# demo_dermis_main_testboard_scratch.net
KiCad netlist of a schematic drawn in Altium Designer
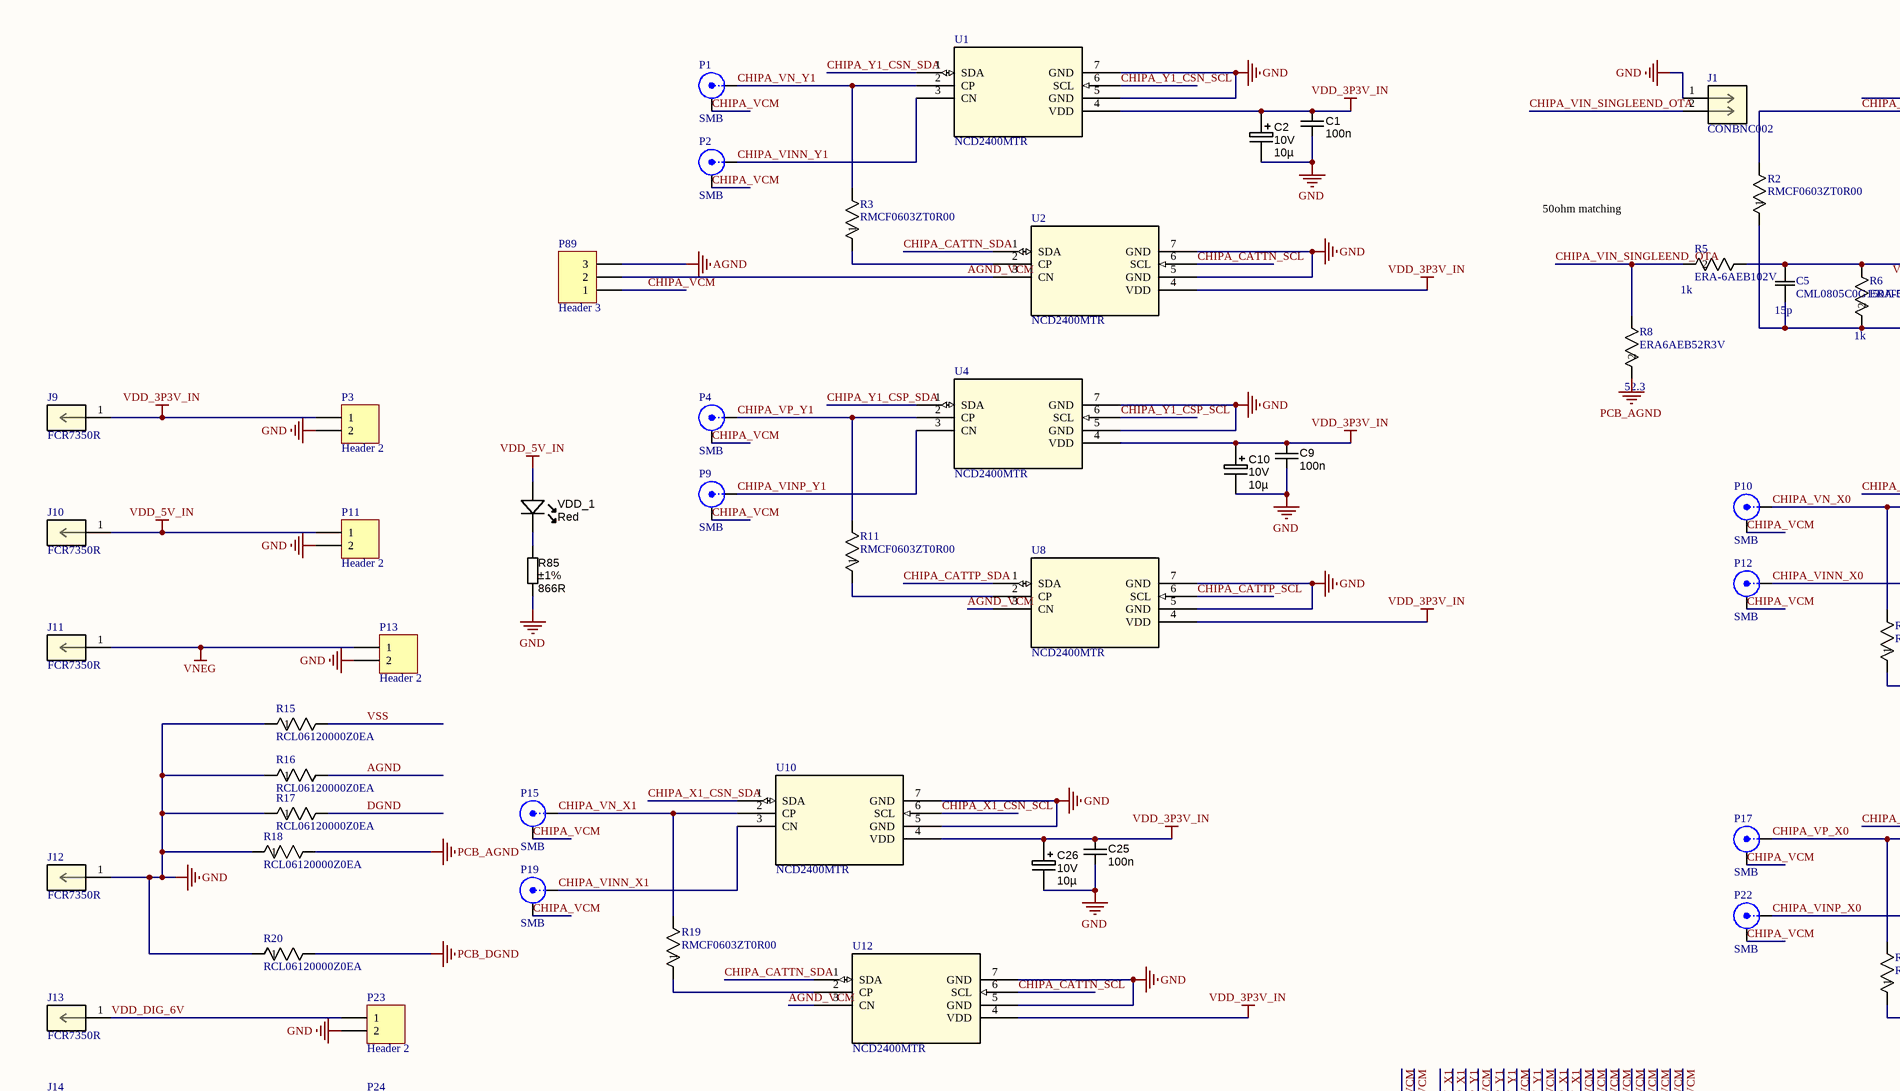
[diagram p0: demo_dermis_main_testboard_scratch.SchDoc, top left]
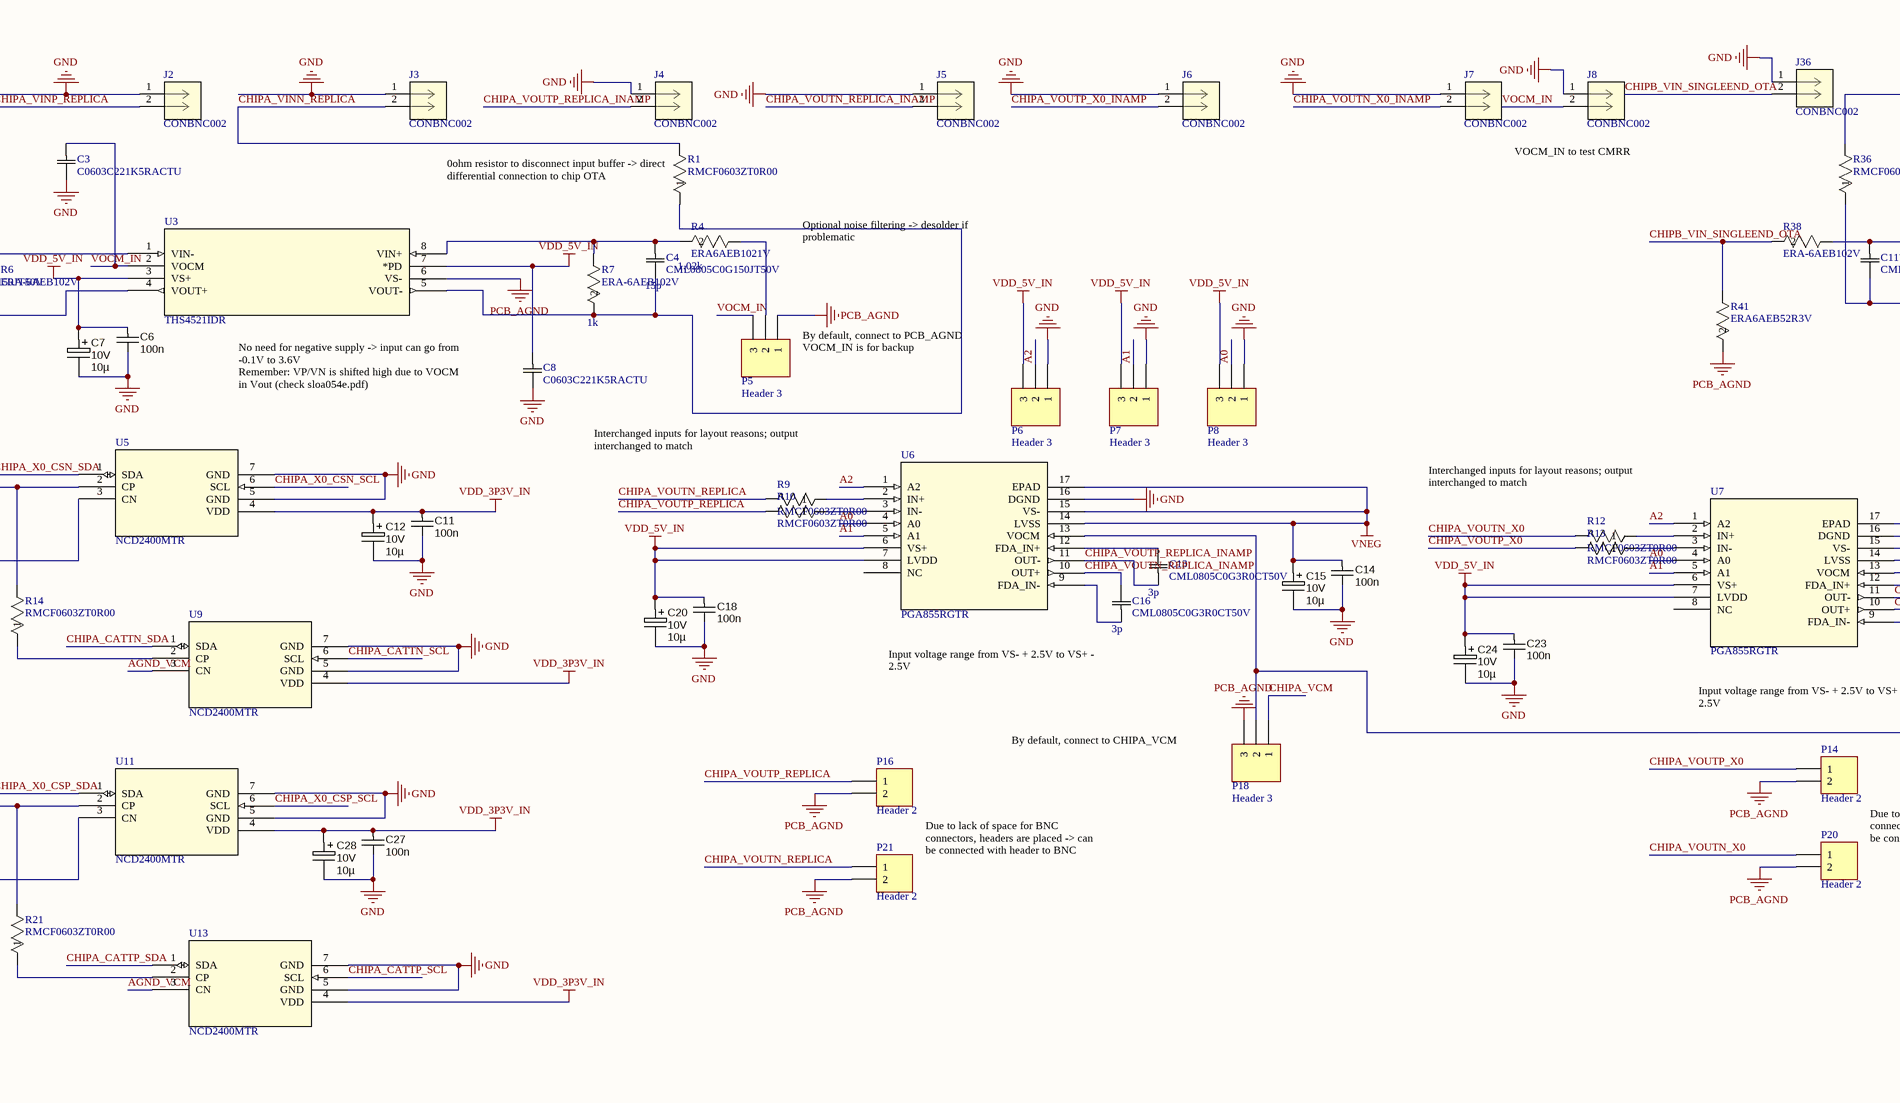
[diagram p1: demo_dermis_main_testboard_scratch.SchDoc, top middle]
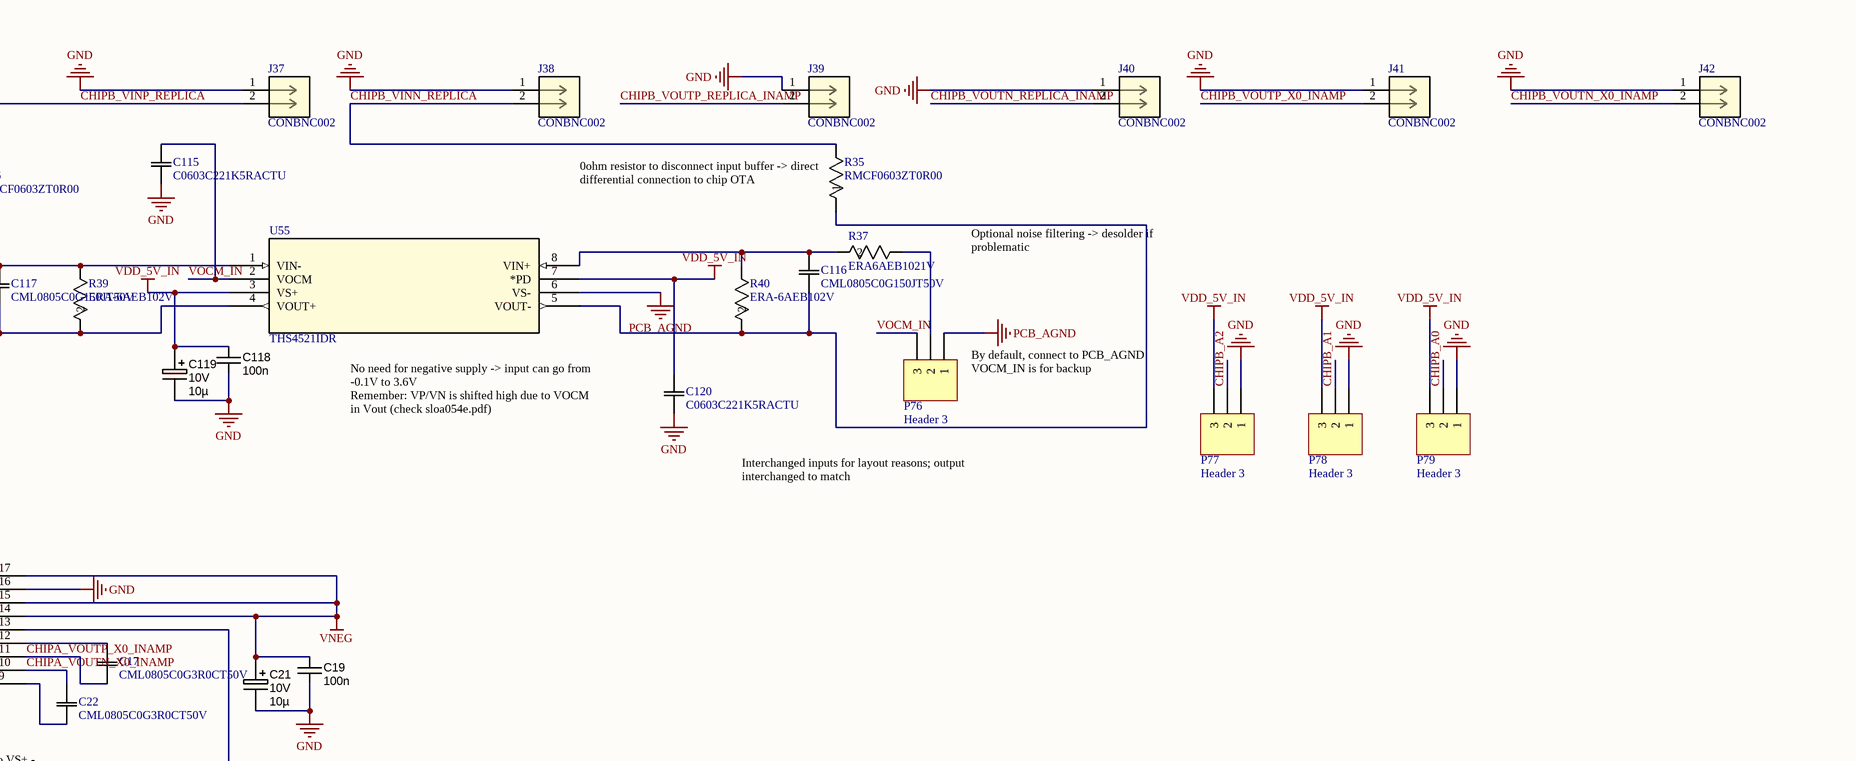
[diagram p2: demo_dermis_main_testboard_scratch.SchDoc, top right]
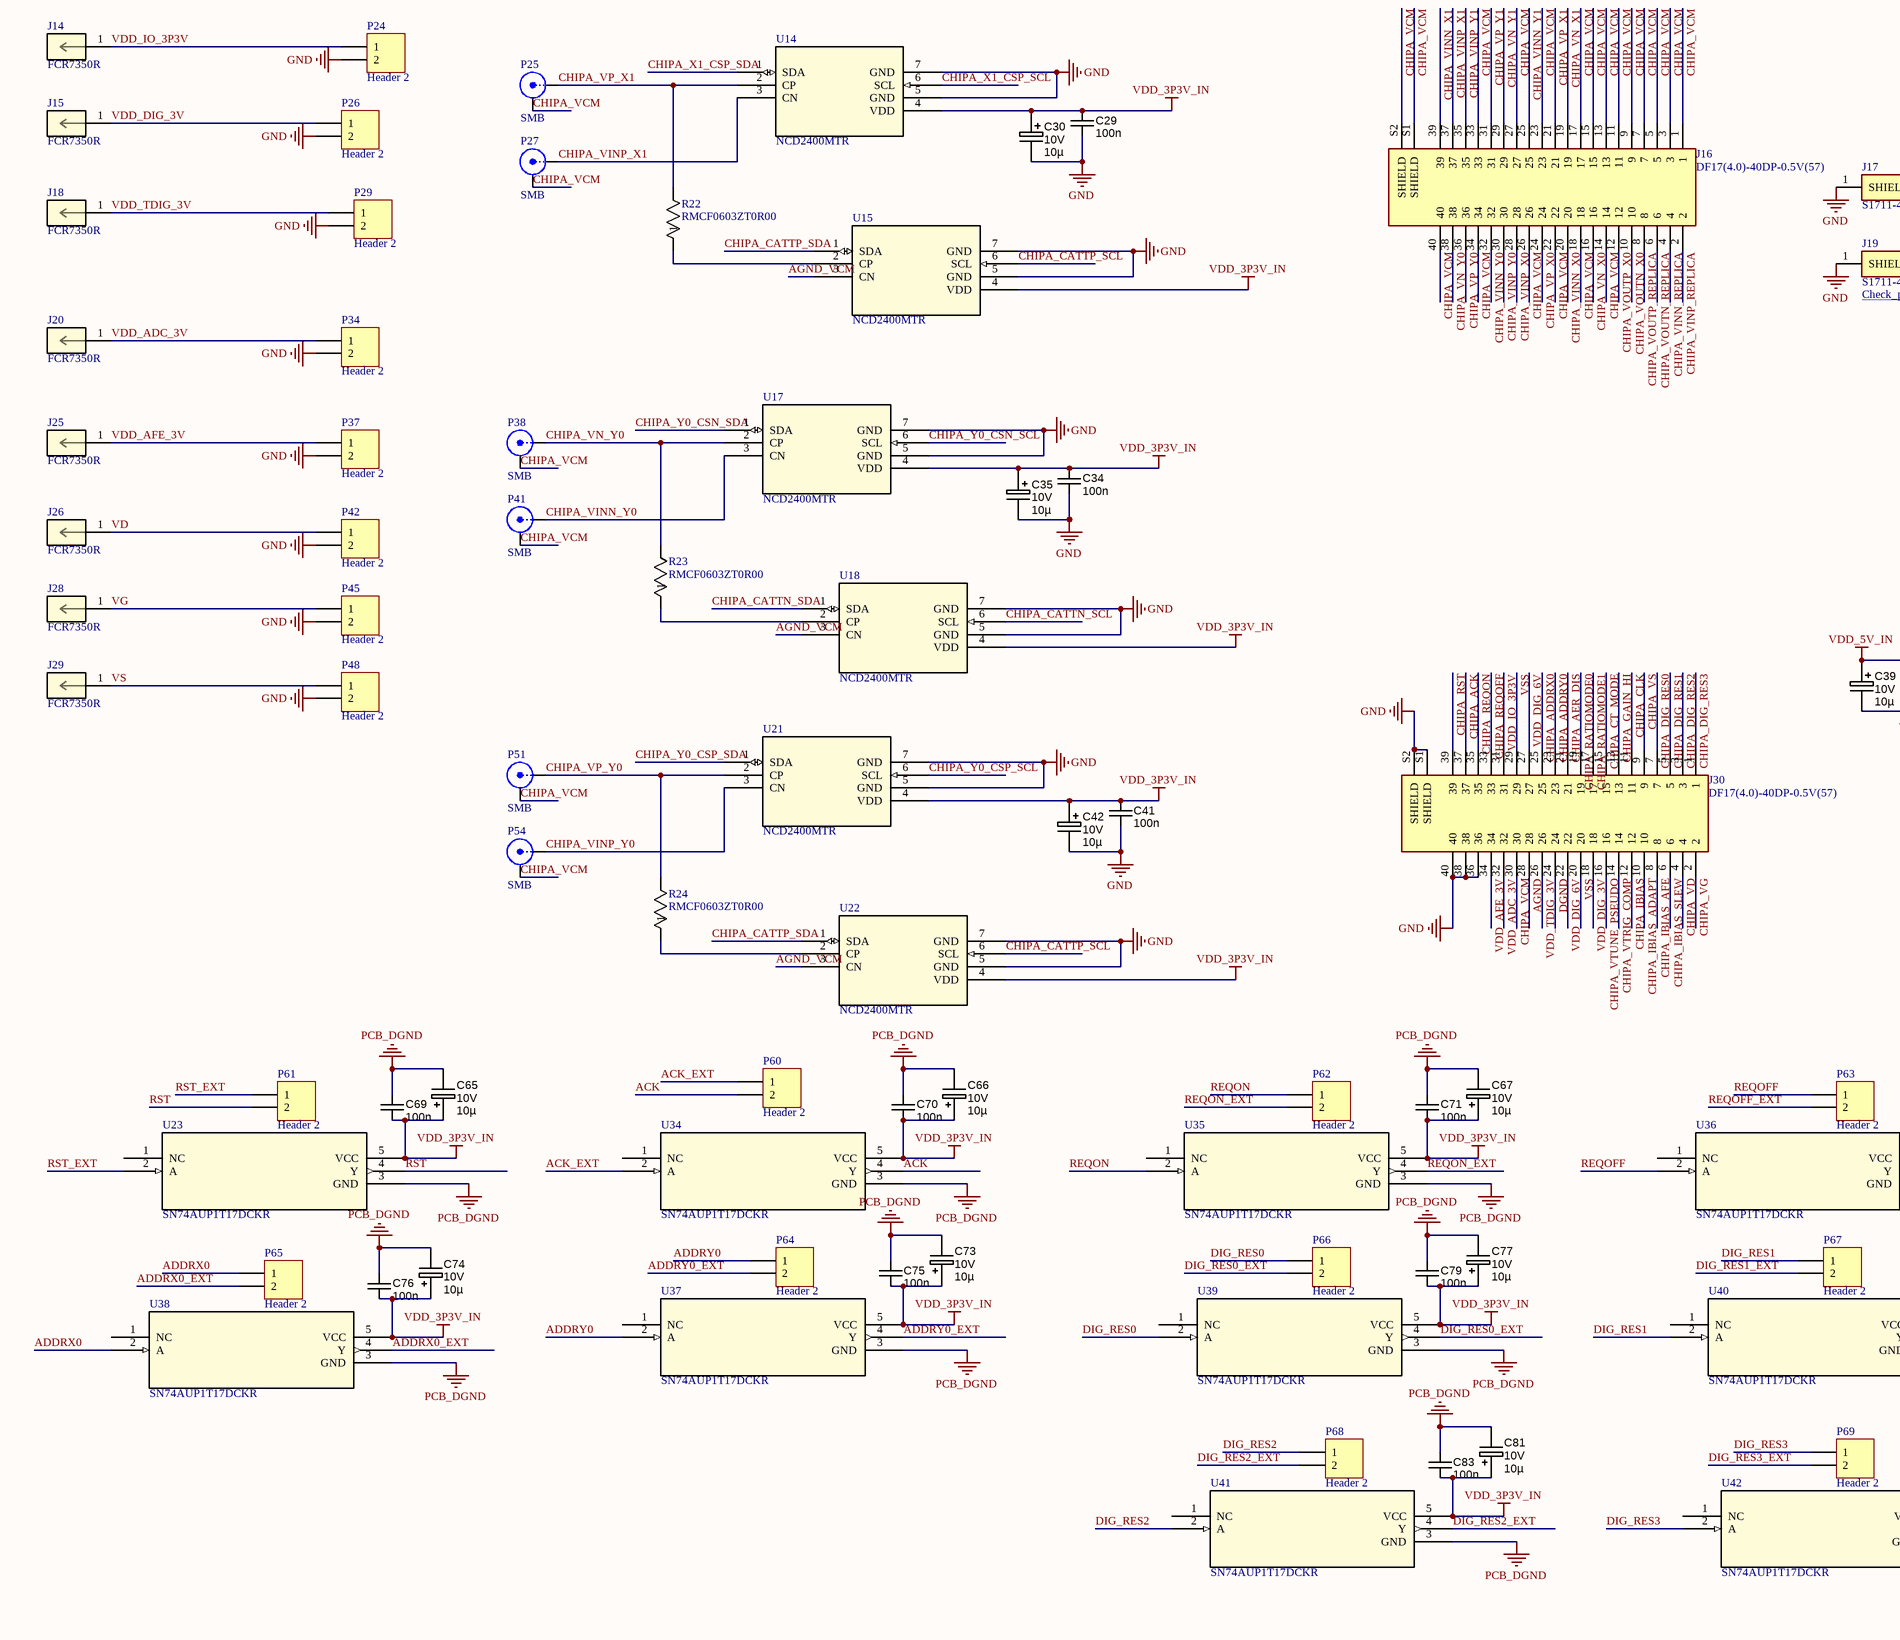
[diagram p3: demo_dermis_main_testboard_scratch.SchDoc, centre left]
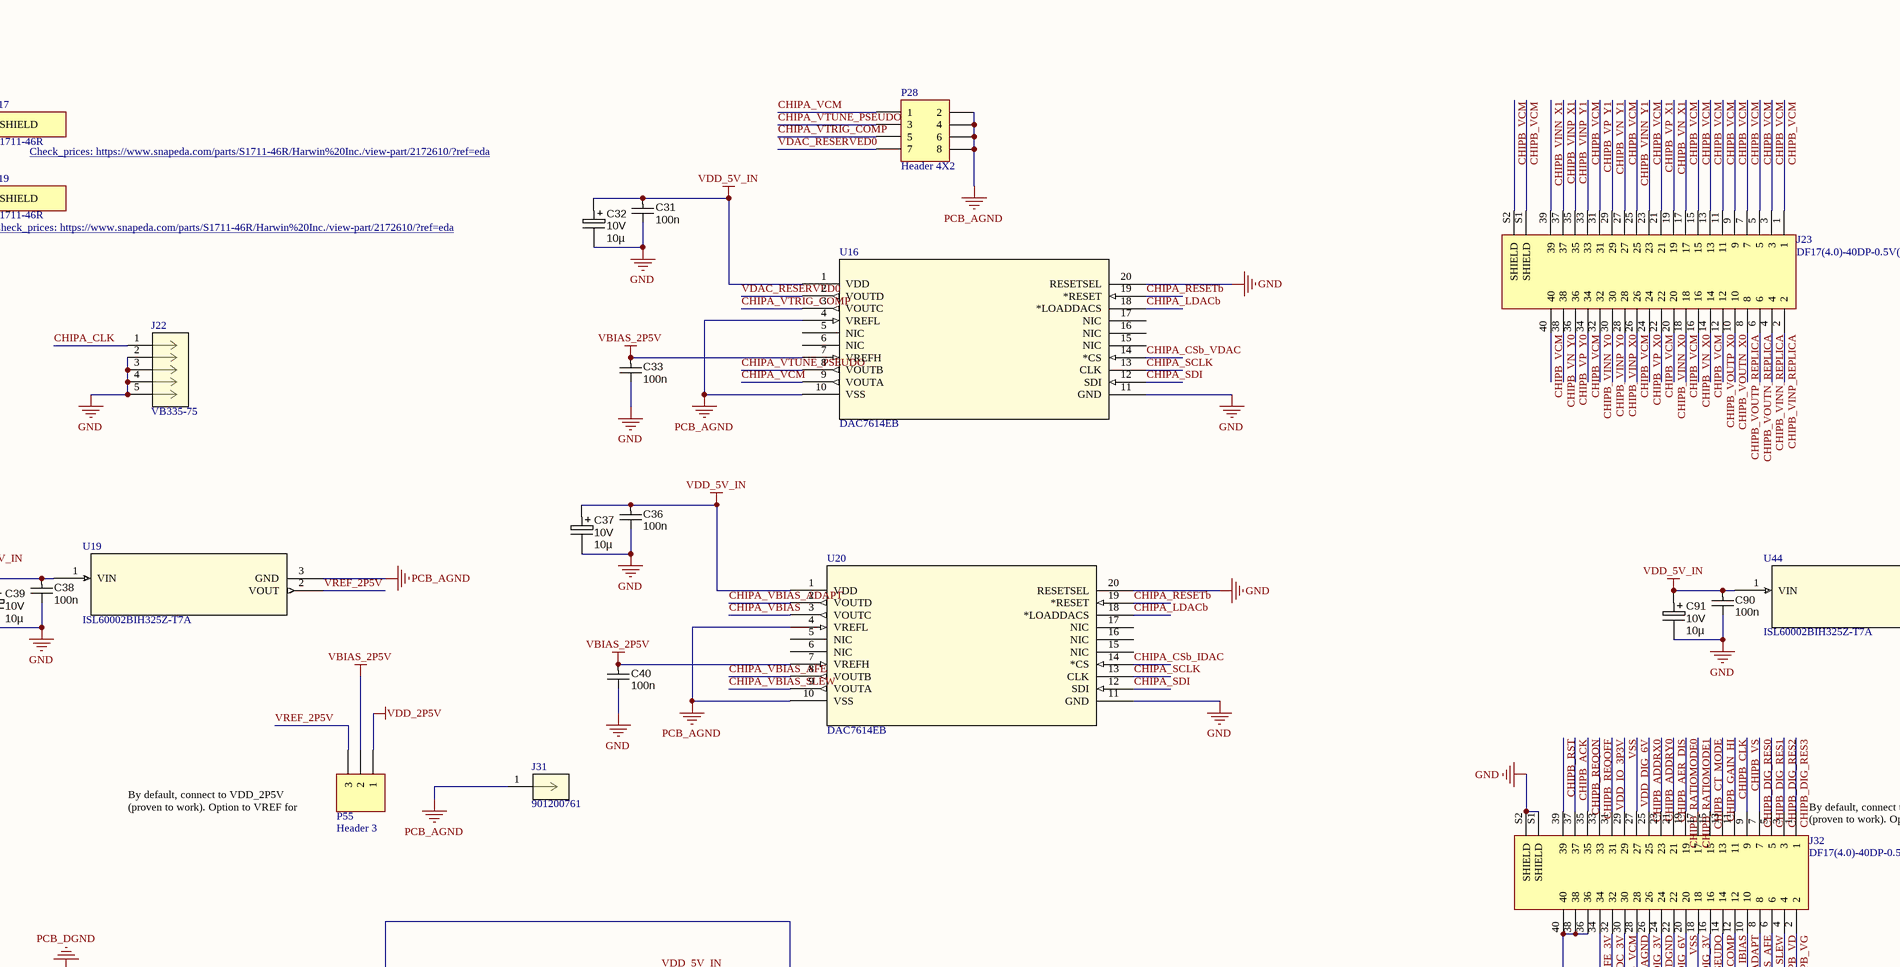
[diagram p4: demo_dermis_main_testboard_scratch.SchDoc, centre middle]
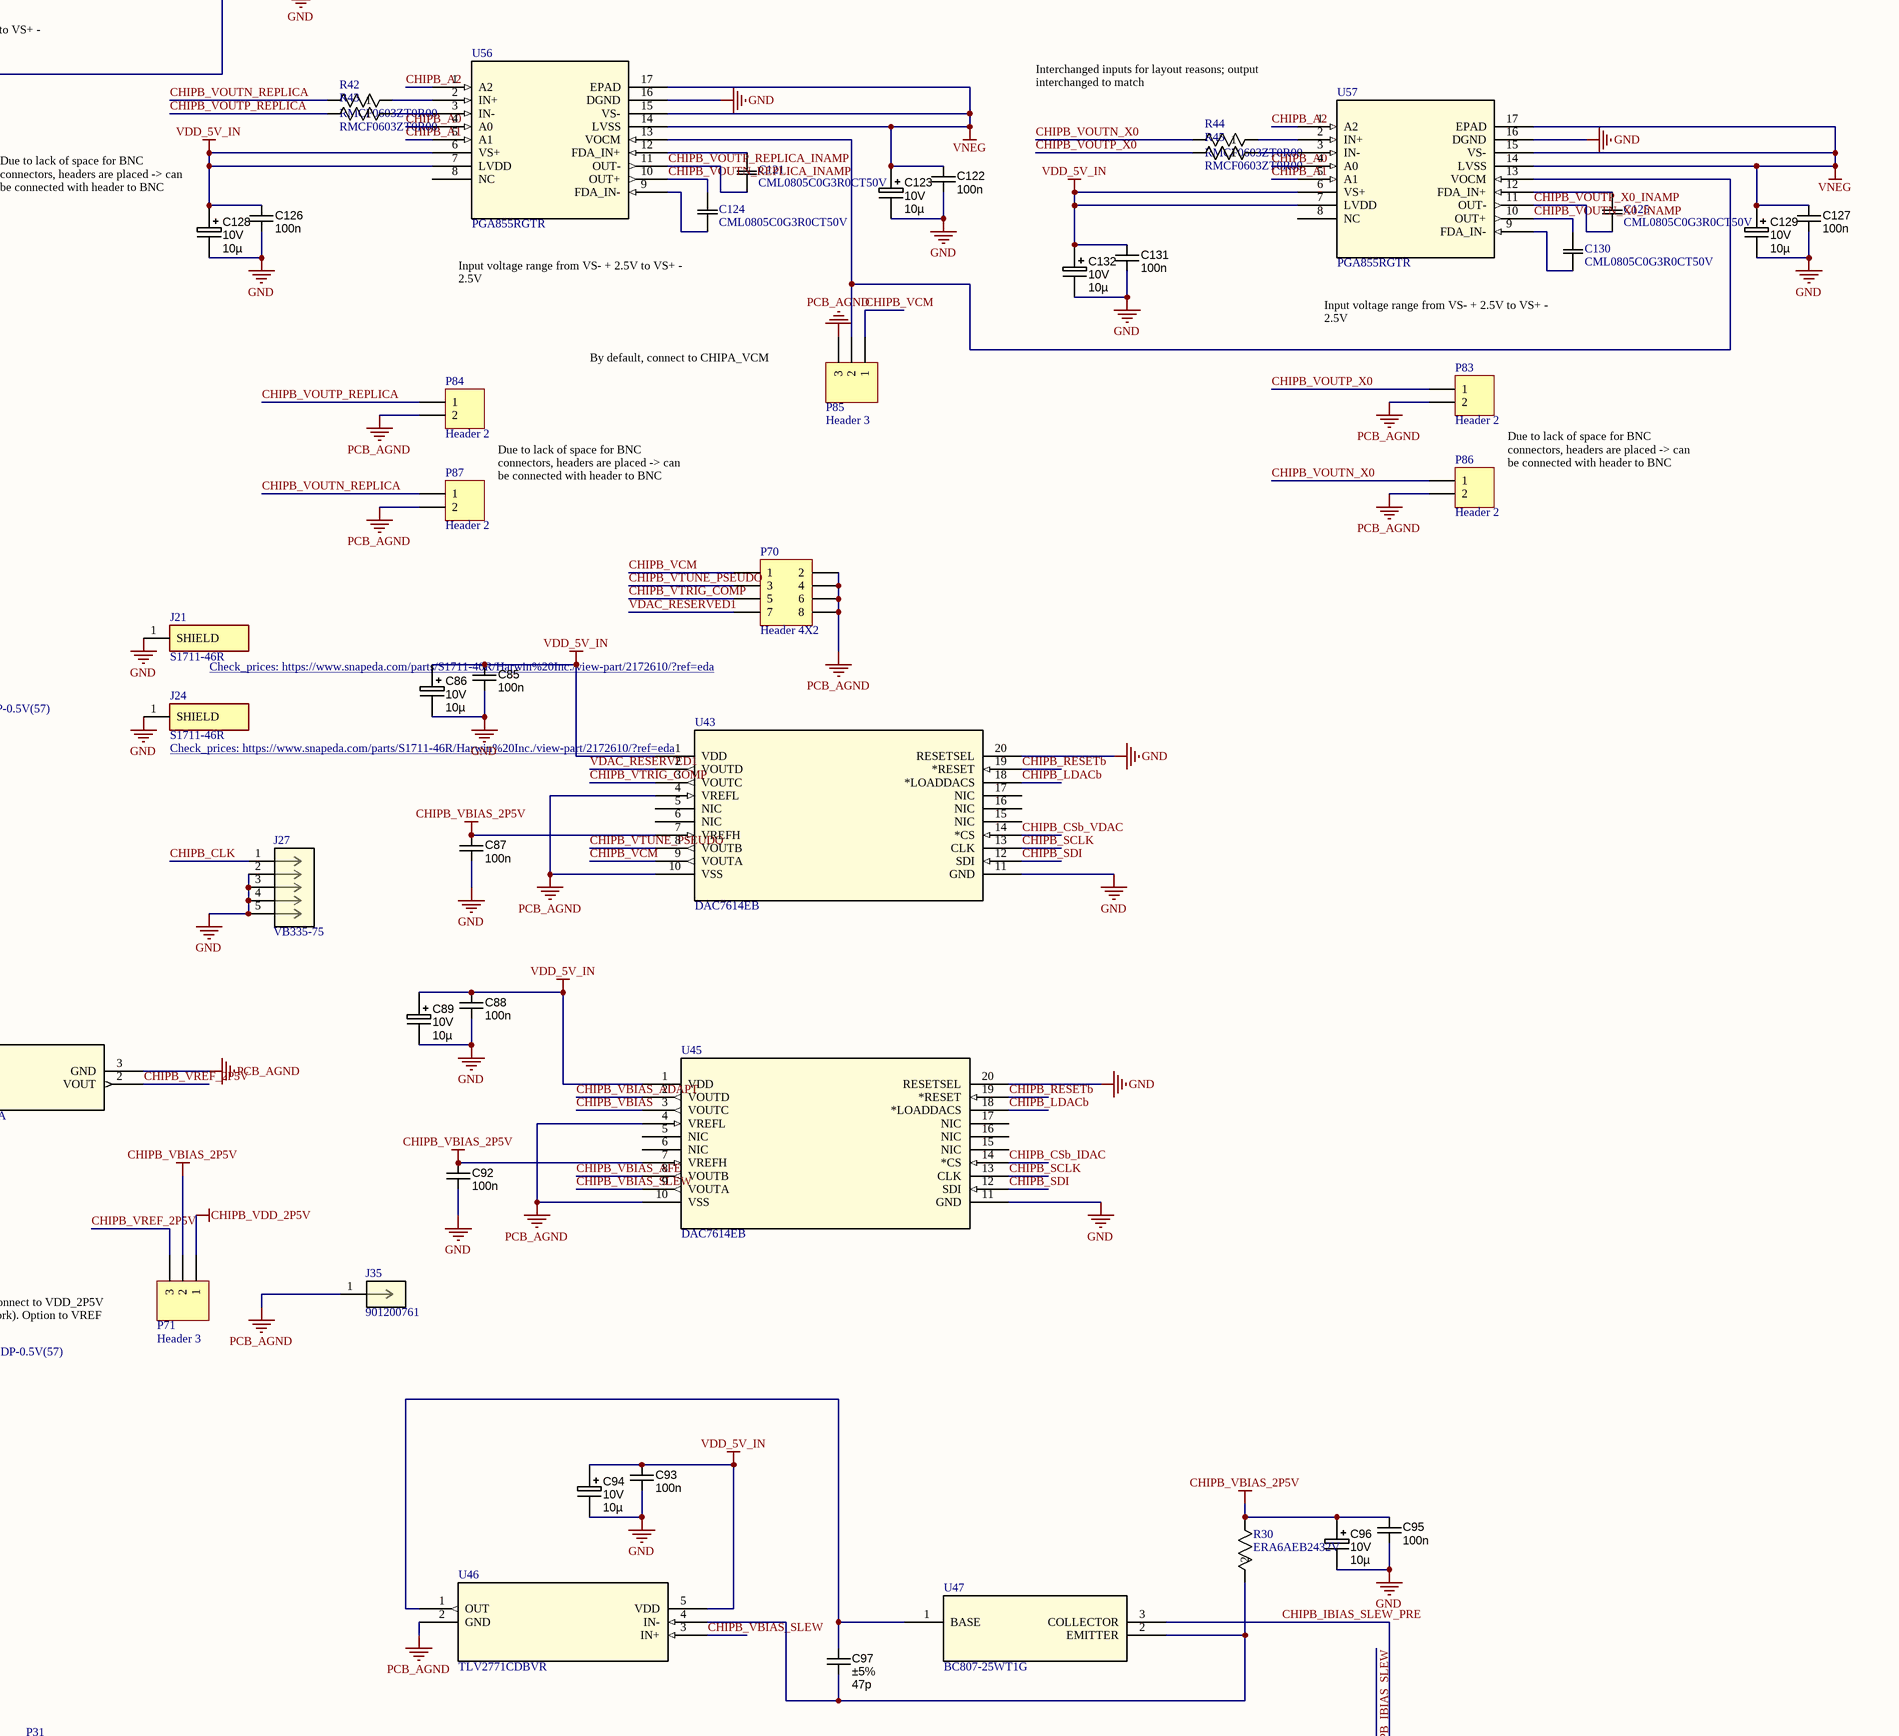
[diagram p5: demo_dermis_main_testboard_scratch.SchDoc, centre right]
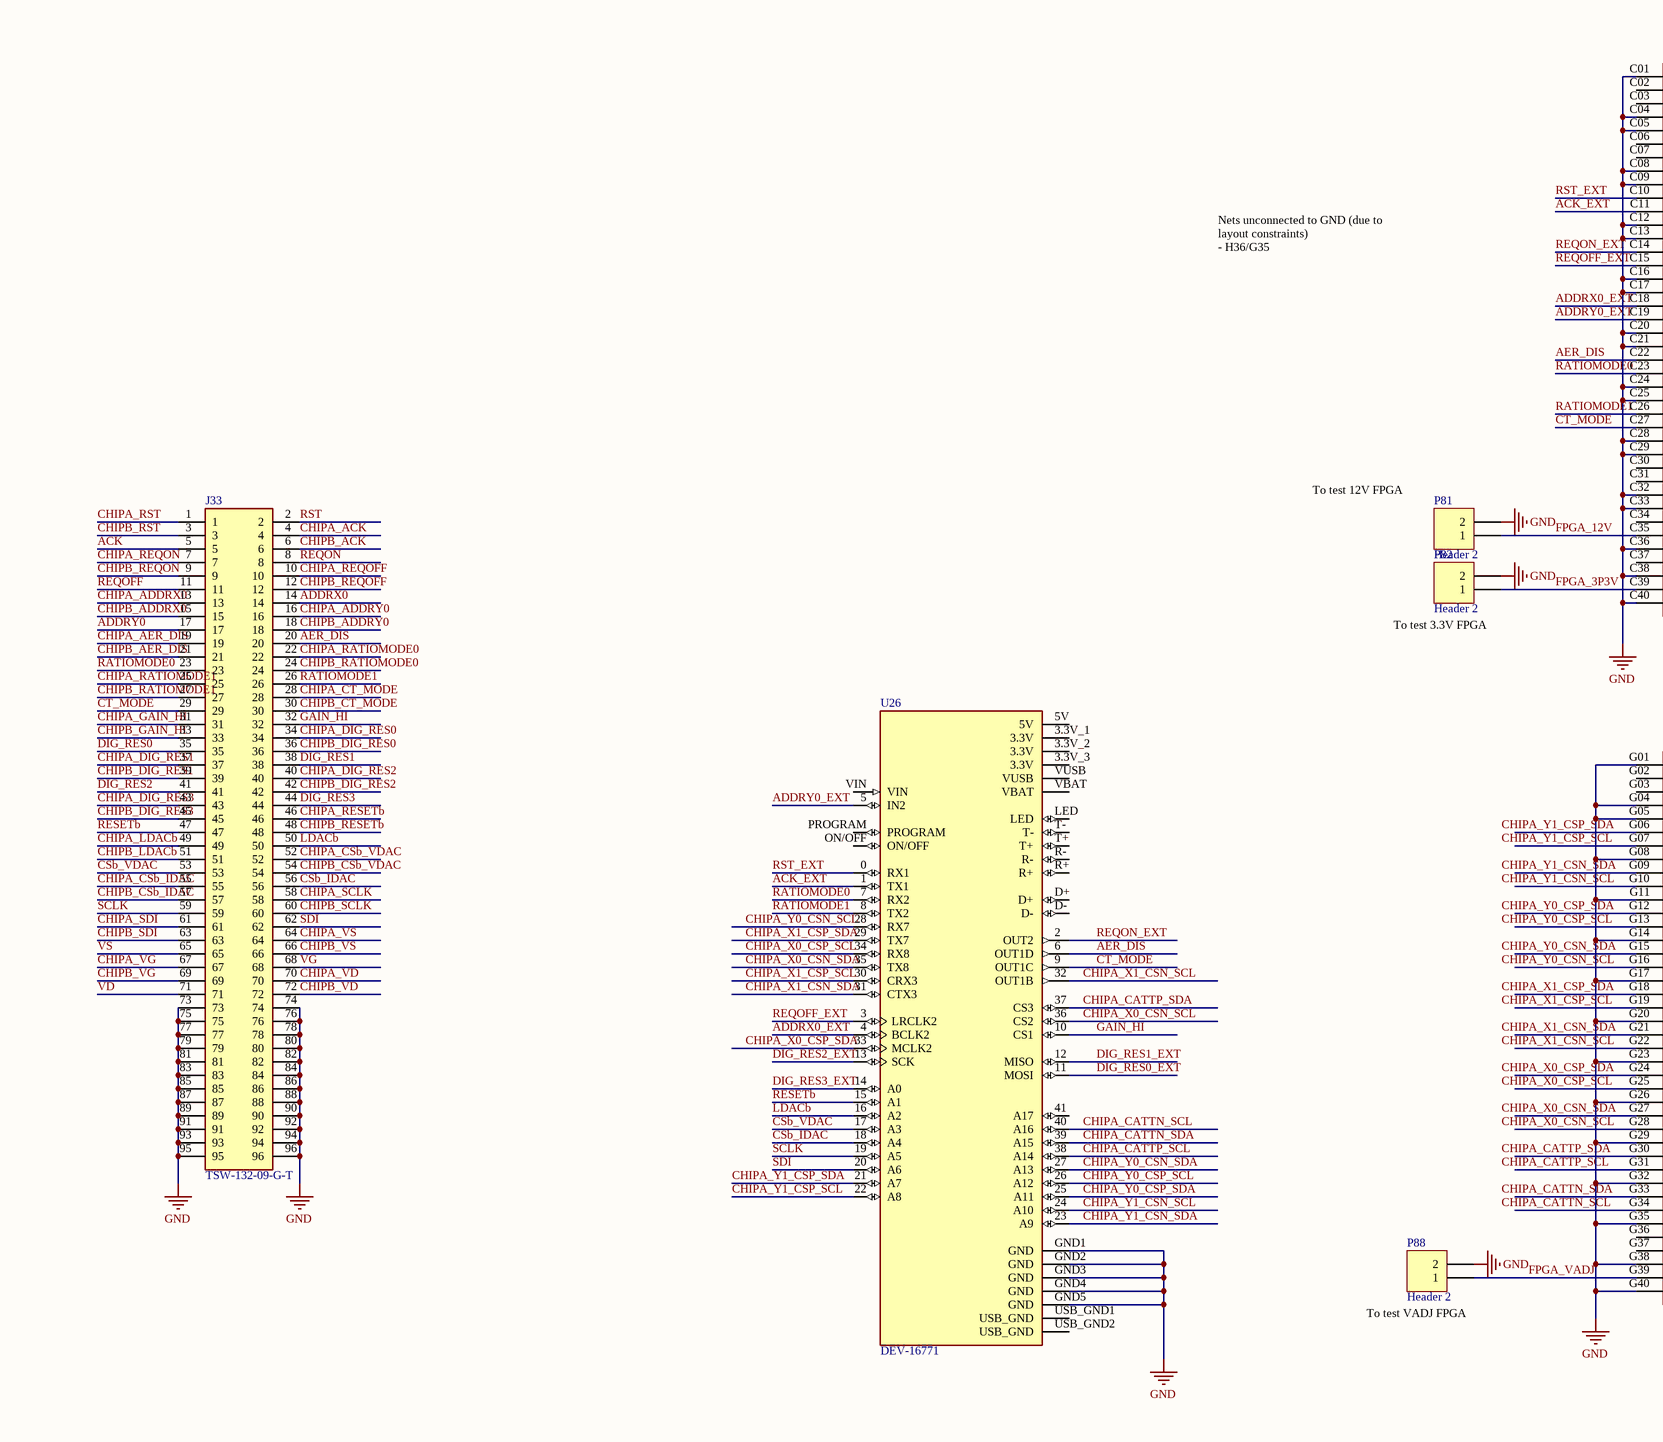
[diagram p6: demo_dermis_main_testboard_scratch.SchDoc, bottom left]
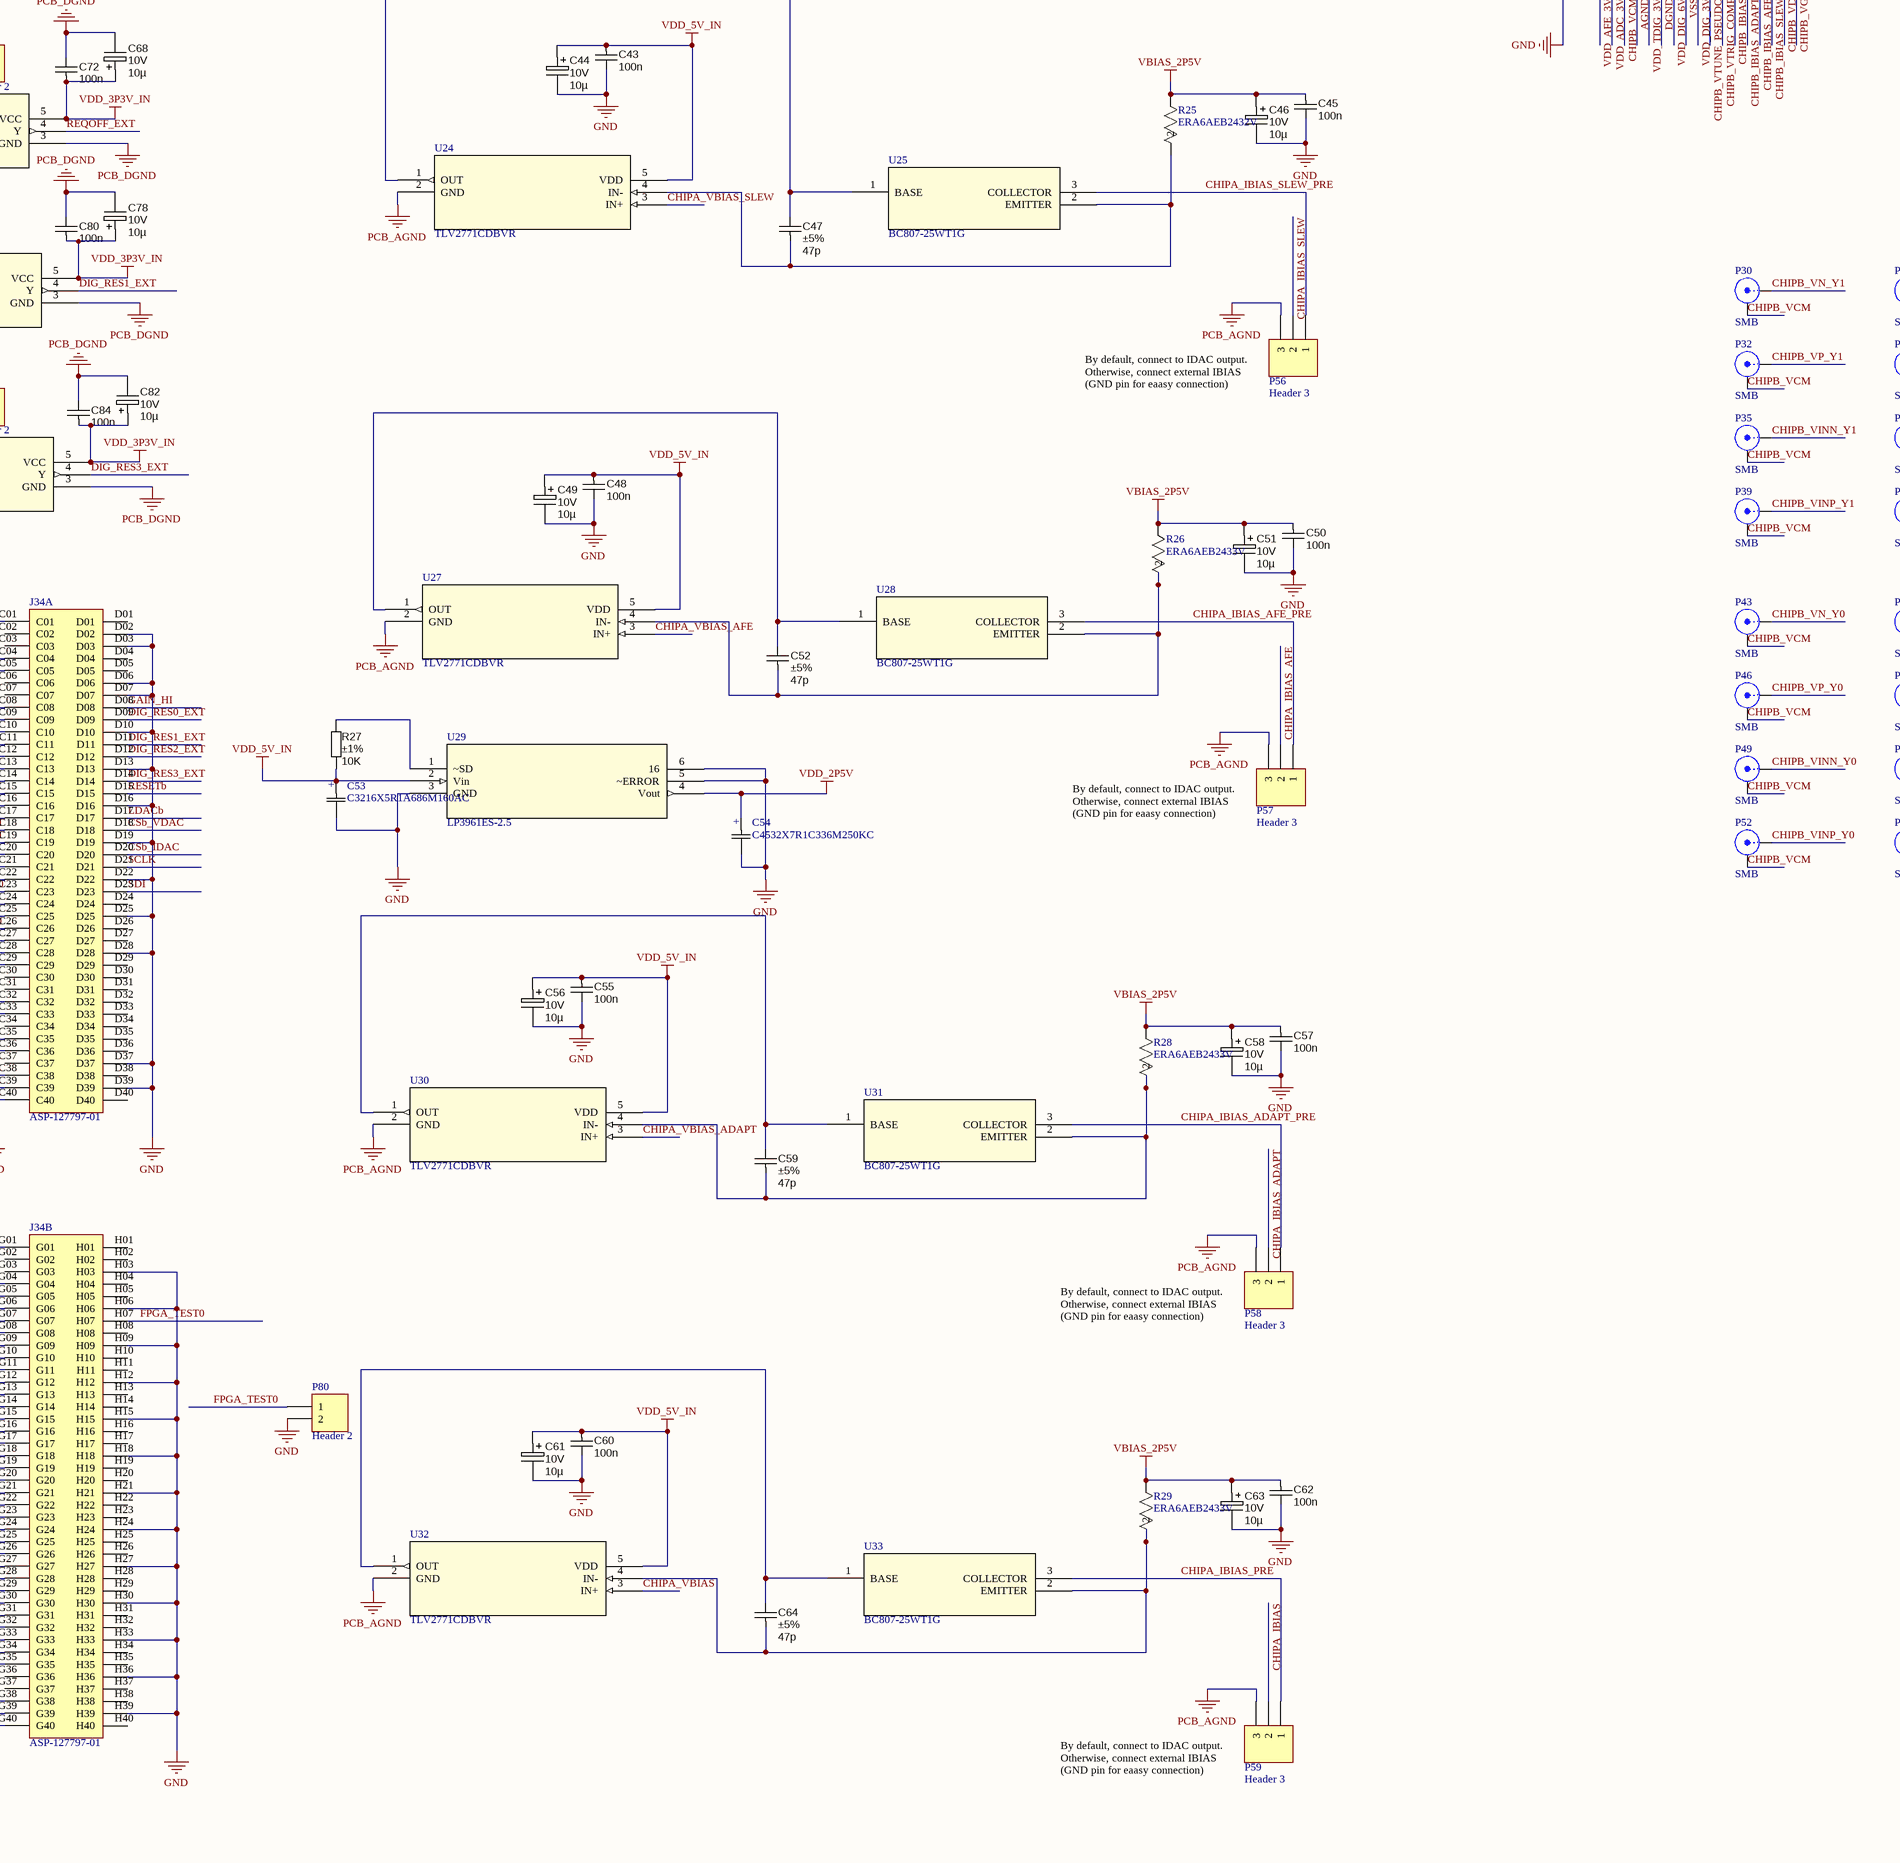
[diagram p7: demo_dermis_main_testboard_scratch.SchDoc, bottom middle]
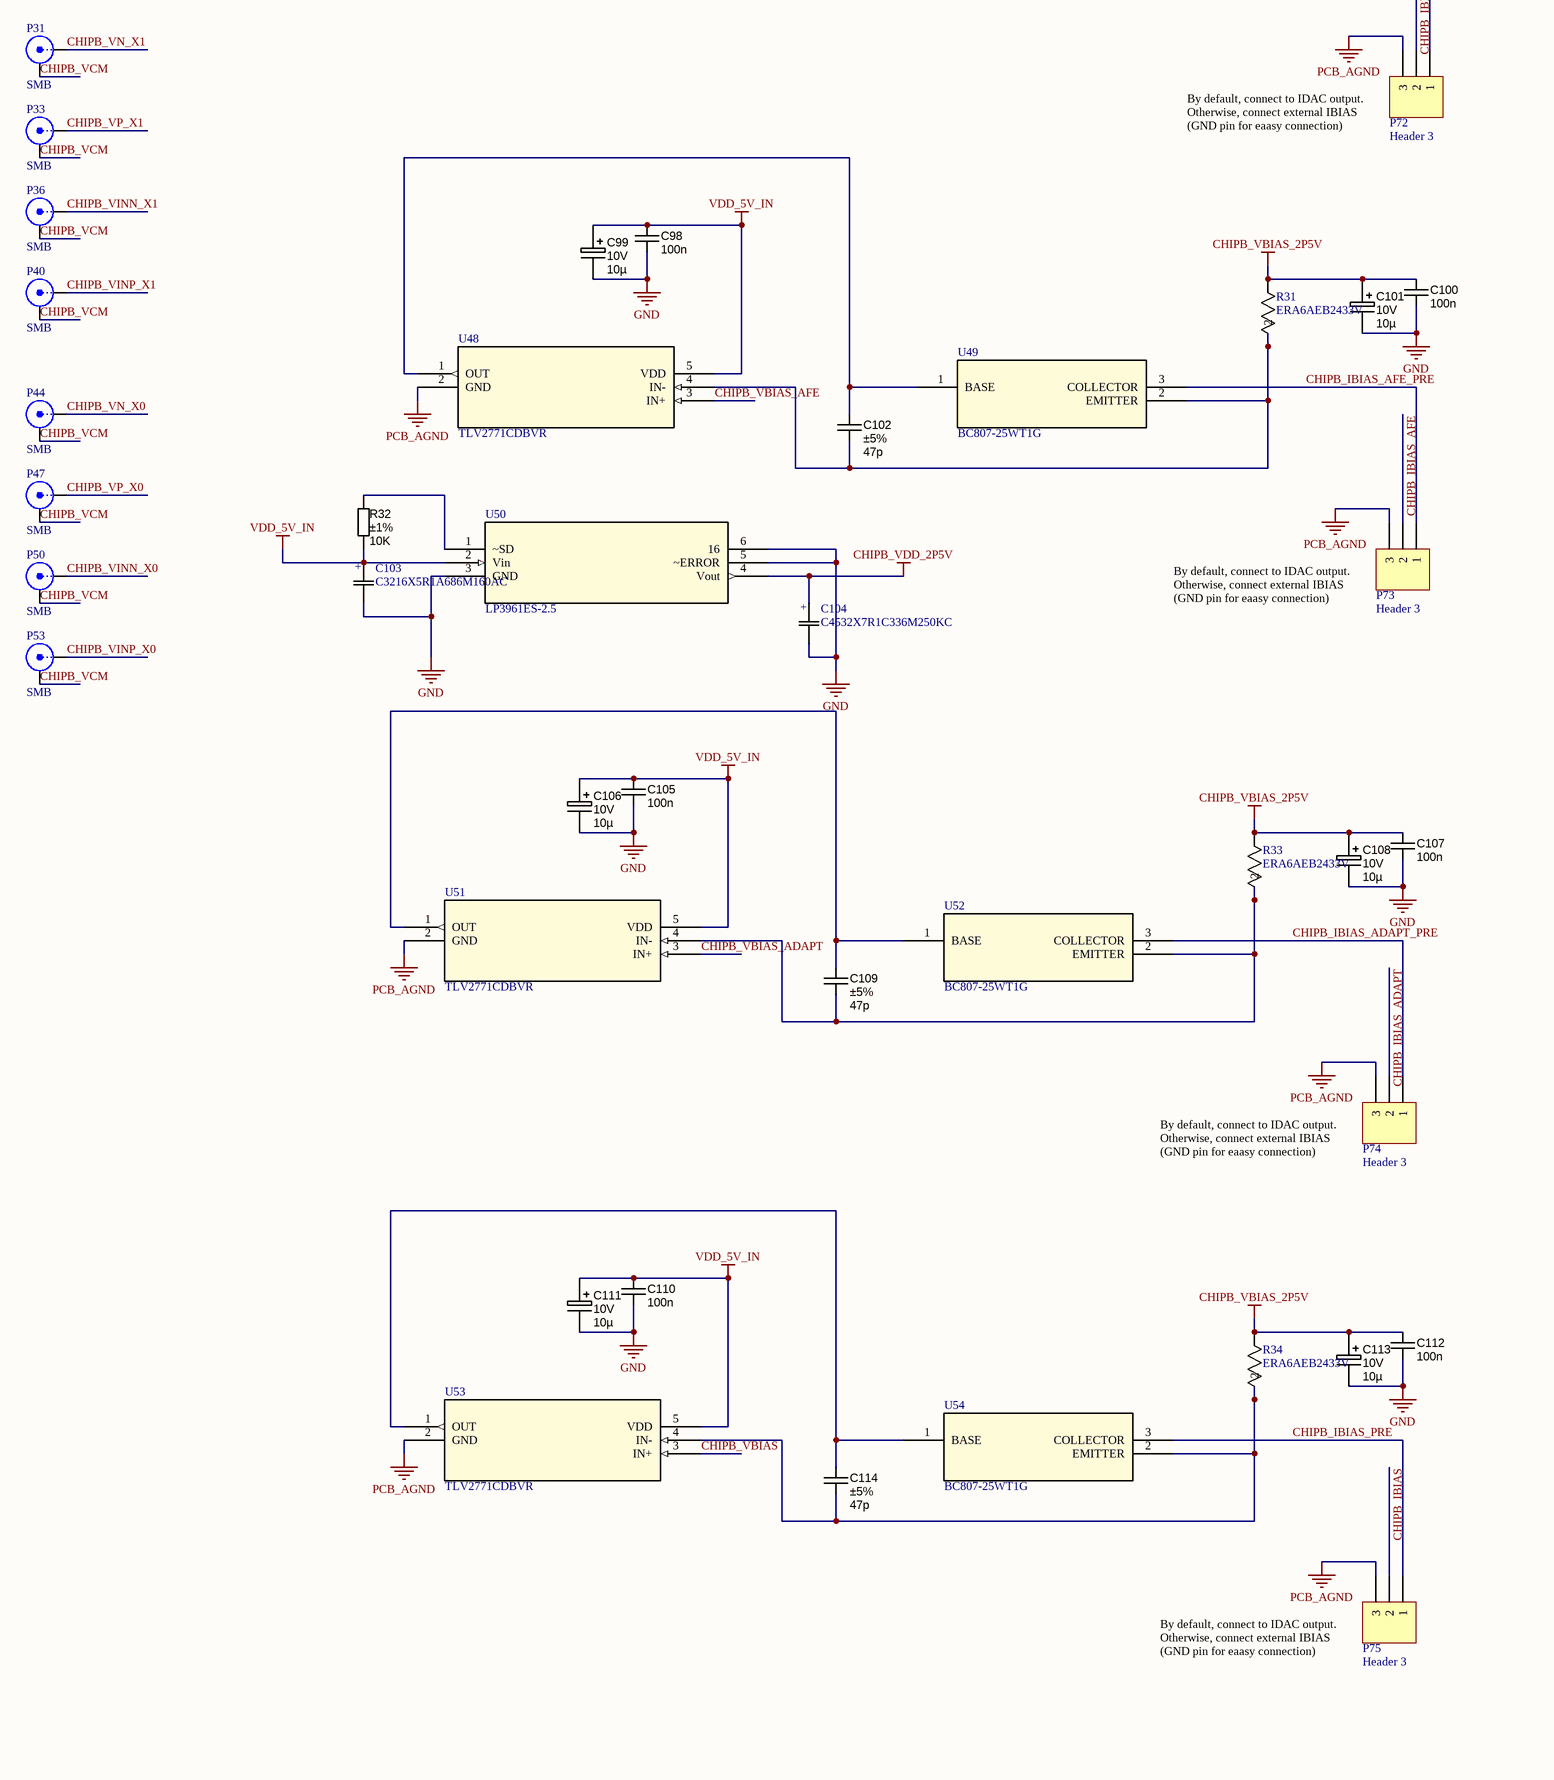
[diagram p8: demo_dermis_main_testboard_scratch.SchDoc, bottom right]

(export (version "E")
  (design (tool "Eeschema 10.0.6"))
  (components
    (comp (ref "C1")
      (value "100n")
      (footprint "CAPC1608N")
      (description "Capacitor SMD Cer 100nF 10% 50V X7R 0603")
      (fields (field (name "TOLERANCE") "±10%") (field (name "Comment") "approved sub OK"))
      (libsource (lib "PBL - Capacitors") (part "CAPC_100n_0603"))
    )
    (comp (ref "C2")
      (value "10µ")
      (footprint "CAPMP2012X150USR")
      (description "Capacitor SMD Tantalum 10uF 20% 10V 0805")
      (fields (field (name "TOLERANCE") "±20%") (field (name "RATINGS") "10V"))
      (libsource (lib "PBL - Capacitors") (part "CAPT_10u_0805_10V"))
    )
    (comp (ref "C3")
      (value "C0603C221K5RACTU")
      (footprint "CAPC17595_87N_KEM")
      (description "No Description Available")
      (libsource (lib "C0603C221K5RACTU") (part "C0603C221K5RACTU"))
    )
    (comp (ref "C4")
      (value "CML0805C0G150JT50V")
      (footprint "CAP_CML_0805_.3pF-1500pF,4700pF_STP")
      (description "No Description Available")
      (fields (field (name "ALTIUM_VALUE") "15p"))
      (libsource (lib "CML0805C0G150JT50V") (part "CML0805C0G150JT50V"))
    )
    (comp (ref "C5")
      (value "CML0805C0G150JT50V")
      (footprint "CAP_CML_0805_.3pF-1500pF,4700pF_STP")
      (description "No Description Available")
      (fields (field (name "ALTIUM_VALUE") "15p"))
      (libsource (lib "CML0805C0G150JT50V") (part "CML0805C0G150JT50V"))
    )
    (comp (ref "C6")
      (value "100n")
      (footprint "CAPC1608N")
      (description "Capacitor SMD Cer 100nF 10% 50V X7R 0603")
      (fields (field (name "TOLERANCE") "±10%") (field (name "Comment") "approved sub OK"))
      (libsource (lib "PBL - Capacitors") (part "CAPC_100n_0603"))
    )
    (comp (ref "C7")
      (value "10µ")
      (footprint "CAPMP2012X150USR")
      (description "Capacitor SMD Tantalum 10uF 20% 10V 0805")
      (fields (field (name "TOLERANCE") "±20%") (field (name "RATINGS") "10V"))
      (libsource (lib "PBL - Capacitors") (part "CAPT_10u_0805_10V"))
    )
    (comp (ref "C8")
      (value "C0603C221K5RACTU")
      (footprint "CAPC17595_87N_KEM")
      (description "No Description Available")
      (libsource (lib "C0603C221K5RACTU") (part "C0603C221K5RACTU"))
    )
    (comp (ref "C9")
      (value "100n")
      (footprint "CAPC1608N")
      (description "Capacitor SMD Cer 100nF 10% 50V X7R 0603")
      (fields (field (name "TOLERANCE") "±10%") (field (name "Comment") "approved sub OK"))
      (libsource (lib "PBL - Capacitors") (part "CAPC_100n_0603"))
    )
    (comp (ref "C10")
      (value "10µ")
      (footprint "CAPMP2012X150USR")
      (description "Capacitor SMD Tantalum 10uF 20% 10V 0805")
      (fields (field (name "TOLERANCE") "±20%") (field (name "RATINGS") "10V"))
      (libsource (lib "PBL - Capacitors") (part "CAPT_10u_0805_10V"))
    )
    (comp (ref "C11")
      (value "100n")
      (footprint "CAPC1608N")
      (description "Capacitor SMD Cer 100nF 10% 50V X7R 0603")
      (fields (field (name "TOLERANCE") "±10%") (field (name "Comment") "approved sub OK"))
      (libsource (lib "PBL - Capacitors") (part "CAPC_100n_0603"))
    )
    (comp (ref "C12")
      (value "10µ")
      (footprint "CAPMP2012X150USR")
      (description "Capacitor SMD Tantalum 10uF 20% 10V 0805")
      (fields (field (name "TOLERANCE") "±20%") (field (name "RATINGS") "10V"))
      (libsource (lib "PBL - Capacitors") (part "CAPT_10u_0805_10V"))
    )
    (comp (ref "C13")
      (value "CML0805C0G3R0CT50V")
      (footprint "CAP_CML_0805_.3pF-1500pF,4700pF_STP")
      (description "No Description Available")
      (fields (field (name "ALTIUM_VALUE") "3p"))
      (libsource (lib "CML0805C0G3R0CT50V") (part "CML0805C0G3R0CT50V"))
    )
    (comp (ref "C14")
      (value "100n")
      (footprint "CAPC1608N")
      (description "Capacitor SMD Cer 100nF 10% 50V X7R 0603")
      (fields (field (name "TOLERANCE") "±10%") (field (name "Comment") "approved sub OK"))
      (libsource (lib "PBL - Capacitors") (part "CAPC_100n_0603"))
    )
    (comp (ref "C15")
      (value "10µ")
      (footprint "CAPMP2012X150USR")
      (description "Capacitor SMD Tantalum 10uF 20% 10V 0805")
      (fields (field (name "TOLERANCE") "±20%") (field (name "RATINGS") "10V"))
      (libsource (lib "PBL - Capacitors") (part "CAPT_10u_0805_10V"))
    )
    (comp (ref "C16")
      (value "CML0805C0G3R0CT50V")
      (footprint "CAP_CML_0805_.3pF-1500pF,4700pF_STP")
      (description "No Description Available")
      (fields (field (name "ALTIUM_VALUE") "3p"))
      (libsource (lib "CML0805C0G3R0CT50V") (part "CML0805C0G3R0CT50V"))
    )
    (comp (ref "C17")
      (value "CML0805C0G3R0CT50V")
      (footprint "CAP_CML_0805_.3pF-1500pF,4700pF_STP")
      (description "No Description Available")
      (libsource (lib "CML0805C0G3R0CT50V") (part "CML0805C0G3R0CT50V"))
    )
    (comp (ref "C18")
      (value "100n")
      (footprint "CAPC1608N")
      (description "Capacitor SMD Cer 100nF 10% 50V X7R 0603")
      (fields (field (name "TOLERANCE") "±10%") (field (name "Comment") "approved sub OK"))
      (libsource (lib "PBL - Capacitors") (part "CAPC_100n_0603"))
    )
    (comp (ref "C19")
      (value "100n")
      (footprint "CAPC1608N")
      (description "Capacitor SMD Cer 100nF 10% 50V X7R 0603")
      (fields (field (name "TOLERANCE") "±10%") (field (name "Comment") "approved sub OK"))
      (libsource (lib "PBL - Capacitors") (part "CAPC_100n_0603"))
    )
    (comp (ref "C20")
      (value "10µ")
      (footprint "CAPMP2012X150USR")
      (description "Capacitor SMD Tantalum 10uF 20% 10V 0805")
      (fields (field (name "TOLERANCE") "±20%") (field (name "RATINGS") "10V"))
      (libsource (lib "PBL - Capacitors") (part "CAPT_10u_0805_10V"))
    )
    (comp (ref "C21")
      (value "10µ")
      (footprint "CAPMP2012X150USR")
      (description "Capacitor SMD Tantalum 10uF 20% 10V 0805")
      (fields (field (name "TOLERANCE") "±20%") (field (name "RATINGS") "10V"))
      (libsource (lib "PBL - Capacitors") (part "CAPT_10u_0805_10V"))
    )
    (comp (ref "C22")
      (value "CML0805C0G3R0CT50V")
      (footprint "CAP_CML_0805_.3pF-1500pF,4700pF_STP")
      (description "No Description Available")
      (libsource (lib "CML0805C0G3R0CT50V") (part "CML0805C0G3R0CT50V"))
    )
    (comp (ref "C23")
      (value "100n")
      (footprint "CAPC1608N")
      (description "Capacitor SMD Cer 100nF 10% 50V X7R 0603")
      (fields (field (name "TOLERANCE") "±10%") (field (name "Comment") "approved sub OK"))
      (libsource (lib "PBL - Capacitors") (part "CAPC_100n_0603"))
    )
    (comp (ref "C24")
      (value "10µ")
      (footprint "CAPMP2012X150USR")
      (description "Capacitor SMD Tantalum 10uF 20% 10V 0805")
      (fields (field (name "TOLERANCE") "±20%") (field (name "RATINGS") "10V"))
      (libsource (lib "PBL - Capacitors") (part "CAPT_10u_0805_10V"))
    )
    (comp (ref "C25")
      (value "100n")
      (footprint "CAPC1608N")
      (description "Capacitor SMD Cer 100nF 10% 50V X7R 0603")
      (fields (field (name "TOLERANCE") "±10%") (field (name "Comment") "approved sub OK"))
      (libsource (lib "PBL - Capacitors") (part "CAPC_100n_0603"))
    )
    (comp (ref "C26")
      (value "10µ")
      (footprint "CAPMP2012X150USR")
      (description "Capacitor SMD Tantalum 10uF 20% 10V 0805")
      (fields (field (name "TOLERANCE") "±20%") (field (name "RATINGS") "10V"))
      (libsource (lib "PBL - Capacitors") (part "CAPT_10u_0805_10V"))
    )
    (comp (ref "C27")
      (value "100n")
      (footprint "CAPC1608N")
      (description "Capacitor SMD Cer 100nF 10% 50V X7R 0603")
      (fields (field (name "TOLERANCE") "±10%") (field (name "Comment") "approved sub OK"))
      (libsource (lib "PBL - Capacitors") (part "CAPC_100n_0603"))
    )
    (comp (ref "C28")
      (value "10µ")
      (footprint "CAPMP2012X150USR")
      (description "Capacitor SMD Tantalum 10uF 20% 10V 0805")
      (fields (field (name "TOLERANCE") "±20%") (field (name "RATINGS") "10V"))
      (libsource (lib "PBL - Capacitors") (part "CAPT_10u_0805_10V"))
    )
    (comp (ref "C29")
      (value "100n")
      (footprint "CAPC1608N")
      (description "Capacitor SMD Cer 100nF 10% 50V X7R 0603")
      (fields (field (name "TOLERANCE") "±10%") (field (name "Comment") "approved sub OK"))
      (libsource (lib "PBL - Capacitors") (part "CAPC_100n_0603"))
    )
    (comp (ref "C30")
      (value "10µ")
      (footprint "CAPMP2012X150USR")
      (description "Capacitor SMD Tantalum 10uF 20% 10V 0805")
      (fields (field (name "TOLERANCE") "±20%") (field (name "RATINGS") "10V"))
      (libsource (lib "PBL - Capacitors") (part "CAPT_10u_0805_10V"))
    )
    (comp (ref "C31")
      (value "100n")
      (footprint "CAPC1608N")
      (description "Capacitor SMD Cer 100nF 10% 50V X7R 0603")
      (fields (field (name "TOLERANCE") "±10%") (field (name "Comment") "approved sub OK"))
      (libsource (lib "PBL - Capacitors") (part "CAPC_100n_0603"))
    )
    (comp (ref "C32")
      (value "10µ")
      (footprint "CAPMP2012X150USR")
      (description "Capacitor SMD Tantalum 10uF 20% 10V 0805")
      (fields (field (name "TOLERANCE") "±20%") (field (name "RATINGS") "10V"))
      (libsource (lib "PBL - Capacitors") (part "CAPT_10u_0805_10V"))
    )
    (comp (ref "C33")
      (value "100n")
      (footprint "CAPC1608N")
      (description "Capacitor SMD Cer 100nF 10% 50V X7R 0603")
      (fields (field (name "TOLERANCE") "±10%") (field (name "Comment") "approved sub OK"))
      (libsource (lib "PBL - Capacitors") (part "CAPC_100n_0603"))
    )
    (comp (ref "C34")
      (value "100n")
      (footprint "CAPC1608N")
      (description "Capacitor SMD Cer 100nF 10% 50V X7R 0603")
      (fields (field (name "TOLERANCE") "±10%") (field (name "Comment") "approved sub OK"))
      (libsource (lib "PBL - Capacitors") (part "CAPC_100n_0603"))
    )
    (comp (ref "C35")
      (value "10µ")
      (footprint "CAPMP2012X150USR")
      (description "Capacitor SMD Tantalum 10uF 20% 10V 0805")
      (fields (field (name "TOLERANCE") "±20%") (field (name "RATINGS") "10V"))
      (libsource (lib "PBL - Capacitors") (part "CAPT_10u_0805_10V"))
    )
    (comp (ref "C36")
      (value "100n")
      (footprint "CAPC1608N")
      (description "Capacitor SMD Cer 100nF 10% 50V X7R 0603")
      (fields (field (name "TOLERANCE") "±10%") (field (name "Comment") "approved sub OK"))
      (libsource (lib "PBL - Capacitors") (part "CAPC_100n_0603"))
    )
    (comp (ref "C37")
      (value "10µ")
      (footprint "CAPMP2012X150USR")
      (description "Capacitor SMD Tantalum 10uF 20% 10V 0805")
      (fields (field (name "TOLERANCE") "±20%") (field (name "RATINGS") "10V"))
      (libsource (lib "PBL - Capacitors") (part "CAPT_10u_0805_10V"))
    )
    (comp (ref "C38")
      (value "100n")
      (footprint "CAPC1608N")
      (description "Capacitor SMD Cer 100nF 10% 50V X7R 0603")
      (fields (field (name "TOLERANCE") "±10%") (field (name "Comment") "approved sub OK"))
      (libsource (lib "PBL - Capacitors") (part "CAPC_100n_0603"))
    )
    (comp (ref "C39")
      (value "10µ")
      (footprint "CAPMP2012X150USR")
      (description "Capacitor SMD Tantalum 10uF 20% 10V 0805")
      (fields (field (name "TOLERANCE") "±20%") (field (name "RATINGS") "10V"))
      (libsource (lib "PBL - Capacitors") (part "CAPT_10u_0805_10V"))
    )
    (comp (ref "C40")
      (value "100n")
      (footprint "CAPC1608N")
      (description "Capacitor SMD Cer 100nF 10% 50V X7R 0603")
      (fields (field (name "TOLERANCE") "±10%") (field (name "Comment") "approved sub OK"))
      (libsource (lib "PBL - Capacitors") (part "CAPC_100n_0603"))
    )
    (comp (ref "C41")
      (value "100n")
      (footprint "CAPC1608N")
      (description "Capacitor SMD Cer 100nF 10% 50V X7R 0603")
      (fields (field (name "TOLERANCE") "±10%") (field (name "Comment") "approved sub OK"))
      (libsource (lib "PBL - Capacitors") (part "CAPC_100n_0603"))
    )
    (comp (ref "C42")
      (value "10µ")
      (footprint "CAPMP2012X150USR")
      (description "Capacitor SMD Tantalum 10uF 20% 10V 0805")
      (fields (field (name "TOLERANCE") "±20%") (field (name "RATINGS") "10V"))
      (libsource (lib "PBL - Capacitors") (part "CAPT_10u_0805_10V"))
    )
    (comp (ref "C43")
      (value "100n")
      (footprint "CAPC1608N")
      (description "Capacitor SMD Cer 100nF 10% 50V X7R 0603")
      (fields (field (name "TOLERANCE") "±10%") (field (name "Comment") "approved sub OK"))
      (libsource (lib "PBL - Capacitors") (part "CAPC_100n_0603"))
    )
    (comp (ref "C44")
      (value "10µ")
      (footprint "CAPMP2012X150USR")
      (description "Capacitor SMD Tantalum 10uF 20% 10V 0805")
      (fields (field (name "TOLERANCE") "±20%") (field (name "RATINGS") "10V"))
      (libsource (lib "PBL - Capacitors") (part "CAPT_10u_0805_10V"))
    )
    (comp (ref "C45")
      (value "100n")
      (footprint "CAPC1608N")
      (description "Capacitor SMD Cer 100nF 10% 50V X7R 0603")
      (fields (field (name "TOLERANCE") "±10%") (field (name "Comment") "approved sub OK"))
      (libsource (lib "PBL - Capacitors") (part "CAPC_100n_0603"))
    )
    (comp (ref "C46")
      (value "10µ")
      (footprint "CAPMP2012X150USR")
      (description "Capacitor SMD Tantalum 10uF 20% 10V 0805")
      (fields (field (name "TOLERANCE") "±20%") (field (name "RATINGS") "10V"))
      (libsource (lib "PBL - Capacitors") (part "CAPT_10u_0805_10V"))
    )
    (comp (ref "C47")
      (value "47p")
      (footprint "CAPC1608N")
      (description "Capacitor SMD Cer 47pF 0603")
      (fields (field (name "TOLERANCE") "±5%"))
      (libsource (lib "MB - Misc") (part "CAPC_47p_0603"))
    )
    (comp (ref "C48")
      (value "100n")
      (footprint "CAPC1608N")
      (description "Capacitor SMD Cer 100nF 10% 50V X7R 0603")
      (fields (field (name "TOLERANCE") "±10%") (field (name "Comment") "approved sub OK"))
      (libsource (lib "PBL - Capacitors") (part "CAPC_100n_0603"))
    )
    (comp (ref "C49")
      (value "10µ")
      (footprint "CAPMP2012X150USR")
      (description "Capacitor SMD Tantalum 10uF 20% 10V 0805")
      (fields (field (name "TOLERANCE") "±20%") (field (name "RATINGS") "10V"))
      (libsource (lib "PBL - Capacitors") (part "CAPT_10u_0805_10V"))
    )
    (comp (ref "C50")
      (value "100n")
      (footprint "CAPC1608N")
      (description "Capacitor SMD Cer 100nF 10% 50V X7R 0603")
      (fields (field (name "TOLERANCE") "±10%") (field (name "Comment") "approved sub OK"))
      (libsource (lib "PBL - Capacitors") (part "CAPC_100n_0603"))
    )
    (comp (ref "C51")
      (value "10µ")
      (footprint "CAPMP2012X150USR")
      (description "Capacitor SMD Tantalum 10uF 20% 10V 0805")
      (fields (field (name "TOLERANCE") "±20%") (field (name "RATINGS") "10V"))
      (libsource (lib "PBL - Capacitors") (part "CAPT_10u_0805_10V"))
    )
    (comp (ref "C52")
      (value "47p")
      (footprint "CAPC1608N")
      (description "Capacitor SMD Cer 47pF 0603")
      (fields (field (name "TOLERANCE") "±5%"))
      (libsource (lib "MB - Misc") (part "CAPC_47p_0603"))
    )
    (comp (ref "C53")
      (value "C3216X5R1A686M160AC")
      (footprint "CAP_3216_TDK")
      (description "No Description Available")
      (fields (field (name "COPYRIGHT") "Copyright (C) 2022 Ultra Librarian. All rights reserved."))
      (libsource (lib "C3216X5R1A686M160AC") (part "C3216X5R1A686M160AC"))
    )
    (comp (ref "C54")
      (value "C4532X7R1C336M250KC")
      (footprint "CAP_4532_TDK")
      (description "No Description Available")
      (fields (field (name "COPYRIGHT") "Copyright (C) 2022 Ultra Librarian. All rights reserved."))
      (libsource (lib "C4532X7R1C336M250KC") (part "C4532X7R1C336M250KC"))
    )
    (comp (ref "C55")
      (value "100n")
      (footprint "CAPC1608N")
      (description "Capacitor SMD Cer 100nF 10% 50V X7R 0603")
      (fields (field (name "TOLERANCE") "±10%") (field (name "Comment") "approved sub OK"))
      (libsource (lib "PBL - Capacitors") (part "CAPC_100n_0603"))
    )
    (comp (ref "C56")
      (value "10µ")
      (footprint "CAPMP2012X150USR")
      (description "Capacitor SMD Tantalum 10uF 20% 10V 0805")
      (fields (field (name "TOLERANCE") "±20%") (field (name "RATINGS") "10V"))
      (libsource (lib "PBL - Capacitors") (part "CAPT_10u_0805_10V"))
    )
    (comp (ref "C57")
      (value "100n")
      (footprint "CAPC1608N")
      (description "Capacitor SMD Cer 100nF 10% 50V X7R 0603")
      (fields (field (name "TOLERANCE") "±10%") (field (name "Comment") "approved sub OK"))
      (libsource (lib "PBL - Capacitors") (part "CAPC_100n_0603"))
    )
    (comp (ref "C58")
      (value "10µ")
      (footprint "CAPMP2012X150USR")
      (description "Capacitor SMD Tantalum 10uF 20% 10V 0805")
      (fields (field (name "TOLERANCE") "±20%") (field (name "RATINGS") "10V"))
      (libsource (lib "PBL - Capacitors") (part "CAPT_10u_0805_10V"))
    )
    (comp (ref "C59")
      (value "47p")
      (footprint "CAPC1608N")
      (description "Capacitor SMD Cer 47pF 0603")
      (fields (field (name "TOLERANCE") "±5%"))
      (libsource (lib "MB - Misc") (part "CAPC_47p_0603"))
    )
    (comp (ref "C60")
      (value "100n")
      (footprint "CAPC1608N")
      (description "Capacitor SMD Cer 100nF 10% 50V X7R 0603")
      (fields (field (name "TOLERANCE") "±10%") (field (name "Comment") "approved sub OK"))
      (libsource (lib "PBL - Capacitors") (part "CAPC_100n_0603"))
    )
    (comp (ref "C61")
      (value "10µ")
      (footprint "CAPMP2012X150USR")
      (description "Capacitor SMD Tantalum 10uF 20% 10V 0805")
      (fields (field (name "TOLERANCE") "±20%") (field (name "RATINGS") "10V"))
      (libsource (lib "PBL - Capacitors") (part "CAPT_10u_0805_10V"))
    )
    (comp (ref "C62")
      (value "100n")
      (footprint "CAPC1608N")
      (description "Capacitor SMD Cer 100nF 10% 50V X7R 0603")
      (fields (field (name "TOLERANCE") "±10%") (field (name "Comment") "approved sub OK"))
      (libsource (lib "PBL - Capacitors") (part "CAPC_100n_0603"))
    )
    (comp (ref "C63")
      (value "10µ")
      (footprint "CAPMP2012X150USR")
      (description "Capacitor SMD Tantalum 10uF 20% 10V 0805")
      (fields (field (name "TOLERANCE") "±20%") (field (name "RATINGS") "10V"))
      (libsource (lib "PBL - Capacitors") (part "CAPT_10u_0805_10V"))
    )
    (comp (ref "C64")
      (value "47p")
      (footprint "CAPC1608N")
      (description "Capacitor SMD Cer 47pF 0603")
      (fields (field (name "TOLERANCE") "±5%"))
      (libsource (lib "MB - Misc") (part "CAPC_47p_0603"))
    )
    (comp (ref "C65")
      (value "10µ")
      (footprint "CAPMP2012X150USR")
      (description "Capacitor SMD Tantalum 10uF 20% 10V 0805")
      (fields (field (name "TOLERANCE") "±20%") (field (name "RATINGS") "10V"))
      (libsource (lib "PBL - Capacitors") (part "CAPT_10u_0805_10V"))
    )
    (comp (ref "C66")
      (value "10µ")
      (footprint "CAPMP2012X150USR")
      (description "Capacitor SMD Tantalum 10uF 20% 10V 0805")
      (fields (field (name "TOLERANCE") "±20%") (field (name "RATINGS") "10V"))
      (libsource (lib "PBL - Capacitors") (part "CAPT_10u_0805_10V"))
    )
    (comp (ref "C67")
      (value "10µ")
      (footprint "CAPMP2012X150USR")
      (description "Capacitor SMD Tantalum 10uF 20% 10V 0805")
      (fields (field (name "TOLERANCE") "±20%") (field (name "RATINGS") "10V"))
      (libsource (lib "PBL - Capacitors") (part "CAPT_10u_0805_10V"))
    )
    (comp (ref "C68")
      (value "10µ")
      (footprint "CAPMP2012X150USR")
      (description "Capacitor SMD Tantalum 10uF 20% 10V 0805")
      (fields (field (name "TOLERANCE") "±20%") (field (name "RATINGS") "10V"))
      (libsource (lib "PBL - Capacitors") (part "CAPT_10u_0805_10V"))
    )
    (comp (ref "C69")
      (value "100n")
      (footprint "CAPC1608N")
      (description "Capacitor SMD Cer 100nF 10% 50V X7R 0603")
      (fields (field (name "TOLERANCE") "±10%") (field (name "Comment") "approved sub OK"))
      (libsource (lib "PBL - Capacitors") (part "CAPC_100n_0603"))
    )
    (comp (ref "C70")
      (value "100n")
      (footprint "CAPC1608N")
      (description "Capacitor SMD Cer 100nF 10% 50V X7R 0603")
      (fields (field (name "TOLERANCE") "±10%") (field (name "Comment") "approved sub OK"))
      (libsource (lib "PBL - Capacitors") (part "CAPC_100n_0603"))
    )
    (comp (ref "C71")
      (value "100n")
      (footprint "CAPC1608N")
      (description "Capacitor SMD Cer 100nF 10% 50V X7R 0603")
      (fields (field (name "TOLERANCE") "±10%") (field (name "Comment") "approved sub OK"))
      (libsource (lib "PBL - Capacitors") (part "CAPC_100n_0603"))
    )
    (comp (ref "C72")
      (value "100n")
      (footprint "CAPC1608N")
      (description "Capacitor SMD Cer 100nF 10% 50V X7R 0603")
      (fields (field (name "TOLERANCE") "±10%") (field (name "Comment") "approved sub OK"))
      (libsource (lib "PBL - Capacitors") (part "CAPC_100n_0603"))
    )
    (comp (ref "C73")
      (value "10µ")
      (footprint "CAPMP2012X150USR")
      (description "Capacitor SMD Tantalum 10uF 20% 10V 0805")
      (fields (field (name "TOLERANCE") "±20%") (field (name "RATINGS") "10V"))
      (libsource (lib "PBL - Capacitors") (part "CAPT_10u_0805_10V"))
    )
    (comp (ref "C74")
      (value "10µ")
      (footprint "CAPMP2012X150USR")
      (description "Capacitor SMD Tantalum 10uF 20% 10V 0805")
      (fields (field (name "TOLERANCE") "±20%") (field (name "RATINGS") "10V"))
      (libsource (lib "PBL - Capacitors") (part "CAPT_10u_0805_10V"))
    )
    (comp (ref "C75")
      (value "100n")
      (footprint "CAPC1608N")
      (description "Capacitor SMD Cer 100nF 10% 50V X7R 0603")
      (fields (field (name "TOLERANCE") "±10%") (field (name "Comment") "approved sub OK"))
      (libsource (lib "PBL - Capacitors") (part "CAPC_100n_0603"))
    )
    (comp (ref "C76")
      (value "100n")
      (footprint "CAPC1608N")
      (description "Capacitor SMD Cer 100nF 10% 50V X7R 0603")
      (fields (field (name "TOLERANCE") "±10%") (field (name "Comment") "approved sub OK"))
      (libsource (lib "PBL - Capacitors") (part "CAPC_100n_0603"))
    )
    (comp (ref "C77")
      (value "10µ")
      (footprint "CAPMP2012X150USR")
      (description "Capacitor SMD Tantalum 10uF 20% 10V 0805")
      (fields (field (name "TOLERANCE") "±20%") (field (name "RATINGS") "10V"))
      (libsource (lib "PBL - Capacitors") (part "CAPT_10u_0805_10V"))
    )
    (comp (ref "C78")
      (value "10µ")
      (footprint "CAPMP2012X150USR")
      (description "Capacitor SMD Tantalum 10uF 20% 10V 0805")
      (fields (field (name "TOLERANCE") "±20%") (field (name "RATINGS") "10V"))
      (libsource (lib "PBL - Capacitors") (part "CAPT_10u_0805_10V"))
    )
    (comp (ref "C79")
      (value "100n")
      (footprint "CAPC1608N")
      (description "Capacitor SMD Cer 100nF 10% 50V X7R 0603")
      (fields (field (name "TOLERANCE") "±10%") (field (name "Comment") "approved sub OK"))
      (libsource (lib "PBL - Capacitors") (part "CAPC_100n_0603"))
    )
    (comp (ref "C80")
      (value "100n")
      (footprint "CAPC1608N")
      (description "Capacitor SMD Cer 100nF 10% 50V X7R 0603")
      (fields (field (name "TOLERANCE") "±10%") (field (name "Comment") "approved sub OK"))
      (libsource (lib "PBL - Capacitors") (part "CAPC_100n_0603"))
    )
    (comp (ref "C81")
      (value "10µ")
      (footprint "CAPMP2012X150USR")
      (description "Capacitor SMD Tantalum 10uF 20% 10V 0805")
      (fields (field (name "TOLERANCE") "±20%") (field (name "RATINGS") "10V"))
      (libsource (lib "PBL - Capacitors") (part "CAPT_10u_0805_10V"))
    )
    (comp (ref "C82")
      (value "10µ")
      (footprint "CAPMP2012X150USR")
      (description "Capacitor SMD Tantalum 10uF 20% 10V 0805")
      (fields (field (name "TOLERANCE") "±20%") (field (name "RATINGS") "10V"))
      (libsource (lib "PBL - Capacitors") (part "CAPT_10u_0805_10V"))
    )
    (comp (ref "C83")
      (value "100n")
      (footprint "CAPC1608N")
      (description "Capacitor SMD Cer 100nF 10% 50V X7R 0603")
      (fields (field (name "TOLERANCE") "±10%") (field (name "Comment") "approved sub OK"))
      (libsource (lib "PBL - Capacitors") (part "CAPC_100n_0603"))
    )
    (comp (ref "C84")
      (value "100n")
      (footprint "CAPC1608N")
      (description "Capacitor SMD Cer 100nF 10% 50V X7R 0603")
      (fields (field (name "TOLERANCE") "±10%") (field (name "Comment") "approved sub OK"))
      (libsource (lib "PBL - Capacitors") (part "CAPC_100n_0603"))
    )
    (comp (ref "C85")
      (value "100n")
      (footprint "CAPC1608N")
      (description "Capacitor SMD Cer 100nF 10% 50V X7R 0603")
      (fields (field (name "TOLERANCE") "±10%") (field (name "Comment") "approved sub OK"))
      (libsource (lib "PBL - Capacitors") (part "CAPC_100n_0603"))
    )
    (comp (ref "C86")
      (value "10µ")
      (footprint "CAPMP2012X150USR")
      (description "Capacitor SMD Tantalum 10uF 20% 10V 0805")
      (fields (field (name "TOLERANCE") "±20%") (field (name "RATINGS") "10V"))
      (libsource (lib "PBL - Capacitors") (part "CAPT_10u_0805_10V"))
    )
    (comp (ref "C87")
      (value "100n")
      (footprint "CAPC1608N")
      (description "Capacitor SMD Cer 100nF 10% 50V X7R 0603")
      (fields (field (name "TOLERANCE") "±10%") (field (name "Comment") "approved sub OK"))
      (libsource (lib "PBL - Capacitors") (part "CAPC_100n_0603"))
    )
    (comp (ref "C88")
      (value "100n")
      (footprint "CAPC1608N")
      (description "Capacitor SMD Cer 100nF 10% 50V X7R 0603")
      (fields (field (name "TOLERANCE") "±10%") (field (name "Comment") "approved sub OK"))
      (libsource (lib "PBL - Capacitors") (part "CAPC_100n_0603"))
    )
    (comp (ref "C89")
      (value "10µ")
      (footprint "CAPMP2012X150USR")
      (description "Capacitor SMD Tantalum 10uF 20% 10V 0805")
      (fields (field (name "TOLERANCE") "±20%") (field (name "RATINGS") "10V"))
      (libsource (lib "PBL - Capacitors") (part "CAPT_10u_0805_10V"))
    )
    (comp (ref "C90")
      (value "100n")
      (footprint "CAPC1608N")
      (description "Capacitor SMD Cer 100nF 10% 50V X7R 0603")
      (fields (field (name "TOLERANCE") "±10%") (field (name "Comment") "approved sub OK"))
      (libsource (lib "PBL - Capacitors") (part "CAPC_100n_0603"))
    )
    (comp (ref "C91")
      (value "10µ")
      (footprint "CAPMP2012X150USR")
      (description "Capacitor SMD Tantalum 10uF 20% 10V 0805")
      (fields (field (name "TOLERANCE") "±20%") (field (name "RATINGS") "10V"))
      (libsource (lib "PBL - Capacitors") (part "CAPT_10u_0805_10V"))
    )
    (comp (ref "C92")
      (value "100n")
      (footprint "CAPC1608N")
      (description "Capacitor SMD Cer 100nF 10% 50V X7R 0603")
      (fields (field (name "TOLERANCE") "±10%") (field (name "Comment") "approved sub OK"))
      (libsource (lib "PBL - Capacitors") (part "CAPC_100n_0603"))
    )
    (comp (ref "C93")
      (value "100n")
      (footprint "CAPC1608N")
      (description "Capacitor SMD Cer 100nF 10% 50V X7R 0603")
      (fields (field (name "TOLERANCE") "±10%") (field (name "Comment") "approved sub OK"))
      (libsource (lib "PBL - Capacitors") (part "CAPC_100n_0603"))
    )
    (comp (ref "C94")
      (value "10µ")
      (footprint "CAPMP2012X150USR")
      (description "Capacitor SMD Tantalum 10uF 20% 10V 0805")
      (fields (field (name "TOLERANCE") "±20%") (field (name "RATINGS") "10V"))
      (libsource (lib "PBL - Capacitors") (part "CAPT_10u_0805_10V"))
    )
    (comp (ref "C95")
      (value "100n")
      (footprint "CAPC1608N")
      (description "Capacitor SMD Cer 100nF 10% 50V X7R 0603")
      (fields (field (name "TOLERANCE") "±10%") (field (name "Comment") "approved sub OK"))
      (libsource (lib "PBL - Capacitors") (part "CAPC_100n_0603"))
    )
    (comp (ref "C96")
      (value "10µ")
      (footprint "CAPMP2012X150USR")
      (description "Capacitor SMD Tantalum 10uF 20% 10V 0805")
      (fields (field (name "TOLERANCE") "±20%") (field (name "RATINGS") "10V"))
      (libsource (lib "PBL - Capacitors") (part "CAPT_10u_0805_10V"))
    )
    (comp (ref "C97")
      (value "47p")
      (footprint "CAPC1608N")
      (description "Capacitor SMD Cer 47pF 0603")
      (fields (field (name "TOLERANCE") "±5%"))
      (libsource (lib "MB - Misc") (part "CAPC_47p_0603"))
    )
    (comp (ref "C98")
      (value "100n")
      (footprint "CAPC1608N")
      (description "Capacitor SMD Cer 100nF 10% 50V X7R 0603")
      (fields (field (name "TOLERANCE") "±10%") (field (name "Comment") "approved sub OK"))
      (libsource (lib "PBL - Capacitors") (part "CAPC_100n_0603"))
    )
    (comp (ref "C99")
      (value "10µ")
      (footprint "CAPMP2012X150USR")
      (description "Capacitor SMD Tantalum 10uF 20% 10V 0805")
      (fields (field (name "TOLERANCE") "±20%") (field (name "RATINGS") "10V"))
      (libsource (lib "PBL - Capacitors") (part "CAPT_10u_0805_10V"))
    )
    (comp (ref "C100")
      (value "100n")
      (footprint "CAPC1608N")
      (description "Capacitor SMD Cer 100nF 10% 50V X7R 0603")
      (fields (field (name "TOLERANCE") "±10%") (field (name "Comment") "approved sub OK"))
      (libsource (lib "PBL - Capacitors") (part "CAPC_100n_0603"))
    )
    (comp (ref "C101")
      (value "10µ")
      (footprint "CAPMP2012X150USR")
      (description "Capacitor SMD Tantalum 10uF 20% 10V 0805")
      (fields (field (name "TOLERANCE") "±20%") (field (name "RATINGS") "10V"))
      (libsource (lib "PBL - Capacitors") (part "CAPT_10u_0805_10V"))
    )
    (comp (ref "C102")
      (value "47p")
      (footprint "CAPC1608N")
      (description "Capacitor SMD Cer 47pF 0603")
      (fields (field (name "TOLERANCE") "±5%"))
      (libsource (lib "MB - Misc") (part "CAPC_47p_0603"))
    )
    (comp (ref "C103")
      (value "C3216X5R1A686M160AC")
      (footprint "CAP_3216_TDK")
      (description "No Description Available")
      (fields (field (name "COPYRIGHT") "Copyright (C) 2022 Ultra Librarian. All rights reserved."))
      (libsource (lib "C3216X5R1A686M160AC") (part "C3216X5R1A686M160AC"))
    )
    (comp (ref "C104")
      (value "C4532X7R1C336M250KC")
      (footprint "CAP_4532_TDK")
      (description "No Description Available")
      (fields (field (name "COPYRIGHT") "Copyright (C) 2022 Ultra Librarian. All rights reserved."))
      (libsource (lib "C4532X7R1C336M250KC") (part "C4532X7R1C336M250KC"))
    )
    (comp (ref "C105")
      (value "100n")
      (footprint "CAPC1608N")
      (description "Capacitor SMD Cer 100nF 10% 50V X7R 0603")
      (fields (field (name "TOLERANCE") "±10%") (field (name "Comment") "approved sub OK"))
      (libsource (lib "PBL - Capacitors") (part "CAPC_100n_0603"))
    )
    (comp (ref "C106")
      (value "10µ")
      (footprint "CAPMP2012X150USR")
      (description "Capacitor SMD Tantalum 10uF 20% 10V 0805")
      (fields (field (name "TOLERANCE") "±20%") (field (name "RATINGS") "10V"))
      (libsource (lib "PBL - Capacitors") (part "CAPT_10u_0805_10V"))
    )
    (comp (ref "C107")
      (value "100n")
      (footprint "CAPC1608N")
      (description "Capacitor SMD Cer 100nF 10% 50V X7R 0603")
      (fields (field (name "TOLERANCE") "±10%") (field (name "Comment") "approved sub OK"))
      (libsource (lib "PBL - Capacitors") (part "CAPC_100n_0603"))
    )
    (comp (ref "C108")
      (value "10µ")
      (footprint "CAPMP2012X150USR")
      (description "Capacitor SMD Tantalum 10uF 20% 10V 0805")
      (fields (field (name "TOLERANCE") "±20%") (field (name "RATINGS") "10V"))
      (libsource (lib "PBL - Capacitors") (part "CAPT_10u_0805_10V"))
    )
    (comp (ref "C109")
      (value "47p")
      (footprint "CAPC1608N")
      (description "Capacitor SMD Cer 47pF 0603")
      (fields (field (name "TOLERANCE") "±5%"))
      (libsource (lib "MB - Misc") (part "CAPC_47p_0603"))
    )
    (comp (ref "C110")
      (value "100n")
      (footprint "CAPC1608N")
      (description "Capacitor SMD Cer 100nF 10% 50V X7R 0603")
      (fields (field (name "TOLERANCE") "±10%") (field (name "Comment") "approved sub OK"))
      (libsource (lib "PBL - Capacitors") (part "CAPC_100n_0603"))
    )
    (comp (ref "C111")
      (value "10µ")
      (footprint "CAPMP2012X150USR")
      (description "Capacitor SMD Tantalum 10uF 20% 10V 0805")
      (fields (field (name "TOLERANCE") "±20%") (field (name "RATINGS") "10V"))
      (libsource (lib "PBL - Capacitors") (part "CAPT_10u_0805_10V"))
    )
    (comp (ref "C112")
      (value "100n")
      (footprint "CAPC1608N")
      (description "Capacitor SMD Cer 100nF 10% 50V X7R 0603")
      (fields (field (name "TOLERANCE") "±10%") (field (name "Comment") "approved sub OK"))
      (libsource (lib "PBL - Capacitors") (part "CAPC_100n_0603"))
    )
    (comp (ref "C113")
      (value "10µ")
      (footprint "CAPMP2012X150USR")
      (description "Capacitor SMD Tantalum 10uF 20% 10V 0805")
      (fields (field (name "TOLERANCE") "±20%") (field (name "RATINGS") "10V"))
      (libsource (lib "PBL - Capacitors") (part "CAPT_10u_0805_10V"))
    )
    (comp (ref "C114")
      (value "47p")
      (footprint "CAPC1608N")
      (description "Capacitor SMD Cer 47pF 0603")
      (fields (field (name "TOLERANCE") "±5%"))
      (libsource (lib "MB - Misc") (part "CAPC_47p_0603"))
    )
    (comp (ref "C115")
      (value "C0603C221K5RACTU")
      (footprint "CAPC17595_87N_KEM")
      (description "No Description Available")
      (libsource (lib "C0603C221K5RACTU") (part "C0603C221K5RACTU"))
    )
    (comp (ref "C116")
      (value "CML0805C0G150JT50V")
      (footprint "CAP_CML_0805_.3pF-1500pF,4700pF_STP")
      (description "No Description Available")
      (libsource (lib "CML0805C0G150JT50V") (part "CML0805C0G150JT50V"))
    )
    (comp (ref "C117")
      (value "CML0805C0G150JT50V")
      (footprint "CAP_CML_0805_.3pF-1500pF,4700pF_STP")
      (description "No Description Available")
      (libsource (lib "CML0805C0G150JT50V") (part "CML0805C0G150JT50V"))
    )
    (comp (ref "C118")
      (value "100n")
      (footprint "CAPC1608N")
      (description "Capacitor SMD Cer 100nF 10% 50V X7R 0603")
      (fields (field (name "TOLERANCE") "±10%") (field (name "Comment") "approved sub OK"))
      (libsource (lib "PBL - Capacitors") (part "CAPC_100n_0603"))
    )
    (comp (ref "C119")
      (value "10µ")
      (footprint "CAPMP2012X150USR")
      (description "Capacitor SMD Tantalum 10uF 20% 10V 0805")
      (fields (field (name "TOLERANCE") "±20%") (field (name "RATINGS") "10V"))
      (libsource (lib "PBL - Capacitors") (part "CAPT_10u_0805_10V"))
    )
    (comp (ref "C120")
      (value "C0603C221K5RACTU")
      (footprint "CAPC17595_87N_KEM")
      (description "No Description Available")
      (libsource (lib "C0603C221K5RACTU") (part "C0603C221K5RACTU"))
    )
    (comp (ref "C121")
      (value "CML0805C0G3R0CT50V")
      (footprint "CAP_CML_0805_.3pF-1500pF,4700pF_STP")
      (description "No Description Available")
      (libsource (lib "CML0805C0G3R0CT50V") (part "CML0805C0G3R0CT50V"))
    )
    (comp (ref "C122")
      (value "100n")
      (footprint "CAPC1608N")
      (description "Capacitor SMD Cer 100nF 10% 50V X7R 0603")
      (fields (field (name "TOLERANCE") "±10%") (field (name "Comment") "approved sub OK"))
      (libsource (lib "PBL - Capacitors") (part "CAPC_100n_0603"))
    )
    (comp (ref "C123")
      (value "10µ")
      (footprint "CAPMP2012X150USR")
      (description "Capacitor SMD Tantalum 10uF 20% 10V 0805")
      (fields (field (name "TOLERANCE") "±20%") (field (name "RATINGS") "10V"))
      (libsource (lib "PBL - Capacitors") (part "CAPT_10u_0805_10V"))
    )
    (comp (ref "C124")
      (value "CML0805C0G3R0CT50V")
      (footprint "CAP_CML_0805_.3pF-1500pF,4700pF_STP")
      (description "No Description Available")
      (libsource (lib "CML0805C0G3R0CT50V") (part "CML0805C0G3R0CT50V"))
    )
    (comp (ref "C125")
      (value "CML0805C0G3R0CT50V")
      (footprint "CAP_CML_0805_.3pF-1500pF,4700pF_STP")
      (description "No Description Available")
      (libsource (lib "CML0805C0G3R0CT50V") (part "CML0805C0G3R0CT50V"))
    )
    (comp (ref "C126")
      (value "100n")
      (footprint "CAPC1608N")
      (description "Capacitor SMD Cer 100nF 10% 50V X7R 0603")
      (fields (field (name "TOLERANCE") "±10%") (field (name "Comment") "approved sub OK"))
      (libsource (lib "PBL - Capacitors") (part "CAPC_100n_0603"))
    )
    (comp (ref "C127")
      (value "100n")
      (footprint "CAPC1608N")
      (description "Capacitor SMD Cer 100nF 10% 50V X7R 0603")
      (fields (field (name "TOLERANCE") "±10%") (field (name "Comment") "approved sub OK"))
      (libsource (lib "PBL - Capacitors") (part "CAPC_100n_0603"))
    )
    (comp (ref "C128")
      (value "10µ")
      (footprint "CAPMP2012X150USR")
      (description "Capacitor SMD Tantalum 10uF 20% 10V 0805")
      (fields (field (name "TOLERANCE") "±20%") (field (name "RATINGS") "10V"))
      (libsource (lib "PBL - Capacitors") (part "CAPT_10u_0805_10V"))
    )
    (comp (ref "C129")
      (value "10µ")
      (footprint "CAPMP2012X150USR")
      (description "Capacitor SMD Tantalum 10uF 20% 10V 0805")
      (fields (field (name "TOLERANCE") "±20%") (field (name "RATINGS") "10V"))
      (libsource (lib "PBL - Capacitors") (part "CAPT_10u_0805_10V"))
    )
    (comp (ref "C130")
      (value "CML0805C0G3R0CT50V")
      (footprint "CAP_CML_0805_.3pF-1500pF,4700pF_STP")
      (description "No Description Available")
      (libsource (lib "CML0805C0G3R0CT50V") (part "CML0805C0G3R0CT50V"))
    )
    (comp (ref "C131")
      (value "100n")
      (footprint "CAPC1608N")
      (description "Capacitor SMD Cer 100nF 10% 50V X7R 0603")
      (fields (field (name "TOLERANCE") "±10%") (field (name "Comment") "approved sub OK"))
      (libsource (lib "PBL - Capacitors") (part "CAPC_100n_0603"))
    )
    (comp (ref "C132")
      (value "10µ")
      (footprint "CAPMP2012X150USR")
      (description "Capacitor SMD Tantalum 10uF 20% 10V 0805")
      (fields (field (name "TOLERANCE") "±20%") (field (name "RATINGS") "10V"))
      (libsource (lib "PBL - Capacitors") (part "CAPT_10u_0805_10V"))
    )
    (comp (ref "J1")
      (value "CONBNC002")
      (footprint "CONN_CONBN_LNX")
      (description "No Description Available")
      (libsource (lib "CONBNC002") (part "CONBNC002"))
    )
    (comp (ref "J2")
      (value "CONBNC002")
      (footprint "CONN_CONBN_LNX")
      (description "No Description Available")
      (libsource (lib "CONBNC002") (part "CONBNC002"))
    )
    (comp (ref "J3")
      (value "CONBNC002")
      (footprint "CONN_CONBN_LNX")
      (description "No Description Available")
      (libsource (lib "CONBNC002") (part "CONBNC002"))
    )
    (comp (ref "J4")
      (value "CONBNC002")
      (footprint "CONN_CONBN_LNX")
      (description "No Description Available")
      (libsource (lib "CONBNC002") (part "CONBNC002"))
    )
    (comp (ref "J5")
      (value "CONBNC002")
      (footprint "CONN_CONBN_LNX")
      (description "No Description Available")
      (libsource (lib "CONBNC002") (part "CONBNC002"))
    )
    (comp (ref "J6")
      (value "CONBNC002")
      (footprint "CONN_CONBN_LNX")
      (description "No Description Available")
      (libsource (lib "CONBNC002") (part "CONBNC002"))
    )
    (comp (ref "J7")
      (value "CONBNC002")
      (footprint "CONN_CONBN_LNX")
      (description "No Description Available")
      (libsource (lib "CONBNC002") (part "CONBNC002"))
    )
    (comp (ref "J8")
      (value "CONBNC002")
      (footprint "CONN_CONBN_LNX")
      (description "No Description Available")
      (libsource (lib "CONBNC002") (part "CONBNC002"))
    )
    (comp (ref "J9")
      (value "FCR7350R")
      (footprint "CONN1_FCR7350R_CLF")
      (description "No Description Available")
      (fields (field (name "COPYRIGHT") "Copyright (C) 2022 Ultra Librarian. All rights reserved."))
      (libsource (lib "FCR7350B") (part "FCR7350R"))
    )
    (comp (ref "J10")
      (value "FCR7350R")
      (footprint "CONN1_FCR7350R_CLF")
      (description "No Description Available")
      (fields (field (name "COPYRIGHT") "Copyright (C) 2022 Ultra Librarian. All rights reserved."))
      (libsource (lib "FCR7350B") (part "FCR7350R"))
    )
    (comp (ref "J11")
      (value "FCR7350R")
      (footprint "CONN1_FCR7350R_CLF")
      (description "No Description Available")
      (fields (field (name "COPYRIGHT") "Copyright (C) 2022 Ultra Librarian. All rights reserved."))
      (libsource (lib "FCR7350B") (part "FCR7350R"))
    )
    (comp (ref "J12")
      (value "FCR7350R")
      (footprint "CONN1_FCR7350R_CLF")
      (description "No Description Available")
      (fields (field (name "COPYRIGHT") "Copyright (C) 2022 Ultra Librarian. All rights reserved."))
      (libsource (lib "FCR7350B") (part "FCR7350R"))
    )
    (comp (ref "J13")
      (value "FCR7350R")
      (footprint "CONN1_FCR7350R_CLF")
      (description "No Description Available")
      (fields (field (name "COPYRIGHT") "Copyright (C) 2022 Ultra Librarian. All rights reserved."))
      (libsource (lib "FCR7350B") (part "FCR7350R"))
    )
    (comp (ref "J14")
      (value "FCR7350R")
      (footprint "CONN1_FCR7350R_CLF")
      (description "No Description Available")
      (fields (field (name "COPYRIGHT") "Copyright (C) 2022 Ultra Librarian. All rights reserved."))
      (libsource (lib "FCR7350B") (part "FCR7350R"))
    )
    (comp (ref "J15")
      (value "FCR7350R")
      (footprint "CONN1_FCR7350R_CLF")
      (description "No Description Available")
      (fields (field (name "COPYRIGHT") "Copyright (C) 2022 Ultra Librarian. All rights reserved."))
      (libsource (lib "FCR7350B") (part "FCR7350R"))
    )
    (comp (ref "J16")
      (value "DF17(4.0)-40DP-0.5V(57)")
      (footprint "HRS_DF17(4.0)-40DP-0.5V(57)")
      (libsource (lib "DF17_4.0_-40DP-0.5V_57_") (part "DF17(4.0)-40DP-0.5V(57)"))
    )
    (comp (ref "J17")
      (value "S1711-46R")
      (footprint "HARWIN_S1711-46R")
      (description "RFI SHIELD CLIP TIN SMD")
      (fields
        (field (name "MF") "Harwin Inc.")
        (field (name "CHECK_PRICES") "https://www.snapeda.com/parts/S1711-46R/Harwin%20Inc./view-part/2172610/?ref=eda")
      )
      (libsource (lib "S1711-46R") (part "S1711-46R"))
    )
    (comp (ref "J18")
      (value "FCR7350R")
      (footprint "CONN1_FCR7350R_CLF")
      (description "No Description Available")
      (fields (field (name "COPYRIGHT") "Copyright (C) 2022 Ultra Librarian. All rights reserved."))
      (libsource (lib "FCR7350B") (part "FCR7350R"))
    )
    (comp (ref "J19")
      (value "S1711-46R")
      (footprint "HARWIN_S1711-46R")
      (description "RFI SHIELD CLIP TIN SMD")
      (fields
        (field (name "MF") "Harwin Inc.")
        (field (name "CHECK_PRICES") "https://www.snapeda.com/parts/S1711-46R/Harwin%20Inc./view-part/2172610/?ref=eda")
      )
      (libsource (lib "S1711-46R") (part "S1711-46R"))
    )
    (comp (ref "J20")
      (value "FCR7350R")
      (footprint "CONN1_FCR7350R_CLF")
      (description "No Description Available")
      (fields (field (name "COPYRIGHT") "Copyright (C) 2022 Ultra Librarian. All rights reserved."))
      (libsource (lib "FCR7350B") (part "FCR7350R"))
    )
    (comp (ref "J21")
      (value "S1711-46R")
      (footprint "HARWIN_S1711-46R")
      (description "RFI SHIELD CLIP TIN SMD")
      (fields
        (field (name "MF") "Harwin Inc.")
        (field (name "CHECK_PRICES") "https://www.snapeda.com/parts/S1711-46R/Harwin%20Inc./view-part/2172610/?ref=eda")
      )
      (libsource (lib "S1711-46R") (part "S1711-46R"))
    )
    (comp (ref "J22")
      (value "VB335-75")
      (footprint "CONN5_VB335_CIN")
      (description "No Description Available")
      (libsource (lib "VB335-75") (part "VB335-75"))
    )
    (comp (ref "J23")
      (value "DF17(4.0)-40DP-0.5V(57)")
      (footprint "HRS_DF17(4.0)-40DP-0.5V(57)")
      (libsource (lib "DF17_4.0_-40DP-0.5V_57_") (part "DF17(4.0)-40DP-0.5V(57)"))
    )
    (comp (ref "J24")
      (value "S1711-46R")
      (footprint "HARWIN_S1711-46R")
      (description "RFI SHIELD CLIP TIN SMD")
      (fields
        (field (name "MF") "Harwin Inc.")
        (field (name "CHECK_PRICES") "https://www.snapeda.com/parts/S1711-46R/Harwin%20Inc./view-part/2172610/?ref=eda")
      )
      (libsource (lib "S1711-46R") (part "S1711-46R"))
    )
    (comp (ref "J25")
      (value "FCR7350R")
      (footprint "CONN1_FCR7350R_CLF")
      (description "No Description Available")
      (fields (field (name "COPYRIGHT") "Copyright (C) 2022 Ultra Librarian. All rights reserved."))
      (libsource (lib "FCR7350B") (part "FCR7350R"))
    )
    (comp (ref "J26")
      (value "FCR7350R")
      (footprint "CONN1_FCR7350R_CLF")
      (description "No Description Available")
      (fields (field (name "COPYRIGHT") "Copyright (C) 2022 Ultra Librarian. All rights reserved."))
      (libsource (lib "FCR7350B") (part "FCR7350R"))
    )
    (comp (ref "J27")
      (value "VB335-75")
      (footprint "CONN5_VB335_CIN")
      (description "No Description Available")
      (libsource (lib "VB335-75") (part "VB335-75"))
    )
    (comp (ref "J28")
      (value "FCR7350R")
      (footprint "CONN1_FCR7350R_CLF")
      (description "No Description Available")
      (fields (field (name "COPYRIGHT") "Copyright (C) 2022 Ultra Librarian. All rights reserved."))
      (libsource (lib "FCR7350B") (part "FCR7350R"))
    )
    (comp (ref "J29")
      (value "FCR7350R")
      (footprint "CONN1_FCR7350R_CLF")
      (description "No Description Available")
      (fields (field (name "COPYRIGHT") "Copyright (C) 2022 Ultra Librarian. All rights reserved."))
      (libsource (lib "FCR7350B") (part "FCR7350R"))
    )
    (comp (ref "J30")
      (value "DF17(4.0)-40DP-0.5V(57)")
      (footprint "HRS_DF17(4.0)-40DP-0.5V(57)")
      (libsource (lib "DF17_4.0_-40DP-0.5V_57_") (part "DF17(4.0)-40DP-0.5V(57)"))
    )
    (comp (ref "J31")
      (value "901200761")
      (footprint "CONN_90120-0761_MOL")
      (description "No Description Available")
      (fields (field (name "COPYRIGHT") "Copyright (C) 2022 Ultra Librarian. All rights reserved."))
      (libsource (lib "901200761") (part "901200761"))
    )
    (comp (ref "J32")
      (value "DF17(4.0)-40DP-0.5V(57)")
      (footprint "HRS_DF17(4.0)-40DP-0.5V(57)")
      (libsource (lib "DF17_4.0_-40DP-0.5V_57_") (part "DF17(4.0)-40DP-0.5V(57)"))
    )
    (comp (ref "J33")
      (value "TSW-132-09-G-T")
      (footprint "HDRV96W64P254_3X32_8128X749X838P")
      (description "CONN HEADER 96 POS .100\"")
      (libsource (lib "HEADER_3x32") (part "TSW-132-09-G-T"))
    )
    (comp (ref "J34")
      (value "ASP-127797-01")
      (footprint "SAMTEC_ASP-127797-01")
      (description "160 Position Connector Array, Male Pins Surface Mount Gold")
      (fields (field (name "MF") "Samtec Inc."))
      (libsource (lib "ASP-127797-01") (part "ASP-127797-01"))
    )
    (comp (ref "J35")
      (value "901200761")
      (footprint "CONN_90120-0761_MOL")
      (description "No Description Available")
      (fields (field (name "COPYRIGHT") "Copyright (C) 2022 Ultra Librarian. All rights reserved."))
      (libsource (lib "901200761") (part "901200761"))
    )
    (comp (ref "J36")
      (value "CONBNC002")
      (footprint "CONN_CONBN_LNX")
      (description "No Description Available")
      (libsource (lib "CONBNC002") (part "CONBNC002"))
    )
    (comp (ref "J37")
      (value "CONBNC002")
      (footprint "CONN_CONBN_LNX")
      (description "No Description Available")
      (libsource (lib "CONBNC002") (part "CONBNC002"))
    )
    (comp (ref "J38")
      (value "CONBNC002")
      (footprint "CONN_CONBN_LNX")
      (description "No Description Available")
      (libsource (lib "CONBNC002") (part "CONBNC002"))
    )
    (comp (ref "J39")
      (value "CONBNC002")
      (footprint "CONN_CONBN_LNX")
      (description "No Description Available")
      (libsource (lib "CONBNC002") (part "CONBNC002"))
    )
    (comp (ref "J40")
      (value "CONBNC002")
      (footprint "CONN_CONBN_LNX")
      (description "No Description Available")
      (libsource (lib "CONBNC002") (part "CONBNC002"))
    )
    (comp (ref "J41")
      (value "CONBNC002")
      (footprint "CONN_CONBN_LNX")
      (description "No Description Available")
      (libsource (lib "CONBNC002") (part "CONBNC002"))
    )
    (comp (ref "J42")
      (value "CONBNC002")
      (footprint "CONN_CONBN_LNX")
      (description "No Description Available")
      (libsource (lib "CONBNC002") (part "CONBNC002"))
    )
    (comp (ref "P1")
      (value "SMB")
      (footprint "SMB_V-RJ45")
      (description "SMB Straight Connector")
      (fields (field (name "PUBLISHER") "Altium Limited"))
      (libsource (lib "Miscellaneous Connectors") (part "SMB"))
    )
    (comp (ref "P2")
      (value "SMB")
      (footprint "SMB_V-RJ45")
      (description "SMB Straight Connector")
      (fields (field (name "PUBLISHER") "Altium Limited"))
      (libsource (lib "Miscellaneous Connectors") (part "SMB"))
    )
    (comp (ref "P3")
      (value "Header 2")
      (footprint "HDR1X2")
      (description "Header, 2-Pin")
      (fields (field (name "PUBLISHER") "Altium Limited"))
      (libsource (lib "Miscellaneous Connectors") (part "Header 2"))
    )
    (comp (ref "P4")
      (value "SMB")
      (footprint "SMB_V-RJ45")
      (description "SMB Straight Connector")
      (fields (field (name "PUBLISHER") "Altium Limited"))
      (libsource (lib "Miscellaneous Connectors") (part "SMB"))
    )
    (comp (ref "P5")
      (value "Header 3")
      (footprint "HDR1X3")
      (description "Header, 3-Pin")
      (fields (field (name "PUBLISHER") "Altium Limited"))
      (libsource (lib "Miscellaneous Connectors") (part "Header 3"))
    )
    (comp (ref "P6")
      (value "Header 3")
      (footprint "HDR1X3")
      (description "Header, 3-Pin")
      (fields (field (name "PUBLISHER") "Altium Limited"))
      (libsource (lib "Miscellaneous Connectors") (part "Header 3"))
    )
    (comp (ref "P7")
      (value "Header 3")
      (footprint "HDR1X3")
      (description "Header, 3-Pin")
      (fields (field (name "PUBLISHER") "Altium Limited"))
      (libsource (lib "Miscellaneous Connectors") (part "Header 3"))
    )
    (comp (ref "P8")
      (value "Header 3")
      (footprint "HDR1X3")
      (description "Header, 3-Pin")
      (fields (field (name "PUBLISHER") "Altium Limited"))
      (libsource (lib "Miscellaneous Connectors") (part "Header 3"))
    )
    (comp (ref "P9")
      (value "SMB")
      (footprint "SMB_V-RJ45")
      (description "SMB Straight Connector")
      (fields (field (name "PUBLISHER") "Altium Limited"))
      (libsource (lib "Miscellaneous Connectors") (part "SMB"))
    )
    (comp (ref "P10")
      (value "SMB")
      (footprint "SMB_V-RJ45")
      (description "SMB Straight Connector")
      (fields (field (name "PUBLISHER") "Altium Limited"))
      (libsource (lib "Miscellaneous Connectors") (part "SMB"))
    )
    (comp (ref "P11")
      (value "Header 2")
      (footprint "HDR1X2")
      (description "Header, 2-Pin")
      (fields (field (name "PUBLISHER") "Altium Limited"))
      (libsource (lib "Miscellaneous Connectors") (part "Header 2"))
    )
    (comp (ref "P12")
      (value "SMB")
      (footprint "SMB_V-RJ45")
      (description "SMB Straight Connector")
      (fields (field (name "PUBLISHER") "Altium Limited"))
      (libsource (lib "Miscellaneous Connectors") (part "SMB"))
    )
    (comp (ref "P13")
      (value "Header 2")
      (footprint "HDR1X2")
      (description "Header, 2-Pin")
      (fields (field (name "PUBLISHER") "Altium Limited"))
      (libsource (lib "Miscellaneous Connectors") (part "Header 2"))
    )
    (comp (ref "P14")
      (value "Header 2")
      (footprint "HDR1X2")
      (description "Header, 2-Pin")
      (fields (field (name "PUBLISHER") "Altium Limited"))
      (libsource (lib "Miscellaneous Connectors") (part "Header 2"))
    )
    (comp (ref "P15")
      (value "SMB")
      (footprint "SMB_V-RJ45")
      (description "SMB Straight Connector")
      (fields (field (name "PUBLISHER") "Altium Limited"))
      (libsource (lib "Miscellaneous Connectors") (part "SMB"))
    )
    (comp (ref "P16")
      (value "Header 2")
      (footprint "HDR1X2")
      (description "Header, 2-Pin")
      (fields (field (name "PUBLISHER") "Altium Limited"))
      (libsource (lib "Miscellaneous Connectors") (part "Header 2"))
    )
    (comp (ref "P17")
      (value "SMB")
      (footprint "SMB_V-RJ45")
      (description "SMB Straight Connector")
      (fields (field (name "PUBLISHER") "Altium Limited"))
      (libsource (lib "Miscellaneous Connectors") (part "SMB"))
    )
    (comp (ref "P18")
      (value "Header 3")
      (footprint "HDR1X3")
      (description "Header, 3-Pin")
      (fields (field (name "PUBLISHER") "Altium Limited"))
      (libsource (lib "Miscellaneous Connectors") (part "Header 3"))
    )
    (comp (ref "P19")
      (value "SMB")
      (footprint "SMB_V-RJ45")
      (description "SMB Straight Connector")
      (fields (field (name "PUBLISHER") "Altium Limited"))
      (libsource (lib "Miscellaneous Connectors") (part "SMB"))
    )
    (comp (ref "P20")
      (value "Header 2")
      (footprint "HDR1X2")
      (description "Header, 2-Pin")
      (fields (field (name "PUBLISHER") "Altium Limited"))
      (libsource (lib "Miscellaneous Connectors") (part "Header 2"))
    )
    (comp (ref "P21")
      (value "Header 2")
      (footprint "HDR1X2")
      (description "Header, 2-Pin")
      (fields (field (name "PUBLISHER") "Altium Limited"))
      (libsource (lib "Miscellaneous Connectors") (part "Header 2"))
    )
    (comp (ref "P22")
      (value "SMB")
      (footprint "SMB_V-RJ45")
      (description "SMB Straight Connector")
      (fields (field (name "PUBLISHER") "Altium Limited"))
      (libsource (lib "Miscellaneous Connectors") (part "SMB"))
    )
    (comp (ref "P23")
      (value "Header 2")
      (footprint "HDR1X2")
      (description "Header, 2-Pin")
      (fields (field (name "PUBLISHER") "Altium Limited"))
      (libsource (lib "Miscellaneous Connectors") (part "Header 2"))
    )
    (comp (ref "P24")
      (value "Header 2")
      (footprint "HDR1X2")
      (description "Header, 2-Pin")
      (fields (field (name "PUBLISHER") "Altium Limited"))
      (libsource (lib "Miscellaneous Connectors") (part "Header 2"))
    )
    (comp (ref "P25")
      (value "SMB")
      (footprint "SMB_V-RJ45")
      (description "SMB Straight Connector")
      (fields (field (name "PUBLISHER") "Altium Limited"))
      (libsource (lib "Miscellaneous Connectors") (part "SMB"))
    )
    (comp (ref "P26")
      (value "Header 2")
      (footprint "HDR1X2")
      (description "Header, 2-Pin")
      (fields (field (name "PUBLISHER") "Altium Limited"))
      (libsource (lib "Miscellaneous Connectors") (part "Header 2"))
    )
    (comp (ref "P27")
      (value "SMB")
      (footprint "SMB_V-RJ45")
      (description "SMB Straight Connector")
      (fields (field (name "PUBLISHER") "Altium Limited"))
      (libsource (lib "Miscellaneous Connectors") (part "SMB"))
    )
    (comp (ref "P28")
      (value "Header 4X2")
      (footprint "HDR2X4")
      (description "Header, 4-Pin, Dual row")
      (fields (field (name "PUBLISHER") "Altium Limited"))
      (libsource (lib "Miscellaneous Connectors") (part "Header 4X2"))
    )
    (comp (ref "P29")
      (value "Header 2")
      (footprint "HDR1X2")
      (description "Header, 2-Pin")
      (fields (field (name "PUBLISHER") "Altium Limited"))
      (libsource (lib "Miscellaneous Connectors") (part "Header 2"))
    )
    (comp (ref "P30")
      (value "SMB")
      (footprint "SMB_V-RJ45")
      (description "SMB Straight Connector")
      (fields (field (name "PUBLISHER") "Altium Limited"))
      (libsource (lib "Miscellaneous Connectors") (part "SMB"))
    )
    (comp (ref "P31")
      (value "SMB")
      (footprint "SMB_V-RJ45")
      (description "SMB Straight Connector")
      (fields (field (name "PUBLISHER") "Altium Limited"))
      (libsource (lib "Miscellaneous Connectors") (part "SMB"))
    )
    (comp (ref "P32")
      (value "SMB")
      (footprint "SMB_V-RJ45")
      (description "SMB Straight Connector")
      (fields (field (name "PUBLISHER") "Altium Limited"))
      (libsource (lib "Miscellaneous Connectors") (part "SMB"))
    )
    (comp (ref "P33")
      (value "SMB")
      (footprint "SMB_V-RJ45")
      (description "SMB Straight Connector")
      (fields (field (name "PUBLISHER") "Altium Limited"))
      (libsource (lib "Miscellaneous Connectors") (part "SMB"))
    )
    (comp (ref "P34")
      (value "Header 2")
      (footprint "HDR1X2")
      (description "Header, 2-Pin")
      (fields (field (name "PUBLISHER") "Altium Limited"))
      (libsource (lib "Miscellaneous Connectors") (part "Header 2"))
    )
    (comp (ref "P35")
      (value "SMB")
      (footprint "SMB_V-RJ45")
      (description "SMB Straight Connector")
      (fields (field (name "PUBLISHER") "Altium Limited"))
      (libsource (lib "Miscellaneous Connectors") (part "SMB"))
    )
    (comp (ref "P36")
      (value "SMB")
      (footprint "SMB_V-RJ45")
      (description "SMB Straight Connector")
      (fields (field (name "PUBLISHER") "Altium Limited"))
      (libsource (lib "Miscellaneous Connectors") (part "SMB"))
    )
    (comp (ref "P37")
      (value "Header 2")
      (footprint "HDR1X2")
      (description "Header, 2-Pin")
      (fields (field (name "PUBLISHER") "Altium Limited"))
      (libsource (lib "Miscellaneous Connectors") (part "Header 2"))
    )
    (comp (ref "P38")
      (value "SMB")
      (footprint "SMB_V-RJ45")
      (description "SMB Straight Connector")
      (fields (field (name "PUBLISHER") "Altium Limited"))
      (libsource (lib "Miscellaneous Connectors") (part "SMB"))
    )
    (comp (ref "P39")
      (value "SMB")
      (footprint "SMB_V-RJ45")
      (description "SMB Straight Connector")
      (fields (field (name "PUBLISHER") "Altium Limited"))
      (libsource (lib "Miscellaneous Connectors") (part "SMB"))
    )
    (comp (ref "P40")
      (value "SMB")
      (footprint "SMB_V-RJ45")
      (description "SMB Straight Connector")
      (fields (field (name "PUBLISHER") "Altium Limited"))
      (libsource (lib "Miscellaneous Connectors") (part "SMB"))
    )
    (comp (ref "P41")
      (value "SMB")
      (footprint "SMB_V-RJ45")
      (description "SMB Straight Connector")
      (fields (field (name "PUBLISHER") "Altium Limited"))
      (libsource (lib "Miscellaneous Connectors") (part "SMB"))
    )
    (comp (ref "P42")
      (value "Header 2")
      (footprint "HDR1X2")
      (description "Header, 2-Pin")
      (fields (field (name "PUBLISHER") "Altium Limited"))
      (libsource (lib "Miscellaneous Connectors") (part "Header 2"))
    )
    (comp (ref "P43")
      (value "SMB")
      (footprint "SMB_V-RJ45")
      (description "SMB Straight Connector")
      (fields (field (name "PUBLISHER") "Altium Limited"))
      (libsource (lib "Miscellaneous Connectors") (part "SMB"))
    )
    (comp (ref "P44")
      (value "SMB")
      (footprint "SMB_V-RJ45")
      (description "SMB Straight Connector")
      (fields (field (name "PUBLISHER") "Altium Limited"))
      (libsource (lib "Miscellaneous Connectors") (part "SMB"))
    )
    (comp (ref "P45")
      (value "Header 2")
      (footprint "HDR1X2")
      (description "Header, 2-Pin")
      (fields (field (name "PUBLISHER") "Altium Limited"))
      (libsource (lib "Miscellaneous Connectors") (part "Header 2"))
    )
    (comp (ref "P46")
      (value "SMB")
      (footprint "SMB_V-RJ45")
      (description "SMB Straight Connector")
      (fields (field (name "PUBLISHER") "Altium Limited"))
      (libsource (lib "Miscellaneous Connectors") (part "SMB"))
    )
    (comp (ref "P47")
      (value "SMB")
      (footprint "SMB_V-RJ45")
      (description "SMB Straight Connector")
      (fields (field (name "PUBLISHER") "Altium Limited"))
      (libsource (lib "Miscellaneous Connectors") (part "SMB"))
    )
    (comp (ref "P48")
      (value "Header 2")
      (footprint "HDR1X2")
      (description "Header, 2-Pin")
      (fields (field (name "PUBLISHER") "Altium Limited"))
      (libsource (lib "Miscellaneous Connectors") (part "Header 2"))
    )
    (comp (ref "P49")
      (value "SMB")
      (footprint "SMB_V-RJ45")
      (description "SMB Straight Connector")
      (fields (field (name "PUBLISHER") "Altium Limited"))
      (libsource (lib "Miscellaneous Connectors") (part "SMB"))
    )
    (comp (ref "P50")
      (value "SMB")
      (footprint "SMB_V-RJ45")
      (description "SMB Straight Connector")
      (fields (field (name "PUBLISHER") "Altium Limited"))
      (libsource (lib "Miscellaneous Connectors") (part "SMB"))
    )
    (comp (ref "P51")
      (value "SMB")
      (footprint "SMB_V-RJ45")
      (description "SMB Straight Connector")
      (fields (field (name "PUBLISHER") "Altium Limited"))
      (libsource (lib "Miscellaneous Connectors") (part "SMB"))
    )
    (comp (ref "P52")
      (value "SMB")
      (footprint "SMB_V-RJ45")
      (description "SMB Straight Connector")
      (fields (field (name "PUBLISHER") "Altium Limited"))
      (libsource (lib "Miscellaneous Connectors") (part "SMB"))
    )
    (comp (ref "P53")
      (value "SMB")
      (footprint "SMB_V-RJ45")
      (description "SMB Straight Connector")
      (fields (field (name "PUBLISHER") "Altium Limited"))
      (libsource (lib "Miscellaneous Connectors") (part "SMB"))
    )
    (comp (ref "P54")
      (value "SMB")
      (footprint "SMB_V-RJ45")
      (description "SMB Straight Connector")
      (fields (field (name "PUBLISHER") "Altium Limited"))
      (libsource (lib "Miscellaneous Connectors") (part "SMB"))
    )
    (comp (ref "P55")
      (value "Header 3")
      (footprint "HDR1X3")
      (description "Header, 3-Pin")
      (fields (field (name "PUBLISHER") "Altium Limited"))
      (libsource (lib "Miscellaneous Connectors") (part "Header 3"))
    )
    (comp (ref "P56")
      (value "Header 3")
      (footprint "HDR1X3")
      (description "Header, 3-Pin")
      (fields (field (name "PUBLISHER") "Altium Limited"))
      (libsource (lib "Miscellaneous Connectors") (part "Header 3"))
    )
    (comp (ref "P57")
      (value "Header 3")
      (footprint "HDR1X3")
      (description "Header, 3-Pin")
      (fields (field (name "PUBLISHER") "Altium Limited"))
      (libsource (lib "Miscellaneous Connectors") (part "Header 3"))
    )
    (comp (ref "P58")
      (value "Header 3")
      (footprint "HDR1X3")
      (description "Header, 3-Pin")
      (fields (field (name "PUBLISHER") "Altium Limited"))
      (libsource (lib "Miscellaneous Connectors") (part "Header 3"))
    )
    (comp (ref "P59")
      (value "Header 3")
      (footprint "HDR1X3")
      (description "Header, 3-Pin")
      (fields (field (name "PUBLISHER") "Altium Limited"))
      (libsource (lib "Miscellaneous Connectors") (part "Header 3"))
    )
    (comp (ref "P60")
      (value "Header 2")
      (footprint "HDR1X2")
      (description "Header, 2-Pin")
      (fields (field (name "PUBLISHER") "Altium Limited"))
      (libsource (lib "Miscellaneous Connectors") (part "Header 2"))
    )
    (comp (ref "P61")
      (value "Header 2")
      (footprint "HDR1X2")
      (description "Header, 2-Pin")
      (fields (field (name "PUBLISHER") "Altium Limited"))
      (libsource (lib "Miscellaneous Connectors") (part "Header 2"))
    )
    (comp (ref "P62")
      (value "Header 2")
      (footprint "HDR1X2")
      (description "Header, 2-Pin")
      (fields (field (name "PUBLISHER") "Altium Limited"))
      (libsource (lib "Miscellaneous Connectors") (part "Header 2"))
    )
    (comp (ref "P63")
      (value "Header 2")
      (footprint "HDR1X2")
      (description "Header, 2-Pin")
      (fields (field (name "PUBLISHER") "Altium Limited"))
      (libsource (lib "Miscellaneous Connectors") (part "Header 2"))
    )
    (comp (ref "P64")
      (value "Header 2")
      (footprint "HDR1X2")
      (description "Header, 2-Pin")
      (fields (field (name "PUBLISHER") "Altium Limited"))
      (libsource (lib "Miscellaneous Connectors") (part "Header 2"))
    )
    (comp (ref "P65")
      (value "Header 2")
      (footprint "HDR1X2")
      (description "Header, 2-Pin")
      (fields (field (name "PUBLISHER") "Altium Limited"))
      (libsource (lib "Miscellaneous Connectors") (part "Header 2"))
    )
    (comp (ref "P66")
      (value "Header 2")
      (footprint "HDR1X2")
      (description "Header, 2-Pin")
      (fields (field (name "PUBLISHER") "Altium Limited"))
      (libsource (lib "Miscellaneous Connectors") (part "Header 2"))
    )
    (comp (ref "P67")
      (value "Header 2")
      (footprint "HDR1X2")
      (description "Header, 2-Pin")
      (fields (field (name "PUBLISHER") "Altium Limited"))
      (libsource (lib "Miscellaneous Connectors") (part "Header 2"))
    )
    (comp (ref "P68")
      (value "Header 2")
      (footprint "HDR1X2")
      (description "Header, 2-Pin")
      (fields (field (name "PUBLISHER") "Altium Limited"))
      (libsource (lib "Miscellaneous Connectors") (part "Header 2"))
    )
    (comp (ref "P69")
      (value "Header 2")
      (footprint "HDR1X2")
      (description "Header, 2-Pin")
      (fields (field (name "PUBLISHER") "Altium Limited"))
      (libsource (lib "Miscellaneous Connectors") (part "Header 2"))
    )
    (comp (ref "P70")
      (value "Header 4X2")
      (footprint "HDR2X4")
      (description "Header, 4-Pin, Dual row")
      (fields (field (name "PUBLISHER") "Altium Limited"))
      (libsource (lib "Miscellaneous Connectors") (part "Header 4X2"))
    )
    (comp (ref "P71")
      (value "Header 3")
      (footprint "HDR1X3")
      (description "Header, 3-Pin")
      (fields (field (name "PUBLISHER") "Altium Limited"))
      (libsource (lib "Miscellaneous Connectors") (part "Header 3"))
    )
    (comp (ref "P72")
      (value "Header 3")
      (footprint "HDR1X3")
      (description "Header, 3-Pin")
      (fields (field (name "PUBLISHER") "Altium Limited"))
      (libsource (lib "Miscellaneous Connectors") (part "Header 3"))
    )
    (comp (ref "P73")
      (value "Header 3")
      (footprint "HDR1X3")
      (description "Header, 3-Pin")
      (fields (field (name "PUBLISHER") "Altium Limited"))
      (libsource (lib "Miscellaneous Connectors") (part "Header 3"))
    )
    (comp (ref "P74")
      (value "Header 3")
      (footprint "HDR1X3")
      (description "Header, 3-Pin")
      (fields (field (name "PUBLISHER") "Altium Limited"))
      (libsource (lib "Miscellaneous Connectors") (part "Header 3"))
    )
    (comp (ref "P75")
      (value "Header 3")
      (footprint "HDR1X3")
      (description "Header, 3-Pin")
      (fields (field (name "PUBLISHER") "Altium Limited"))
      (libsource (lib "Miscellaneous Connectors") (part "Header 3"))
    )
    (comp (ref "P76")
      (value "Header 3")
      (footprint "HDR1X3")
      (description "Header, 3-Pin")
      (fields (field (name "PUBLISHER") "Altium Limited"))
      (libsource (lib "Miscellaneous Connectors") (part "Header 3"))
    )
    (comp (ref "P77")
      (value "Header 3")
      (footprint "HDR1X3")
      (description "Header, 3-Pin")
      (fields (field (name "PUBLISHER") "Altium Limited"))
      (libsource (lib "Miscellaneous Connectors") (part "Header 3"))
    )
    (comp (ref "P78")
      (value "Header 3")
      (footprint "HDR1X3")
      (description "Header, 3-Pin")
      (fields (field (name "PUBLISHER") "Altium Limited"))
      (libsource (lib "Miscellaneous Connectors") (part "Header 3"))
    )
    (comp (ref "P79")
      (value "Header 3")
      (footprint "HDR1X3")
      (description "Header, 3-Pin")
      (fields (field (name "PUBLISHER") "Altium Limited"))
      (libsource (lib "Miscellaneous Connectors") (part "Header 3"))
    )
    (comp (ref "P80")
      (value "Header 2")
      (footprint "HDR1X2")
      (description "Header, 2-Pin")
      (fields (field (name "PUBLISHER") "Altium Limited"))
      (libsource (lib "Miscellaneous Connectors") (part "Header 2"))
    )
    (comp (ref "P81")
      (value "Header 2")
      (footprint "HDR1X2")
      (description "Header, 2-Pin")
      (fields (field (name "PUBLISHER") "Altium Limited"))
      (libsource (lib "") (part "Header 2_1"))
    )
    (comp (ref "P82")
      (value "Header 2")
      (footprint "HDR1X2")
      (description "Header, 2-Pin")
      (fields (field (name "PUBLISHER") "Altium Limited"))
      (libsource (lib "") (part "Header 2_1"))
    )
    (comp (ref "P83")
      (value "Header 2")
      (footprint "HDR1X2")
      (description "Header, 2-Pin")
      (fields (field (name "PUBLISHER") "Altium Limited"))
      (libsource (lib "Miscellaneous Connectors") (part "Header 2"))
    )
    (comp (ref "P84")
      (value "Header 2")
      (footprint "HDR1X2")
      (description "Header, 2-Pin")
      (fields (field (name "PUBLISHER") "Altium Limited"))
      (libsource (lib "Miscellaneous Connectors") (part "Header 2"))
    )
    (comp (ref "P85")
      (value "Header 3")
      (footprint "HDR1X3")
      (description "Header, 3-Pin")
      (fields (field (name "PUBLISHER") "Altium Limited"))
      (libsource (lib "Miscellaneous Connectors") (part "Header 3"))
    )
    (comp (ref "P86")
      (value "Header 2")
      (footprint "HDR1X2")
      (description "Header, 2-Pin")
      (fields (field (name "PUBLISHER") "Altium Limited"))
      (libsource (lib "Miscellaneous Connectors") (part "Header 2"))
    )
    (comp (ref "P87")
      (value "Header 2")
      (footprint "HDR1X2")
      (description "Header, 2-Pin")
      (fields (field (name "PUBLISHER") "Altium Limited"))
      (libsource (lib "Miscellaneous Connectors") (part "Header 2"))
    )
    (comp (ref "P88")
      (value "Header 2")
      (footprint "HDR1X2")
      (description "Header, 2-Pin")
      (fields (field (name "PUBLISHER") "Altium Limited"))
      (libsource (lib "") (part "Header 2_1"))
    )
    (comp (ref "P89")
      (value "Header 3")
      (footprint "HDR1X3")
      (description "Header, 3-Pin")
      (fields (field (name "PUBLISHER") "Altium Limited"))
      (libsource (lib "") (part "Header 3_1"))
    )
    (comp (ref "R1")
      (value "RMCF0603ZT0R00")
      (footprint "STA_RMCF0603_STP")
      (description "No Description Available")
      (libsource (lib "RMCF0603ZT0R00") (part "RMCF0603ZT0R00"))
    )
    (comp (ref "R2")
      (value "RMCF0603ZT0R00")
      (footprint "STA_RMCF0603_STP")
      (description "No Description Available")
      (libsource (lib "RMCF0603ZT0R00") (part "RMCF0603ZT0R00"))
    )
    (comp (ref "R3")
      (value "RMCF0603ZT0R00")
      (footprint "STA_RMCF0603_STP")
      (description "No Description Available")
      (libsource (lib "RMCF0603ZT0R00") (part "RMCF0603ZT0R00"))
    )
    (comp (ref "R4")
      (value "ERA6AEB1021V")
      (footprint "RES_ERA6A_0805_PAN")
      (description "No Description Available")
      (fields (field (name "ALTIUM_VALUE") "1.02k"))
      (libsource (lib "ERA6AEB1021V") (part "ERA6AEB1021V"))
    )
    (comp (ref "R5")
      (value "ERA-6AEB102V")
      (footprint "RC0805N_PAN")
      (description "No Description Available")
      (fields (field (name "ALTIUM_VALUE") "1k"))
      (libsource (lib "ERA-6AEB102V") (part "ERA-6AEB102V"))
    )
    (comp (ref "R6")
      (value "ERA-6AEB102V")
      (footprint "RC0805N_PAN")
      (description "No Description Available")
      (fields (field (name "ALTIUM_VALUE") "1k"))
      (libsource (lib "ERA-6AEB102V") (part "ERA-6AEB102V"))
    )
    (comp (ref "R7")
      (value "ERA-6AEB102V")
      (footprint "RC0805N_PAN")
      (description "No Description Available")
      (fields (field (name "ALTIUM_VALUE") "1k"))
      (libsource (lib "ERA-6AEB102V") (part "ERA-6AEB102V"))
    )
    (comp (ref "R8")
      (value "ERA6AEB52R3V")
      (footprint "RES_ERA6A_0805_PAN")
      (description "No Description Available")
      (fields (field (name "ALTIUM_VALUE") "52.3"))
      (libsource (lib "ERA6AEB52R3V") (part "ERA6AEB52R3V"))
    )
    (comp (ref "R9")
      (value "RMCF0603ZT0R00")
      (footprint "STA_RMCF0603_STP")
      (description "No Description Available")
      (libsource (lib "RMCF0603ZT0R00") (part "RMCF0603ZT0R00"))
    )
    (comp (ref "R10")
      (value "RMCF0603ZT0R00")
      (footprint "STA_RMCF0603_STP")
      (description "No Description Available")
      (libsource (lib "RMCF0603ZT0R00") (part "RMCF0603ZT0R00"))
    )
    (comp (ref "R11")
      (value "RMCF0603ZT0R00")
      (footprint "STA_RMCF0603_STP")
      (description "No Description Available")
      (libsource (lib "RMCF0603ZT0R00") (part "RMCF0603ZT0R00"))
    )
    (comp (ref "R12")
      (value "RMCF0603ZT0R00")
      (footprint "STA_RMCF0603_STP")
      (description "No Description Available")
      (libsource (lib "RMCF0603ZT0R00") (part "RMCF0603ZT0R00"))
    )
    (comp (ref "R13")
      (value "RMCF0603ZT0R00")
      (footprint "STA_RMCF0603_STP")
      (description "No Description Available")
      (libsource (lib "RMCF0603ZT0R00") (part "RMCF0603ZT0R00"))
    )
    (comp (ref "R14")
      (value "RMCF0603ZT0R00")
      (footprint "STA_RMCF0603_STP")
      (description "No Description Available")
      (libsource (lib "RMCF0603ZT0R00") (part "RMCF0603ZT0R00"))
    )
    (comp (ref "R15")
      (value "RCL06120000Z0EA")
      (footprint "RCL0612_VIS")
      (description "No Description Available")
      (libsource (lib "RCL06120000Z0EA") (part "RCL06120000Z0EA"))
    )
    (comp (ref "R16")
      (value "RCL06120000Z0EA")
      (footprint "RCL0612_VIS")
      (description "No Description Available")
      (libsource (lib "RCL06120000Z0EA") (part "RCL06120000Z0EA"))
    )
    (comp (ref "R17")
      (value "RCL06120000Z0EA")
      (footprint "RCL0612_VIS")
      (description "No Description Available")
      (libsource (lib "RCL06120000Z0EA") (part "RCL06120000Z0EA"))
    )
    (comp (ref "R18")
      (value "RCL06120000Z0EA")
      (footprint "RCL0612_VIS")
      (description "No Description Available")
      (libsource (lib "RCL06120000Z0EA") (part "RCL06120000Z0EA"))
    )
    (comp (ref "R19")
      (value "RMCF0603ZT0R00")
      (footprint "STA_RMCF0603_STP")
      (description "No Description Available")
      (libsource (lib "RMCF0603ZT0R00") (part "RMCF0603ZT0R00"))
    )
    (comp (ref "R20")
      (value "RCL06120000Z0EA")
      (footprint "RCL0612_VIS")
      (description "No Description Available")
      (libsource (lib "RCL06120000Z0EA") (part "RCL06120000Z0EA"))
    )
    (comp (ref "R21")
      (value "RMCF0603ZT0R00")
      (footprint "STA_RMCF0603_STP")
      (description "No Description Available")
      (libsource (lib "RMCF0603ZT0R00") (part "RMCF0603ZT0R00"))
    )
    (comp (ref "R22")
      (value "RMCF0603ZT0R00")
      (footprint "STA_RMCF0603_STP")
      (description "No Description Available")
      (libsource (lib "RMCF0603ZT0R00") (part "RMCF0603ZT0R00"))
    )
    (comp (ref "R23")
      (value "RMCF0603ZT0R00")
      (footprint "STA_RMCF0603_STP")
      (description "No Description Available")
      (libsource (lib "RMCF0603ZT0R00") (part "RMCF0603ZT0R00"))
    )
    (comp (ref "R24")
      (value "RMCF0603ZT0R00")
      (footprint "STA_RMCF0603_STP")
      (description "No Description Available")
      (libsource (lib "RMCF0603ZT0R00") (part "RMCF0603ZT0R00"))
    )
    (comp (ref "R25")
      (value "ERA6AEB2432V")
      (footprint "RES_ERA6A_0805_PAN")
      (description "No Description Available")
      (libsource (lib "ERA6AEB2432V") (part "ERA6AEB2432V"))
    )
    (comp (ref "R26")
      (value "ERA6AEB2433V")
      (footprint "RES_ERA6A_0805_PAN")
      (description "No Description Available")
      (libsource (lib "ERA6AEB2433V") (part "ERA6AEB2433V"))
    )
    (comp (ref "R27")
      (value "10K")
      (footprint "RESC1608N")
      (description "Resistor SMD chip 10k Ohm 0.1W 1% 0603")
      (fields (field (name "TOLERANCE") "±1%") (field (name "Comment") "Thick Film"))
      (libsource (lib "analogboard_v2") (part "RES_10K_0603_1%"))
    )
    (comp (ref "R28")
      (value "ERA6AEB2433V")
      (footprint "RES_ERA6A_0805_PAN")
      (description "No Description Available")
      (libsource (lib "ERA6AEB2433V") (part "ERA6AEB2433V"))
    )
    (comp (ref "R29")
      (value "ERA6AEB2433V")
      (footprint "RES_ERA6A_0805_PAN")
      (description "No Description Available")
      (libsource (lib "ERA6AEB2433V") (part "ERA6AEB2433V"))
    )
    (comp (ref "R30")
      (value "ERA6AEB2432V")
      (footprint "RES_ERA6A_0805_PAN")
      (description "No Description Available")
      (libsource (lib "ERA6AEB2432V") (part "ERA6AEB2432V"))
    )
    (comp (ref "R31")
      (value "ERA6AEB2433V")
      (footprint "RES_ERA6A_0805_PAN")
      (description "No Description Available")
      (libsource (lib "ERA6AEB2433V") (part "ERA6AEB2433V"))
    )
    (comp (ref "R32")
      (value "10K")
      (footprint "RESC1608N")
      (description "Resistor SMD chip 10k Ohm 0.1W 1% 0603")
      (fields (field (name "TOLERANCE") "±1%") (field (name "Comment") "Thick Film"))
      (libsource (lib "analogboard_v2") (part "RES_10K_0603_1%"))
    )
    (comp (ref "R33")
      (value "ERA6AEB2433V")
      (footprint "RES_ERA6A_0805_PAN")
      (description "No Description Available")
      (libsource (lib "ERA6AEB2433V") (part "ERA6AEB2433V"))
    )
    (comp (ref "R34")
      (value "ERA6AEB2433V")
      (footprint "RES_ERA6A_0805_PAN")
      (description "No Description Available")
      (libsource (lib "ERA6AEB2433V") (part "ERA6AEB2433V"))
    )
    (comp (ref "R35")
      (value "RMCF0603ZT0R00")
      (footprint "STA_RMCF0603_STP")
      (description "No Description Available")
      (libsource (lib "RMCF0603ZT0R00") (part "RMCF0603ZT0R00"))
    )
    (comp (ref "R36")
      (value "RMCF0603ZT0R00")
      (footprint "STA_RMCF0603_STP")
      (description "No Description Available")
      (libsource (lib "RMCF0603ZT0R00") (part "RMCF0603ZT0R00"))
    )
    (comp (ref "R37")
      (value "ERA6AEB1021V")
      (footprint "RES_ERA6A_0805_PAN")
      (description "No Description Available")
      (libsource (lib "ERA6AEB1021V") (part "ERA6AEB1021V"))
    )
    (comp (ref "R38")
      (value "ERA-6AEB102V")
      (footprint "RC0805N_PAN")
      (description "No Description Available")
      (libsource (lib "ERA-6AEB102V") (part "ERA-6AEB102V"))
    )
    (comp (ref "R39")
      (value "ERA-6AEB102V")
      (footprint "RC0805N_PAN")
      (description "No Description Available")
      (libsource (lib "ERA-6AEB102V") (part "ERA-6AEB102V"))
    )
    (comp (ref "R40")
      (value "ERA-6AEB102V")
      (footprint "RC0805N_PAN")
      (description "No Description Available")
      (libsource (lib "ERA-6AEB102V") (part "ERA-6AEB102V"))
    )
    (comp (ref "R41")
      (value "ERA6AEB52R3V")
      (footprint "RES_ERA6A_0805_PAN")
      (description "No Description Available")
      (libsource (lib "ERA6AEB52R3V") (part "ERA6AEB52R3V"))
    )
    (comp (ref "R42")
      (value "RMCF0603ZT0R00")
      (footprint "STA_RMCF0603_STP")
      (description "No Description Available")
      (libsource (lib "RMCF0603ZT0R00") (part "RMCF0603ZT0R00"))
    )
    (comp (ref "R43")
      (value "RMCF0603ZT0R00")
      (footprint "STA_RMCF0603_STP")
      (description "No Description Available")
      (libsource (lib "RMCF0603ZT0R00") (part "RMCF0603ZT0R00"))
    )
    (comp (ref "R44")
      (value "RMCF0603ZT0R00")
      (footprint "STA_RMCF0603_STP")
      (description "No Description Available")
      (libsource (lib "RMCF0603ZT0R00") (part "RMCF0603ZT0R00"))
    )
    (comp (ref "R45")
      (value "RMCF0603ZT0R00")
      (footprint "STA_RMCF0603_STP")
      (description "No Description Available")
      (libsource (lib "RMCF0603ZT0R00") (part "RMCF0603ZT0R00"))
    )
    (comp (ref "R85")
      (value "866R")
      (footprint "RESC1608N")
      (description "Resistor SMD chip 866 Ohm 0.1W 1% 0603")
      (fields (field (name "TOLERANCE") "±1%") (field (name "Comment") "Thick Film"))
      (libsource (lib "MB - Misc") (part "RES_866R_0603_1%_1"))
    )
    (comp (ref "U1")
      (value "NCD2400MTR")
      (footprint "DFN-6_IXY")
      (description "No Description Available")
      (libsource (lib "NCD2400MTR") (part "NCD2400MTR"))
    )
    (comp (ref "U2")
      (value "NCD2400MTR")
      (footprint "DFN-6_IXY")
      (description "No Description Available")
      (libsource (lib "NCD2400MTR") (part "NCD2400MTR"))
    )
    (comp (ref "U3")
      (value "THS4521IDR")
      (footprint "D8")
      (description "No Description Available")
      (libsource (lib "THS4521IDR") (part "THS4521IDR"))
    )
    (comp (ref "U4")
      (value "NCD2400MTR")
      (footprint "DFN-6_IXY")
      (description "No Description Available")
      (libsource (lib "NCD2400MTR") (part "NCD2400MTR"))
    )
    (comp (ref "U5")
      (value "NCD2400MTR")
      (footprint "DFN-6_IXY")
      (description "No Description Available")
      (libsource (lib "NCD2400MTR") (part "NCD2400MTR"))
    )
    (comp (ref "U6")
      (value "PGA855RGTR")
      (footprint "VQFN16_RGT_TEX")
      (description "No Description Available")
      (libsource (lib "PGA855RGTR") (part "PGA855RGTR"))
    )
    (comp (ref "U7")
      (value "PGA855RGTR")
      (footprint "VQFN16_RGT_TEX")
      (description "No Description Available")
      (libsource (lib "PGA855RGTR") (part "PGA855RGTR"))
    )
    (comp (ref "U8")
      (value "NCD2400MTR")
      (footprint "DFN-6_IXY")
      (description "No Description Available")
      (libsource (lib "NCD2400MTR") (part "NCD2400MTR"))
    )
    (comp (ref "U9")
      (value "NCD2400MTR")
      (footprint "DFN-6_IXY")
      (description "No Description Available")
      (libsource (lib "NCD2400MTR") (part "NCD2400MTR"))
    )
    (comp (ref "U10")
      (value "NCD2400MTR")
      (footprint "DFN-6_IXY")
      (description "No Description Available")
      (libsource (lib "NCD2400MTR") (part "NCD2400MTR"))
    )
    (comp (ref "U11")
      (value "NCD2400MTR")
      (footprint "DFN-6_IXY")
      (description "No Description Available")
      (libsource (lib "NCD2400MTR") (part "NCD2400MTR"))
    )
    (comp (ref "U12")
      (value "NCD2400MTR")
      (footprint "DFN-6_IXY")
      (description "No Description Available")
      (libsource (lib "NCD2400MTR") (part "NCD2400MTR"))
    )
    (comp (ref "U13")
      (value "NCD2400MTR")
      (footprint "DFN-6_IXY")
      (description "No Description Available")
      (libsource (lib "NCD2400MTR") (part "NCD2400MTR"))
    )
    (comp (ref "U14")
      (value "NCD2400MTR")
      (footprint "DFN-6_IXY")
      (description "No Description Available")
      (libsource (lib "NCD2400MTR") (part "NCD2400MTR"))
    )
    (comp (ref "U15")
      (value "NCD2400MTR")
      (footprint "DFN-6_IXY")
      (description "No Description Available")
      (libsource (lib "NCD2400MTR") (part "NCD2400MTR"))
    )
    (comp (ref "U16")
      (value "DAC7614EB")
      (footprint "DB20")
      (description "No Description Available")
      (fields (field (name "COPYRIGHT") "Copyright (C) 2022 Ultra Librarian. All rights reserved."))
      (libsource (lib "DAC7614EB") (part "DAC7614EB"))
    )
    (comp (ref "U17")
      (value "NCD2400MTR")
      (footprint "DFN-6_IXY")
      (description "No Description Available")
      (libsource (lib "NCD2400MTR") (part "NCD2400MTR"))
    )
    (comp (ref "U18")
      (value "NCD2400MTR")
      (footprint "DFN-6_IXY")
      (description "No Description Available")
      (libsource (lib "NCD2400MTR") (part "NCD2400MTR"))
    )
    (comp (ref "U19")
      (value "ISL60002BIH325Z-T7A")
      (footprint "P3_064_INR")
      (description "No Description Available")
      (libsource (lib "ISL60002BIH325Z-T7A") (part "ISL60002BIH325Z-T7A"))
    )
    (comp (ref "U20")
      (value "DAC7614EB")
      (footprint "DB20")
      (description "No Description Available")
      (fields (field (name "COPYRIGHT") "Copyright (C) 2022 Ultra Librarian. All rights reserved."))
      (libsource (lib "DAC7614EB") (part "DAC7614EB"))
    )
    (comp (ref "U21")
      (value "NCD2400MTR")
      (footprint "DFN-6_IXY")
      (description "No Description Available")
      (libsource (lib "NCD2400MTR") (part "NCD2400MTR"))
    )
    (comp (ref "U22")
      (value "NCD2400MTR")
      (footprint "DFN-6_IXY")
      (description "No Description Available")
      (libsource (lib "NCD2400MTR") (part "NCD2400MTR"))
    )
    (comp (ref "U23")
      (value "SN74AUP1T17DCKR")
      (footprint "DCK5")
      (description "No Description Available")
      (libsource (lib "SN74AUP1T17DCKR") (part "SN74AUP1T17DCKR"))
    )
    (comp (ref "U24")
      (value "TLV2771CDBVR")
      (footprint "DBV5")
      (description "No Description Available")
      (fields (field (name "COPYRIGHT") "Copyright (C) 2022 Ultra Librarian. All rights reserved."))
      (libsource (lib "TLV2771CDBVR") (part "TLV2771CDBVR"))
    )
    (comp (ref "U25")
      (value "BC807-25WT1G")
      (footprint "SOT-323-3_2P2X1P35_ONS")
      (description "No Description Available")
      (libsource (lib "BC807-25WT1G") (part "BC807-25WT1G"))
    )
    (comp (ref "U26")
      (value "DEV-16771")
      (footprint "MODULE_DEV-16771")
      (description "RT1062 Teensy 4.1 series ARM® Cortex®-M7 MPU Embedded Evaluation Board")
      (fields (field (name "MF") "SparkFun Electronics"))
      (libsource (lib "DEV-16771") (part "DEV-16771"))
    )
    (comp (ref "U27")
      (value "TLV2771CDBVR")
      (footprint "DBV5")
      (description "No Description Available")
      (fields (field (name "COPYRIGHT") "Copyright (C) 2022 Ultra Librarian. All rights reserved."))
      (libsource (lib "TLV2771CDBVR") (part "TLV2771CDBVR"))
    )
    (comp (ref "U28")
      (value "BC807-25WT1G")
      (footprint "SOT-323-3_2P2X1P35_ONS")
      (description "No Description Available")
      (libsource (lib "BC807-25WT1G") (part "BC807-25WT1G"))
    )
    (comp (ref "U29")
      (value "LP3961ES-2.5")
      (footprint "TS5B_TEX")
      (description "No Description Available")
      (fields (field (name "COPYRIGHT") "Copyright (C) 2022 Ultra Librarian. All rights reserved."))
      (libsource (lib "LP3961ES-2P5") (part "LP3961ES-2.5"))
    )
    (comp (ref "U30")
      (value "TLV2771CDBVR")
      (footprint "DBV5")
      (description "No Description Available")
      (fields (field (name "COPYRIGHT") "Copyright (C) 2022 Ultra Librarian. All rights reserved."))
      (libsource (lib "TLV2771CDBVR") (part "TLV2771CDBVR"))
    )
    (comp (ref "U31")
      (value "BC807-25WT1G")
      (footprint "SOT-323-3_2P2X1P35_ONS")
      (description "No Description Available")
      (libsource (lib "BC807-25WT1G") (part "BC807-25WT1G"))
    )
    (comp (ref "U32")
      (value "TLV2771CDBVR")
      (footprint "DBV5")
      (description "No Description Available")
      (fields (field (name "COPYRIGHT") "Copyright (C) 2022 Ultra Librarian. All rights reserved."))
      (libsource (lib "TLV2771CDBVR") (part "TLV2771CDBVR"))
    )
    (comp (ref "U33")
      (value "BC807-25WT1G")
      (footprint "SOT-323-3_2P2X1P35_ONS")
      (description "No Description Available")
      (libsource (lib "BC807-25WT1G") (part "BC807-25WT1G"))
    )
    (comp (ref "U34")
      (value "SN74AUP1T17DCKR")
      (footprint "DCK5")
      (description "No Description Available")
      (libsource (lib "SN74AUP1T17DCKR") (part "SN74AUP1T17DCKR"))
    )
    (comp (ref "U35")
      (value "SN74AUP1T17DCKR")
      (footprint "DCK5")
      (description "No Description Available")
      (libsource (lib "SN74AUP1T17DCKR") (part "SN74AUP1T17DCKR"))
    )
    (comp (ref "U36")
      (value "SN74AUP1T17DCKR")
      (footprint "DCK5")
      (description "No Description Available")
      (libsource (lib "SN74AUP1T17DCKR") (part "SN74AUP1T17DCKR"))
    )
    (comp (ref "U37")
      (value "SN74AUP1T17DCKR")
      (footprint "DCK5")
      (description "No Description Available")
      (libsource (lib "SN74AUP1T17DCKR") (part "SN74AUP1T17DCKR"))
    )
    (comp (ref "U38")
      (value "SN74AUP1T17DCKR")
      (footprint "DCK5")
      (description "No Description Available")
      (libsource (lib "SN74AUP1T17DCKR") (part "SN74AUP1T17DCKR"))
    )
    (comp (ref "U39")
      (value "SN74AUP1T17DCKR")
      (footprint "DCK5")
      (description "No Description Available")
      (libsource (lib "SN74AUP1T17DCKR") (part "SN74AUP1T17DCKR"))
    )
    (comp (ref "U40")
      (value "SN74AUP1T17DCKR")
      (footprint "DCK5")
      (description "No Description Available")
      (libsource (lib "SN74AUP1T17DCKR") (part "SN74AUP1T17DCKR"))
    )
    (comp (ref "U41")
      (value "SN74AUP1T17DCKR")
      (footprint "DCK5")
      (description "No Description Available")
      (libsource (lib "SN74AUP1T17DCKR") (part "SN74AUP1T17DCKR"))
    )
    (comp (ref "U42")
      (value "SN74AUP1T17DCKR")
      (footprint "DCK5")
      (description "No Description Available")
      (libsource (lib "SN74AUP1T17DCKR") (part "SN74AUP1T17DCKR"))
    )
    (comp (ref "U43")
      (value "DAC7614EB")
      (footprint "DB20")
      (description "No Description Available")
      (fields (field (name "COPYRIGHT") "Copyright (C) 2022 Ultra Librarian. All rights reserved."))
      (libsource (lib "DAC7614EB") (part "DAC7614EB"))
    )
    (comp (ref "U44")
      (value "ISL60002BIH325Z-T7A")
      (footprint "P3_064_INR")
      (description "No Description Available")
      (libsource (lib "ISL60002BIH325Z-T7A") (part "ISL60002BIH325Z-T7A"))
    )
    (comp (ref "U45")
      (value "DAC7614EB")
      (footprint "DB20")
      (description "No Description Available")
      (fields (field (name "COPYRIGHT") "Copyright (C) 2022 Ultra Librarian. All rights reserved."))
      (libsource (lib "DAC7614EB") (part "DAC7614EB"))
    )
    (comp (ref "U46")
      (value "TLV2771CDBVR")
      (footprint "DBV5")
      (description "No Description Available")
      (fields (field (name "COPYRIGHT") "Copyright (C) 2022 Ultra Librarian. All rights reserved."))
      (libsource (lib "TLV2771CDBVR") (part "TLV2771CDBVR"))
    )
    (comp (ref "U47")
      (value "BC807-25WT1G")
      (footprint "SOT-323-3_2P2X1P35_ONS")
      (description "No Description Available")
      (libsource (lib "BC807-25WT1G") (part "BC807-25WT1G"))
    )
    (comp (ref "U48")
      (value "TLV2771CDBVR")
      (footprint "DBV5")
      (description "No Description Available")
      (fields (field (name "COPYRIGHT") "Copyright (C) 2022 Ultra Librarian. All rights reserved."))
      (libsource (lib "TLV2771CDBVR") (part "TLV2771CDBVR"))
    )
    (comp (ref "U49")
      (value "BC807-25WT1G")
      (footprint "SOT-323-3_2P2X1P35_ONS")
      (description "No Description Available")
      (libsource (lib "BC807-25WT1G") (part "BC807-25WT1G"))
    )
    (comp (ref "U50")
      (value "LP3961ES-2.5")
      (footprint "TS5B_TEX")
      (description "No Description Available")
      (fields (field (name "COPYRIGHT") "Copyright (C) 2022 Ultra Librarian. All rights reserved."))
      (libsource (lib "LP3961ES-2P5") (part "LP3961ES-2.5"))
    )
    (comp (ref "U51")
      (value "TLV2771CDBVR")
      (footprint "DBV5")
      (description "No Description Available")
      (fields (field (name "COPYRIGHT") "Copyright (C) 2022 Ultra Librarian. All rights reserved."))
      (libsource (lib "TLV2771CDBVR") (part "TLV2771CDBVR"))
    )
    (comp (ref "U52")
      (value "BC807-25WT1G")
      (footprint "SOT-323-3_2P2X1P35_ONS")
      (description "No Description Available")
      (libsource (lib "BC807-25WT1G") (part "BC807-25WT1G"))
    )
    (comp (ref "U53")
      (value "TLV2771CDBVR")
      (footprint "DBV5")
      (description "No Description Available")
      (fields (field (name "COPYRIGHT") "Copyright (C) 2022 Ultra Librarian. All rights reserved."))
      (libsource (lib "TLV2771CDBVR") (part "TLV2771CDBVR"))
    )
    (comp (ref "U54")
      (value "BC807-25WT1G")
      (footprint "SOT-323-3_2P2X1P35_ONS")
      (description "No Description Available")
      (libsource (lib "BC807-25WT1G") (part "BC807-25WT1G"))
    )
    (comp (ref "U55")
      (value "THS4521IDR")
      (footprint "D8")
      (description "No Description Available")
      (libsource (lib "THS4521IDR") (part "THS4521IDR"))
    )
    (comp (ref "U56")
      (value "PGA855RGTR")
      (footprint "VQFN16_RGT_TEX")
      (description "No Description Available")
      (libsource (lib "PGA855RGTR") (part "PGA855RGTR"))
    )
    (comp (ref "U57")
      (value "PGA855RGTR")
      (footprint "VQFN16_RGT_TEX")
      (description "No Description Available")
      (libsource (lib "PGA855RGTR") (part "PGA855RGTR"))
    )
    (comp (ref "VDD_1")
      (value "Red")
      (footprint "LED-0603-RED")
      (description "LED 0603 SMD Hyper Red 630nm 220mcd 20mA")
      (libsource (lib "PBL - Light Sources") (part "LED_SMD_Red_0603_220mcd"))
    )
  )
  (nets
    (net (code "2") (name "/A0") (class "Default")
      (node (ref "P8") (pin "2") (pinfunction "2_2") (pintype "passive"))
      (node (ref "U6") (pin "4") (pinfunction "A0_4") (pintype "input"))
      (node (ref "U7") (pin "4") (pinfunction "A0_4") (pintype "input"))
    )
    (net (code "3") (name "/A1") (class "Default")
      (node (ref "P7") (pin "2") (pinfunction "2_2") (pintype "passive"))
      (node (ref "U6") (pin "5") (pinfunction "A1_5") (pintype "input"))
      (node (ref "U7") (pin "5") (pinfunction "A1_5") (pintype "input"))
    )
    (net (code "4") (name "/A2") (class "Default")
      (node (ref "P6") (pin "2") (pinfunction "2_2") (pintype "passive"))
      (node (ref "U6") (pin "1") (pinfunction "A2_1") (pintype "input"))
      (node (ref "U7") (pin "1") (pinfunction "A2_1") (pintype "input"))
    )
    (net (code "5") (name "/ACK") (class "Default")
      (node (ref "J33") (pin "5") (pinfunction "5_5") (pintype "passive"))
      (node (ref "P60") (pin "2") (pinfunction "2_2") (pintype "passive"))
      (node (ref "U34") (pin "4") (pinfunction "Y_4") (pintype "output"))
    )
    (net (code "6") (name "/ACK_EXT") (class "Default")
      (node (ref "J34") (pin "C11") (pinfunction "C11_C11") (pintype "passive"))
      (node (ref "P60") (pin "1") (pinfunction "1_1") (pintype "passive"))
      (node (ref "U26") (pin "1") (pinfunction "TX1_1") (pintype "bidirectional"))
      (node (ref "U34") (pin "2") (pinfunction "A_2") (pintype "input"))
    )
    (net (code "7") (name "/ADDRX0") (class "Default")
      (node (ref "J33") (pin "14") (pinfunction "14_14") (pintype "passive"))
      (node (ref "P65") (pin "1") (pinfunction "1_1") (pintype "passive"))
      (node (ref "U38") (pin "2") (pinfunction "A_2") (pintype "input"))
    )
    (net (code "8") (name "/ADDRX0_EXT") (class "Default")
      (node (ref "J34") (pin "C18") (pinfunction "C18_C18") (pintype "passive"))
      (node (ref "P65") (pin "2") (pinfunction "2_2") (pintype "passive"))
      (node (ref "U26") (pin "4") (pinfunction "BCLK2_4") (pintype "bidirectional"))
      (node (ref "U38") (pin "4") (pinfunction "Y_4") (pintype "output"))
    )
    (net (code "9") (name "/ADDRY0") (class "Default")
      (node (ref "J33") (pin "17") (pinfunction "17_17") (pintype "passive"))
      (node (ref "P64") (pin "1") (pinfunction "1_1") (pintype "passive"))
      (node (ref "U37") (pin "2") (pinfunction "A_2") (pintype "input"))
    )
    (net (code "10") (name "/ADDRY0_EXT") (class "Default")
      (node (ref "J34") (pin "C19") (pinfunction "C19_C19") (pintype "passive"))
      (node (ref "P64") (pin "2") (pinfunction "2_2") (pintype "passive"))
      (node (ref "U26") (pin "5") (pinfunction "IN2_5") (pintype "bidirectional"))
      (node (ref "U37") (pin "4") (pinfunction "Y_4") (pintype "output"))
    )
    (net (code "11") (name "/AER_DIS") (class "Default")
      (node (ref "J33") (pin "20") (pinfunction "20_20") (pintype "passive"))
      (node (ref "J34") (pin "C22") (pinfunction "C22_C22") (pintype "passive"))
      (node (ref "U26") (pin "6") (pinfunction "OUT1D_6") (pintype "output"))
    )
    (net (code "12") (name "/AGND_VCM") (class "Default")
      (node (ref "P89") (pin "2") (pinfunction "2_2") (pintype "passive"))
      (node (ref "U12") (pin "3") (pinfunction "CN_3") (pintype "power_in"))
      (node (ref "U13") (pin "3") (pinfunction "CN_3") (pintype "power_in"))
      (node (ref "U15") (pin "3") (pinfunction "CN_3") (pintype "power_in"))
      (node (ref "U18") (pin "3") (pinfunction "CN_3") (pintype "power_in"))
      (node (ref "U2") (pin "3") (pinfunction "CN_3") (pintype "power_in"))
      (node (ref "U22") (pin "3") (pinfunction "CN_3") (pintype "power_in"))
      (node (ref "U8") (pin "3") (pinfunction "CN_3") (pintype "power_in"))
      (node (ref "U9") (pin "3") (pinfunction "CN_3") (pintype "power_in"))
    )
    (net (code "13") (name "/CHIPA_ACK") (class "Default")
      (node (ref "J30") (pin "37") (pinfunction "37_37") (pintype "passive"))
      (node (ref "J33") (pin "4") (pinfunction "4_4") (pintype "passive"))
    )
    (net (code "14") (name "/CHIPA_ADDRX0") (class "Default")
      (node (ref "J30") (pin "25") (pinfunction "25_25") (pintype "passive"))
      (node (ref "J33") (pin "13") (pinfunction "13_13") (pintype "passive"))
    )
    (net (code "15") (name "/CHIPA_ADDRY0") (class "Default")
      (node (ref "J30") (pin "23") (pinfunction "23_23") (pintype "passive"))
      (node (ref "J33") (pin "16") (pinfunction "16_16") (pintype "passive"))
    )
    (net (code "16") (name "/CHIPA_AER_DIS") (class "Default")
      (node (ref "J30") (pin "21") (pinfunction "21_21") (pintype "passive"))
      (node (ref "J33") (pin "19") (pinfunction "19_19") (pintype "passive"))
    )
    (net (code "17") (name "/CHIPA_CATTN_SCL") (class "Default")
      (node (ref "U12") (pin "6") (pinfunction "SCL_6") (pintype "input"))
      (node (ref "U18") (pin "6") (pinfunction "SCL_6") (pintype "input"))
      (node (ref "U2") (pin "6") (pinfunction "SCL_6") (pintype "input"))
      (node (ref "U26") (pin "40") (pinfunction "A16_40") (pintype "bidirectional"))
      (node (ref "U9") (pin "6") (pinfunction "SCL_6") (pintype "input"))
    )
    (net (code "18") (name "/CHIPA_CATTN_SDA") (class "Default")
      (node (ref "U12") (pin "1") (pinfunction "SDA_1") (pintype "bidirectional"))
      (node (ref "U18") (pin "1") (pinfunction "SDA_1") (pintype "bidirectional"))
      (node (ref "U2") (pin "1") (pinfunction "SDA_1") (pintype "bidirectional"))
      (node (ref "U26") (pin "39") (pinfunction "A15_39") (pintype "bidirectional"))
      (node (ref "U9") (pin "1") (pinfunction "SDA_1") (pintype "bidirectional"))
    )
    (net (code "19") (name "/CHIPA_CATTP_SCL") (class "Default")
      (node (ref "U13") (pin "6") (pinfunction "SCL_6") (pintype "input"))
      (node (ref "U15") (pin "6") (pinfunction "SCL_6") (pintype "input"))
      (node (ref "U22") (pin "6") (pinfunction "SCL_6") (pintype "input"))
      (node (ref "U26") (pin "38") (pinfunction "A14_38") (pintype "bidirectional"))
      (node (ref "U8") (pin "6") (pinfunction "SCL_6") (pintype "input"))
    )
    (net (code "20") (name "/CHIPA_CATTP_SDA") (class "Default")
      (node (ref "U13") (pin "1") (pinfunction "SDA_1") (pintype "bidirectional"))
      (node (ref "U15") (pin "1") (pinfunction "SDA_1") (pintype "bidirectional"))
      (node (ref "U22") (pin "1") (pinfunction "SDA_1") (pintype "bidirectional"))
      (node (ref "U26") (pin "37") (pinfunction "CS3_37") (pintype "bidirectional"))
      (node (ref "U8") (pin "1") (pinfunction "SDA_1") (pintype "bidirectional"))
    )
    (net (code "21") (name "/CHIPA_CLK") (class "Default")
      (node (ref "J22") (pin "1") (pinfunction "1_1") (pintype "passive"))
      (node (ref "J30") (pin "11") (pinfunction "11_11") (pintype "passive"))
    )
    (net (code "22") (name "/CHIPA_CSb_IDAC") (class "Default")
      (node (ref "J33") (pin "55") (pinfunction "55_55") (pintype "passive"))
      (node (ref "U20") (pin "14") (pinfunction "*CS_14") (pintype "input"))
    )
    (net (code "23") (name "/CHIPA_CSb_VDAC") (class "Default")
      (node (ref "J33") (pin "52") (pinfunction "52_52") (pintype "passive"))
      (node (ref "U16") (pin "14") (pinfunction "*CS_14") (pintype "input"))
    )
    (net (code "24") (name "/CHIPA_CT_MODE") (class "Default")
      (node (ref "J30") (pin "15") (pinfunction "15_15") (pintype "passive"))
      (node (ref "J33") (pin "28") (pinfunction "28_28") (pintype "passive"))
    )
    (net (code "25") (name "/CHIPA_DIG_RES0") (class "Default")
      (node (ref "J30") (pin "7") (pinfunction "7_7") (pintype "passive"))
      (node (ref "J33") (pin "34") (pinfunction "34_34") (pintype "passive"))
    )
    (net (code "26") (name "/CHIPA_DIG_RES1") (class "Default")
      (node (ref "J30") (pin "5") (pinfunction "5_5") (pintype "passive"))
      (node (ref "J33") (pin "37") (pinfunction "37_37") (pintype "passive"))
    )
    (net (code "27") (name "/CHIPA_DIG_RES2") (class "Default")
      (node (ref "J30") (pin "3") (pinfunction "3_3") (pintype "passive"))
      (node (ref "J33") (pin "40") (pinfunction "40_40") (pintype "passive"))
    )
    (net (code "28") (name "/CHIPA_DIG_RES3") (class "Default")
      (node (ref "J30") (pin "1") (pinfunction "1_1") (pintype "passive"))
      (node (ref "J33") (pin "43") (pinfunction "43_43") (pintype "passive"))
    )
    (net (code "29") (name "/CHIPA_GAIN_HI") (class "Default")
      (node (ref "J30") (pin "13") (pinfunction "13_13") (pintype "passive"))
      (node (ref "J33") (pin "31") (pinfunction "31_31") (pintype "passive"))
    )
    (net (code "30") (name "/CHIPA_IBIAS") (class "Default")
      (node (ref "J30") (pin "12") (pinfunction "12_12") (pintype "passive"))
      (node (ref "P59") (pin "2") (pinfunction "2_2") (pintype "passive"))
    )
    (net (code "31") (name "/CHIPA_IBIAS_ADAPT") (class "Default")
      (node (ref "J30") (pin "10") (pinfunction "10_10") (pintype "passive"))
      (node (ref "P58") (pin "2") (pinfunction "2_2") (pintype "passive"))
    )
    (net (code "32") (name "/CHIPA_IBIAS_ADAPT_PRE") (class "Default")
      (node (ref "P58") (pin "1") (pinfunction "1_1") (pintype "passive"))
      (node (ref "U31") (pin "3") (pinfunction "COLLECTOR_3") (pintype "passive"))
    )
    (net (code "33") (name "/CHIPA_IBIAS_AFE") (class "Default")
      (node (ref "J30") (pin "8") (pinfunction "8_8") (pintype "passive"))
      (node (ref "P57") (pin "2") (pinfunction "2_2") (pintype "passive"))
    )
    (net (code "34") (name "/CHIPA_IBIAS_AFE_PRE") (class "Default")
      (node (ref "P57") (pin "1") (pinfunction "1_1") (pintype "passive"))
      (node (ref "U28") (pin "3") (pinfunction "COLLECTOR_3") (pintype "passive"))
    )
    (net (code "35") (name "/CHIPA_IBIAS_PRE") (class "Default")
      (node (ref "P59") (pin "1") (pinfunction "1_1") (pintype "passive"))
      (node (ref "U33") (pin "3") (pinfunction "COLLECTOR_3") (pintype "passive"))
    )
    (net (code "36") (name "/CHIPA_IBIAS_SLEW") (class "Default")
      (node (ref "J30") (pin "6") (pinfunction "6_6") (pintype "passive"))
      (node (ref "P56") (pin "2") (pinfunction "2_2") (pintype "passive"))
    )
    (net (code "37") (name "/CHIPA_IBIAS_SLEW_PRE") (class "Default")
      (node (ref "P56") (pin "1") (pinfunction "1_1") (pintype "passive"))
      (node (ref "U25") (pin "3") (pinfunction "COLLECTOR_3") (pintype "passive"))
    )
    (net (code "38") (name "/CHIPA_LDACb") (class "Default")
      (node (ref "J33") (pin "49") (pinfunction "49_49") (pintype "passive"))
      (node (ref "U16") (pin "18") (pinfunction "*LOADDACS_18") (pintype "passive"))
      (node (ref "U20") (pin "18") (pinfunction "*LOADDACS_18") (pintype "passive"))
    )
    (net (code "39") (name "/CHIPA_RATIOMODE0") (class "Default")
      (node (ref "J30") (pin "19") (pinfunction "19_19") (pintype "passive"))
      (node (ref "J33") (pin "22") (pinfunction "22_22") (pintype "passive"))
    )
    (net (code "40") (name "/CHIPA_RATIOMODE1") (class "Default")
      (node (ref "J30") (pin "17") (pinfunction "17_17") (pintype "passive"))
      (node (ref "J33") (pin "25") (pinfunction "25_25") (pintype "passive"))
    )
    (net (code "41") (name "/CHIPA_REQOFF") (class "Default")
      (node (ref "J30") (pin "33") (pinfunction "33_33") (pintype "passive"))
      (node (ref "J33") (pin "10") (pinfunction "10_10") (pintype "passive"))
    )
    (net (code "42") (name "/CHIPA_REQON") (class "Default")
      (node (ref "J30") (pin "35") (pinfunction "35_35") (pintype "passive"))
      (node (ref "J33") (pin "7") (pinfunction "7_7") (pintype "passive"))
    )
    (net (code "43") (name "/CHIPA_RESETb") (class "Default")
      (node (ref "J33") (pin "46") (pinfunction "46_46") (pintype "passive"))
      (node (ref "U16") (pin "19") (pinfunction "*RESET_19") (pintype "input"))
      (node (ref "U20") (pin "19") (pinfunction "*RESET_19") (pintype "input"))
    )
    (net (code "44") (name "/CHIPA_RST") (class "Default")
      (node (ref "J30") (pin "39") (pinfunction "39_39") (pintype "passive"))
      (node (ref "J33") (pin "1") (pinfunction "1_1") (pintype "passive"))
    )
    (net (code "45") (name "/CHIPA_SCLK") (class "Default")
      (node (ref "J33") (pin "58") (pinfunction "58_58") (pintype "passive"))
      (node (ref "U16") (pin "13") (pinfunction "CLK_13") (pintype "passive"))
      (node (ref "U20") (pin "13") (pinfunction "CLK_13") (pintype "passive"))
    )
    (net (code "46") (name "/CHIPA_SDI") (class "Default")
      (node (ref "J33") (pin "61") (pinfunction "61_61") (pintype "passive"))
      (node (ref "U16") (pin "12") (pinfunction "SDI_12") (pintype "input"))
      (node (ref "U20") (pin "12") (pinfunction "SDI_12") (pintype "input"))
    )
    (net (code "47") (name "/CHIPA_VBIAS") (class "Default")
      (node (ref "U20") (pin "3") (pinfunction "VOUTC_3") (pintype "output"))
      (node (ref "U32") (pin "3") (pinfunction "IN+_3") (pintype "input"))
    )
    (net (code "48") (name "/CHIPA_VBIAS_ADAPT") (class "Default")
      (node (ref "U20") (pin "2") (pinfunction "VOUTD_2") (pintype "output"))
      (node (ref "U30") (pin "3") (pinfunction "IN+_3") (pintype "input"))
    )
    (net (code "49") (name "/CHIPA_VBIAS_AFE") (class "Default")
      (node (ref "U20") (pin "8") (pinfunction "VOUTB_8") (pintype "output"))
      (node (ref "U27") (pin "3") (pinfunction "IN+_3") (pintype "input"))
    )
    (net (code "50") (name "/CHIPA_VBIAS_SLEW") (class "Default")
      (node (ref "U20") (pin "9") (pinfunction "VOUTA_9") (pintype "output"))
      (node (ref "U24") (pin "3") (pinfunction "IN+_3") (pintype "input"))
    )
    (net (code "51") (name "/CHIPA_VCM") (class "Default")
      (node (ref "J16") (pin "1") (pinfunction "1_1") (pintype "passive"))
      (node (ref "J16") (pin "11") (pinfunction "11_11") (pintype "passive"))
      (node (ref "J16") (pin "13") (pinfunction "13_13") (pintype "passive"))
      (node (ref "J16") (pin "14") (pinfunction "14_14") (pintype "passive"))
      (node (ref "J16") (pin "15") (pinfunction "15_15") (pintype "passive"))
      (node (ref "J16") (pin "17") (pinfunction "17_17") (pintype "passive"))
      (node (ref "J16") (pin "18") (pinfunction "18_18") (pintype "passive"))
      (node (ref "J16") (pin "22") (pinfunction "22_22") (pintype "passive"))
      (node (ref "J16") (pin "23") (pinfunction "23_23") (pintype "passive"))
      (node (ref "J16") (pin "26") (pinfunction "26_26") (pintype "passive"))
      (node (ref "J16") (pin "27") (pinfunction "27_27") (pintype "passive"))
      (node (ref "J16") (pin "3") (pinfunction "3_3") (pintype "passive"))
      (node (ref "J16") (pin "33") (pinfunction "33_33") (pintype "passive"))
      (node (ref "J16") (pin "34") (pinfunction "34_34") (pintype "passive"))
      (node (ref "J16") (pin "40") (pinfunction "40_40") (pintype "passive"))
      (node (ref "J16") (pin "5") (pinfunction "5_5") (pintype "passive"))
      (node (ref "J16") (pin "7") (pinfunction "7_7") (pintype "passive"))
      (node (ref "J16") (pin "9") (pinfunction "9_9") (pintype "passive"))
      (node (ref "J16") (pin "S1") (pinfunction "SHIELD_S1") (pintype "passive"))
      (node (ref "J16") (pin "S2") (pinfunction "SHIELD_S2") (pintype "passive"))
      (node (ref "J30") (pin "30") (pinfunction "30_30") (pintype "passive"))
      (node (ref "P1") (pin "2") (pinfunction "Y_2") (pintype "passive"))
      (node (ref "P10") (pin "2") (pinfunction "Y_2") (pintype "passive"))
      (node (ref "P12") (pin "2") (pinfunction "Y_2") (pintype "passive"))
      (node (ref "P15") (pin "2") (pinfunction "Y_2") (pintype "passive"))
      (node (ref "P17") (pin "2") (pinfunction "Y_2") (pintype "passive"))
      (node (ref "P18") (pin "1") (pinfunction "1_1") (pintype "passive"))
      (node (ref "P19") (pin "2") (pinfunction "Y_2") (pintype "passive"))
      (node (ref "P2") (pin "2") (pinfunction "Y_2") (pintype "passive"))
      (node (ref "P22") (pin "2") (pinfunction "Y_2") (pintype "passive"))
      (node (ref "P25") (pin "2") (pinfunction "Y_2") (pintype "passive"))
      (node (ref "P27") (pin "2") (pinfunction "Y_2") (pintype "passive"))
      (node (ref "P28") (pin "1") (pinfunction "1_1") (pintype "passive"))
      (node (ref "P38") (pin "2") (pinfunction "Y_2") (pintype "passive"))
      (node (ref "P4") (pin "2") (pinfunction "Y_2") (pintype "passive"))
      (node (ref "P41") (pin "2") (pinfunction "Y_2") (pintype "passive"))
      (node (ref "P51") (pin "2") (pinfunction "Y_2") (pintype "passive"))
      (node (ref "P54") (pin "2") (pinfunction "Y_2") (pintype "passive"))
      (node (ref "P89") (pin "1") (pinfunction "1_1") (pintype "passive"))
      (node (ref "P9") (pin "2") (pinfunction "Y_2") (pintype "passive"))
      (node (ref "U16") (pin "9") (pinfunction "VOUTA_9") (pintype "output"))
    )
    (net (code "52") (name "/CHIPA_VD") (class "Default")
      (node (ref "J30") (pin "4") (pinfunction "4_4") (pintype "passive"))
      (node (ref "J33") (pin "70") (pinfunction "70_70") (pintype "passive"))
    )
    (net (code "53") (name "/CHIPA_VG") (class "Default")
      (node (ref "J30") (pin "2") (pinfunction "2_2") (pintype "passive"))
      (node (ref "J33") (pin "67") (pinfunction "67_67") (pintype "passive"))
    )
    (net (code "54") (name "/CHIPA_VINN_REPLICA") (class "Default")
      (node (ref "J16") (pin "4") (pinfunction "4_4") (pintype "passive"))
      (node (ref "J3") (pin "2") (pinfunction "2_2") (pintype "passive"))
      (node (ref "R1") (pin "2") (pinfunction "2_2") (pintype "passive"))
    )
    (net (code "55") (name "/CHIPA_VINN_X0") (class "Default")
      (node (ref "J16") (pin "20") (pinfunction "20_20") (pintype "passive"))
      (node (ref "P12") (pin "1") (pinfunction "X_1") (pintype "passive"))
      (node (ref "U5") (pin "3") (pinfunction "CN_3") (pintype "power_in"))
    )
    (net (code "56") (name "/CHIPA_VINN_X1") (class "Default")
      (node (ref "J16") (pin "39") (pinfunction "39_39") (pintype "passive"))
      (node (ref "P19") (pin "1") (pinfunction "X_1") (pintype "passive"))
      (node (ref "U10") (pin "3") (pinfunction "CN_3") (pintype "power_in"))
    )
    (net (code "57") (name "/CHIPA_VINN_Y0") (class "Default")
      (node (ref "J16") (pin "32") (pinfunction "32_32") (pintype "passive"))
      (node (ref "P41") (pin "1") (pinfunction "X_1") (pintype "passive"))
      (node (ref "U17") (pin "3") (pinfunction "CN_3") (pintype "power_in"))
    )
    (net (code "58") (name "/CHIPA_VINN_Y1") (class "Default")
      (node (ref "J16") (pin "25") (pinfunction "25_25") (pintype "passive"))
      (node (ref "P2") (pin "1") (pinfunction "X_1") (pintype "passive"))
      (node (ref "U1") (pin "3") (pinfunction "CN_3") (pintype "power_in"))
    )
    (net (code "59") (name "/CHIPA_VINP_REPLICA") (class "Default")
      (node (ref "J16") (pin "2") (pinfunction "2_2") (pintype "passive"))
      (node (ref "J2") (pin "2") (pinfunction "2_2") (pintype "passive"))
      (node (ref "R2") (pin "2") (pinfunction "2_2") (pintype "passive"))
    )
    (net (code "60") (name "/CHIPA_VINP_X0") (class "Default")
      (node (ref "J16") (pin "28") (pinfunction "28_28") (pintype "passive"))
      (node (ref "P22") (pin "1") (pinfunction "X_1") (pintype "passive"))
      (node (ref "U11") (pin "3") (pinfunction "CN_3") (pintype "power_in"))
    )
    (net (code "61") (name "/CHIPA_VINP_X1") (class "Default")
      (node (ref "J16") (pin "37") (pinfunction "37_37") (pintype "passive"))
      (node (ref "P27") (pin "1") (pinfunction "X_1") (pintype "passive"))
      (node (ref "U14") (pin "3") (pinfunction "CN_3") (pintype "power_in"))
    )
    (net (code "62") (name "/CHIPA_VINP_Y0") (class "Default")
      (node (ref "J16") (pin "30") (pinfunction "30_30") (pintype "passive"))
      (node (ref "P54") (pin "1") (pinfunction "X_1") (pintype "passive"))
      (node (ref "U21") (pin "3") (pinfunction "CN_3") (pintype "power_in"))
    )
    (net (code "63") (name "/CHIPA_VINP_Y1") (class "Default")
      (node (ref "J16") (pin "35") (pinfunction "35_35") (pintype "passive"))
      (node (ref "P9") (pin "1") (pinfunction "X_1") (pintype "passive"))
      (node (ref "U4") (pin "3") (pinfunction "CN_3") (pintype "power_in"))
    )
    (net (code "64") (name "/CHIPA_VIN_SINGLEEND_OTA") (class "Default")
      (node (ref "J1") (pin "2") (pinfunction "2_2") (pintype "passive"))
      (node (ref "R5") (pin "2") (pinfunction "2_2") (pintype "passive"))
      (node (ref "R8") (pin "1") (pinfunction "1_1") (pintype "passive"))
    )
    (net (code "65") (name "/CHIPA_VN_X0") (class "Default")
      (node (ref "J16") (pin "16") (pinfunction "16_16") (pintype "passive"))
      (node (ref "P10") (pin "1") (pinfunction "X_1") (pintype "passive"))
      (node (ref "R14") (pin "2") (pinfunction "2_2") (pintype "passive"))
      (node (ref "U5") (pin "2") (pinfunction "CP_2") (pintype "power_in"))
    )
    (net (code "66") (name "/CHIPA_VN_X1") (class "Default")
      (node (ref "J16") (pin "19") (pinfunction "19_19") (pintype "passive"))
      (node (ref "P15") (pin "1") (pinfunction "X_1") (pintype "passive"))
      (node (ref "R19") (pin "2") (pinfunction "2_2") (pintype "passive"))
      (node (ref "U10") (pin "2") (pinfunction "CP_2") (pintype "power_in"))
    )
    (net (code "67") (name "/CHIPA_VN_Y0") (class "Default")
      (node (ref "J16") (pin "38") (pinfunction "38_38") (pintype "passive"))
      (node (ref "P38") (pin "1") (pinfunction "X_1") (pintype "passive"))
      (node (ref "R23") (pin "2") (pinfunction "2_2") (pintype "passive"))
      (node (ref "U17") (pin "2") (pinfunction "CP_2") (pintype "power_in"))
    )
    (net (code "68") (name "/CHIPA_VN_Y1") (class "Default")
      (node (ref "J16") (pin "29") (pinfunction "29_29") (pintype "passive"))
      (node (ref "P1") (pin "1") (pinfunction "X_1") (pintype "passive"))
      (node (ref "R3") (pin "2") (pinfunction "2_2") (pintype "passive"))
      (node (ref "U1") (pin "2") (pinfunction "CP_2") (pintype "power_in"))
    )
    (net (code "69") (name "/CHIPA_VOUTN_REPLICA") (class "Default")
      (node (ref "J16") (pin "6") (pinfunction "6_6") (pintype "passive"))
      (node (ref "P21") (pin "1") (pinfunction "1_1") (pintype "passive"))
      (node (ref "R9") (pin "2") (pinfunction "2_2") (pintype "passive"))
    )
    (net (code "70") (name "/CHIPA_VOUTN_REPLICA_INAMP") (class "Default")
      (node (ref "C16") (pin "2") (pinfunction "2_2") (pintype "passive"))
      (node (ref "J5") (pin "2") (pinfunction "2_2") (pintype "passive"))
      (node (ref "U6") (pin "10") (pinfunction "OUT+_10") (pintype "output"))
    )
    (net (code "71") (name "/CHIPA_VOUTN_X0") (class "Default")
      (node (ref "J16") (pin "10") (pinfunction "10_10") (pintype "passive"))
      (node (ref "P20") (pin "1") (pinfunction "1_1") (pintype "passive"))
      (node (ref "R12") (pin "2") (pinfunction "2_2") (pintype "passive"))
    )
    (net (code "72") (name "/CHIPA_VOUTN_X0_INAMP") (class "Default")
      (node (ref "C22") (pin "2") (pinfunction "2_2") (pintype "passive"))
      (node (ref "J7") (pin "2") (pinfunction "2_2") (pintype "passive"))
      (node (ref "U7") (pin "10") (pinfunction "OUT+_10") (pintype "output"))
    )
    (net (code "73") (name "/CHIPA_VOUTP_REPLICA") (class "Default")
      (node (ref "J16") (pin "8") (pinfunction "8_8") (pintype "passive"))
      (node (ref "P16") (pin "1") (pinfunction "1_1") (pintype "passive"))
      (node (ref "R10") (pin "2") (pinfunction "2_2") (pintype "passive"))
    )
    (net (code "74") (name "/CHIPA_VOUTP_REPLICA_INAMP") (class "Default")
      (node (ref "C13") (pin "1") (pinfunction "1_1") (pintype "passive"))
      (node (ref "J4") (pin "2") (pinfunction "2_2") (pintype "passive"))
      (node (ref "U6") (pin "11") (pinfunction "OUT-_11") (pintype "output"))
    )
    (net (code "75") (name "/CHIPA_VOUTP_X0") (class "Default")
      (node (ref "J16") (pin "12") (pinfunction "12_12") (pintype "passive"))
      (node (ref "P14") (pin "1") (pinfunction "1_1") (pintype "passive"))
      (node (ref "R13") (pin "2") (pinfunction "2_2") (pintype "passive"))
    )
    (net (code "76") (name "/CHIPA_VOUTP_X0_INAMP") (class "Default")
      (node (ref "C17") (pin "1") (pinfunction "1_1") (pintype "passive"))
      (node (ref "J6") (pin "2") (pinfunction "2_2") (pintype "passive"))
      (node (ref "U7") (pin "11") (pinfunction "OUT-_11") (pintype "output"))
    )
    (net (code "77") (name "/CHIPA_VP_X0") (class "Default")
      (node (ref "J16") (pin "24") (pinfunction "24_24") (pintype "passive"))
      (node (ref "P17") (pin "1") (pinfunction "X_1") (pintype "passive"))
      (node (ref "R21") (pin "2") (pinfunction "2_2") (pintype "passive"))
      (node (ref "U11") (pin "2") (pinfunction "CP_2") (pintype "power_in"))
    )
    (net (code "78") (name "/CHIPA_VP_X1") (class "Default")
      (node (ref "J16") (pin "21") (pinfunction "21_21") (pintype "passive"))
      (node (ref "P25") (pin "1") (pinfunction "X_1") (pintype "passive"))
      (node (ref "R22") (pin "2") (pinfunction "2_2") (pintype "passive"))
      (node (ref "U14") (pin "2") (pinfunction "CP_2") (pintype "power_in"))
    )
    (net (code "79") (name "/CHIPA_VP_Y0") (class "Default")
      (node (ref "J16") (pin "36") (pinfunction "36_36") (pintype "passive"))
      (node (ref "P51") (pin "1") (pinfunction "X_1") (pintype "passive"))
      (node (ref "R24") (pin "2") (pinfunction "2_2") (pintype "passive"))
      (node (ref "U21") (pin "2") (pinfunction "CP_2") (pintype "power_in"))
    )
    (net (code "80") (name "/CHIPA_VP_Y1") (class "Default")
      (node (ref "J16") (pin "31") (pinfunction "31_31") (pintype "passive"))
      (node (ref "P4") (pin "1") (pinfunction "X_1") (pintype "passive"))
      (node (ref "R11") (pin "2") (pinfunction "2_2") (pintype "passive"))
      (node (ref "U4") (pin "2") (pinfunction "CP_2") (pintype "power_in"))
    )
    (net (code "81") (name "/CHIPA_VS") (class "Default")
      (node (ref "J30") (pin "9") (pinfunction "9_9") (pintype "passive"))
      (node (ref "J33") (pin "64") (pinfunction "64_64") (pintype "passive"))
    )
    (net (code "82") (name "/CHIPA_VTRIG_COMP") (class "Default")
      (node (ref "J30") (pin "14") (pinfunction "14_14") (pintype "passive"))
      (node (ref "P28") (pin "5") (pinfunction "5_5") (pintype "passive"))
      (node (ref "U16") (pin "3") (pinfunction "VOUTC_3") (pintype "output"))
    )
    (net (code "83") (name "/CHIPA_VTUNE_PSEUDO") (class "Default")
      (node (ref "J30") (pin "16") (pinfunction "16_16") (pintype "passive"))
      (node (ref "P28") (pin "3") (pinfunction "3_3") (pintype "passive"))
      (node (ref "U16") (pin "8") (pinfunction "VOUTB_8") (pintype "output"))
    )
    (net (code "84") (name "/CHIPA_X0_CSN_SCL") (class "Default")
      (node (ref "U26") (pin "36") (pinfunction "CS2_36") (pintype "bidirectional"))
      (node (ref "U5") (pin "6") (pinfunction "SCL_6") (pintype "input"))
    )
    (net (code "85") (name "/CHIPA_X0_CSN_SDA") (class "Default")
      (node (ref "U26") (pin "35") (pinfunction "TX8_35") (pintype "bidirectional"))
      (node (ref "U5") (pin "1") (pinfunction "SDA_1") (pintype "bidirectional"))
    )
    (net (code "86") (name "/CHIPA_X0_CSP_SCL") (class "Default")
      (node (ref "U11") (pin "6") (pinfunction "SCL_6") (pintype "input"))
      (node (ref "U26") (pin "34") (pinfunction "RX8_34") (pintype "bidirectional"))
    )
    (net (code "87") (name "/CHIPA_X0_CSP_SDA") (class "Default")
      (node (ref "U11") (pin "1") (pinfunction "SDA_1") (pintype "bidirectional"))
      (node (ref "U26") (pin "33") (pinfunction "MCLK2_33") (pintype "bidirectional"))
    )
    (net (code "88") (name "/CHIPA_X1_CSN_SCL") (class "Default")
      (node (ref "U10") (pin "6") (pinfunction "SCL_6") (pintype "input"))
      (node (ref "U26") (pin "32") (pinfunction "OUT1B_32") (pintype "output"))
    )
    (net (code "89") (name "/CHIPA_X1_CSN_SDA") (class "Default")
      (node (ref "U10") (pin "1") (pinfunction "SDA_1") (pintype "bidirectional"))
      (node (ref "U26") (pin "31") (pinfunction "CTX3_31") (pintype "bidirectional"))
    )
    (net (code "90") (name "/CHIPA_X1_CSP_SCL") (class "Default")
      (node (ref "U14") (pin "6") (pinfunction "SCL_6") (pintype "input"))
      (node (ref "U26") (pin "30") (pinfunction "CRX3_30") (pintype "bidirectional"))
    )
    (net (code "91") (name "/CHIPA_X1_CSP_SDA") (class "Default")
      (node (ref "U14") (pin "1") (pinfunction "SDA_1") (pintype "bidirectional"))
      (node (ref "U26") (pin "29") (pinfunction "TX7_29") (pintype "bidirectional"))
    )
    (net (code "92") (name "/CHIPA_Y0_CSN_SCL") (class "Default")
      (node (ref "U17") (pin "6") (pinfunction "SCL_6") (pintype "input"))
      (node (ref "U26") (pin "28") (pinfunction "RX7_28") (pintype "bidirectional"))
    )
    (net (code "93") (name "/CHIPA_Y0_CSN_SDA") (class "Default")
      (node (ref "U17") (pin "1") (pinfunction "SDA_1") (pintype "bidirectional"))
      (node (ref "U26") (pin "27") (pinfunction "A13_27") (pintype "bidirectional"))
    )
    (net (code "94") (name "/CHIPA_Y0_CSP_SCL") (class "Default")
      (node (ref "U21") (pin "6") (pinfunction "SCL_6") (pintype "input"))
      (node (ref "U26") (pin "26") (pinfunction "A12_26") (pintype "bidirectional"))
    )
    (net (code "95") (name "/CHIPA_Y0_CSP_SDA") (class "Default")
      (node (ref "U21") (pin "1") (pinfunction "SDA_1") (pintype "bidirectional"))
      (node (ref "U26") (pin "25") (pinfunction "A11_25") (pintype "bidirectional"))
    )
    (net (code "96") (name "/CHIPA_Y1_CSN_SCL") (class "Default")
      (node (ref "U1") (pin "6") (pinfunction "SCL_6") (pintype "input"))
      (node (ref "U26") (pin "24") (pinfunction "A10_24") (pintype "bidirectional"))
    )
    (net (code "97") (name "/CHIPA_Y1_CSN_SDA") (class "Default")
      (node (ref "U1") (pin "1") (pinfunction "SDA_1") (pintype "bidirectional"))
      (node (ref "U26") (pin "23") (pinfunction "A9_23") (pintype "bidirectional"))
    )
    (net (code "98") (name "/CHIPA_Y1_CSP_SCL") (class "Default")
      (node (ref "U26") (pin "22") (pinfunction "A8_22") (pintype "bidirectional"))
      (node (ref "U4") (pin "6") (pinfunction "SCL_6") (pintype "input"))
    )
    (net (code "99") (name "/CHIPA_Y1_CSP_SDA") (class "Default")
      (node (ref "U26") (pin "21") (pinfunction "A7_21") (pintype "bidirectional"))
      (node (ref "U4") (pin "1") (pinfunction "SDA_1") (pintype "bidirectional"))
    )
    (net (code "100") (name "/CHIPB_A0") (class "Default")
      (node (ref "P79") (pin "2") (pinfunction "2_2") (pintype "passive"))
      (node (ref "U56") (pin "4") (pinfunction "A0_4") (pintype "input"))
      (node (ref "U57") (pin "4") (pinfunction "A0_4") (pintype "input"))
    )
    (net (code "101") (name "/CHIPB_A1") (class "Default")
      (node (ref "P78") (pin "2") (pinfunction "2_2") (pintype "passive"))
      (node (ref "U56") (pin "5") (pinfunction "A1_5") (pintype "input"))
      (node (ref "U57") (pin "5") (pinfunction "A1_5") (pintype "input"))
    )
    (net (code "102") (name "/CHIPB_A2") (class "Default")
      (node (ref "P77") (pin "2") (pinfunction "2_2") (pintype "passive"))
      (node (ref "U56") (pin "1") (pinfunction "A2_1") (pintype "input"))
      (node (ref "U57") (pin "1") (pinfunction "A2_1") (pintype "input"))
    )
    (net (code "103") (name "/CHIPB_ACK") (class "Default")
      (node (ref "J32") (pin "37") (pinfunction "37_37") (pintype "passive"))
      (node (ref "J33") (pin "6") (pinfunction "6_6") (pintype "passive"))
    )
    (net (code "104") (name "/CHIPB_ADDRX0") (class "Default")
      (node (ref "J32") (pin "25") (pinfunction "25_25") (pintype "passive"))
      (node (ref "J33") (pin "15") (pinfunction "15_15") (pintype "passive"))
    )
    (net (code "105") (name "/CHIPB_ADDRY0") (class "Default")
      (node (ref "J32") (pin "23") (pinfunction "23_23") (pintype "passive"))
      (node (ref "J33") (pin "18") (pinfunction "18_18") (pintype "passive"))
    )
    (net (code "106") (name "/CHIPB_AER_DIS") (class "Default")
      (node (ref "J32") (pin "21") (pinfunction "21_21") (pintype "passive"))
      (node (ref "J33") (pin "21") (pinfunction "21_21") (pintype "passive"))
    )
    (net (code "107") (name "/CHIPB_CLK") (class "Default")
      (node (ref "J27") (pin "1") (pinfunction "1_1") (pintype "passive"))
      (node (ref "J32") (pin "11") (pinfunction "11_11") (pintype "passive"))
    )
    (net (code "108") (name "/CHIPB_CSb_IDAC") (class "Default")
      (node (ref "J33") (pin "57") (pinfunction "57_57") (pintype "passive"))
      (node (ref "U45") (pin "14") (pinfunction "*CS_14") (pintype "input"))
    )
    (net (code "109") (name "/CHIPB_CSb_VDAC") (class "Default")
      (node (ref "J33") (pin "54") (pinfunction "54_54") (pintype "passive"))
      (node (ref "U43") (pin "14") (pinfunction "*CS_14") (pintype "input"))
    )
    (net (code "110") (name "/CHIPB_CT_MODE") (class "Default")
      (node (ref "J32") (pin "15") (pinfunction "15_15") (pintype "passive"))
      (node (ref "J33") (pin "30") (pinfunction "30_30") (pintype "passive"))
    )
    (net (code "111") (name "/CHIPB_DIG_RES0") (class "Default")
      (node (ref "J32") (pin "7") (pinfunction "7_7") (pintype "passive"))
      (node (ref "J33") (pin "36") (pinfunction "36_36") (pintype "passive"))
    )
    (net (code "112") (name "/CHIPB_DIG_RES1") (class "Default")
      (node (ref "J32") (pin "5") (pinfunction "5_5") (pintype "passive"))
      (node (ref "J33") (pin "39") (pinfunction "39_39") (pintype "passive"))
    )
    (net (code "113") (name "/CHIPB_DIG_RES2") (class "Default")
      (node (ref "J32") (pin "3") (pinfunction "3_3") (pintype "passive"))
      (node (ref "J33") (pin "42") (pinfunction "42_42") (pintype "passive"))
    )
    (net (code "114") (name "/CHIPB_DIG_RES3") (class "Default")
      (node (ref "J32") (pin "1") (pinfunction "1_1") (pintype "passive"))
      (node (ref "J33") (pin "45") (pinfunction "45_45") (pintype "passive"))
    )
    (net (code "115") (name "/CHIPB_GAIN_HI") (class "Default")
      (node (ref "J32") (pin "13") (pinfunction "13_13") (pintype "passive"))
      (node (ref "J33") (pin "33") (pinfunction "33_33") (pintype "passive"))
    )
    (net (code "116") (name "/CHIPB_IBIAS") (class "Default")
      (node (ref "J32") (pin "12") (pinfunction "12_12") (pintype "passive"))
      (node (ref "P75") (pin "2") (pinfunction "2_2") (pintype "passive"))
    )
    (net (code "117") (name "/CHIPB_IBIAS_ADAPT") (class "Default")
      (node (ref "J32") (pin "10") (pinfunction "10_10") (pintype "passive"))
      (node (ref "P74") (pin "2") (pinfunction "2_2") (pintype "passive"))
    )
    (net (code "118") (name "/CHIPB_IBIAS_ADAPT_PRE") (class "Default")
      (node (ref "P74") (pin "1") (pinfunction "1_1") (pintype "passive"))
      (node (ref "U52") (pin "3") (pinfunction "COLLECTOR_3") (pintype "passive"))
    )
    (net (code "119") (name "/CHIPB_IBIAS_AFE") (class "Default")
      (node (ref "J32") (pin "8") (pinfunction "8_8") (pintype "passive"))
      (node (ref "P73") (pin "2") (pinfunction "2_2") (pintype "passive"))
    )
    (net (code "120") (name "/CHIPB_IBIAS_AFE_PRE") (class "Default")
      (node (ref "P73") (pin "1") (pinfunction "1_1") (pintype "passive"))
      (node (ref "U49") (pin "3") (pinfunction "COLLECTOR_3") (pintype "passive"))
    )
    (net (code "121") (name "/CHIPB_IBIAS_PRE") (class "Default")
      (node (ref "P75") (pin "1") (pinfunction "1_1") (pintype "passive"))
      (node (ref "U54") (pin "3") (pinfunction "COLLECTOR_3") (pintype "passive"))
    )
    (net (code "122") (name "/CHIPB_IBIAS_SLEW") (class "Default")
      (node (ref "J32") (pin "6") (pinfunction "6_6") (pintype "passive"))
      (node (ref "P72") (pin "2") (pinfunction "2_2") (pintype "passive"))
    )
    (net (code "123") (name "/CHIPB_IBIAS_SLEW_PRE") (class "Default")
      (node (ref "P72") (pin "1") (pinfunction "1_1") (pintype "passive"))
      (node (ref "U47") (pin "3") (pinfunction "COLLECTOR_3") (pintype "passive"))
    )
    (net (code "124") (name "/CHIPB_LDACb") (class "Default")
      (node (ref "J33") (pin "51") (pinfunction "51_51") (pintype "passive"))
      (node (ref "U43") (pin "18") (pinfunction "*LOADDACS_18") (pintype "passive"))
      (node (ref "U45") (pin "18") (pinfunction "*LOADDACS_18") (pintype "passive"))
    )
    (net (code "125") (name "/CHIPB_RATIOMODE0") (class "Default")
      (node (ref "J32") (pin "19") (pinfunction "19_19") (pintype "passive"))
      (node (ref "J33") (pin "24") (pinfunction "24_24") (pintype "passive"))
    )
    (net (code "126") (name "/CHIPB_RATIOMODE1") (class "Default")
      (node (ref "J32") (pin "17") (pinfunction "17_17") (pintype "passive"))
      (node (ref "J33") (pin "27") (pinfunction "27_27") (pintype "passive"))
    )
    (net (code "127") (name "/CHIPB_REQOFF") (class "Default")
      (node (ref "J32") (pin "33") (pinfunction "33_33") (pintype "passive"))
      (node (ref "J33") (pin "12") (pinfunction "12_12") (pintype "passive"))
    )
    (net (code "128") (name "/CHIPB_REQON") (class "Default")
      (node (ref "J32") (pin "35") (pinfunction "35_35") (pintype "passive"))
      (node (ref "J33") (pin "9") (pinfunction "9_9") (pintype "passive"))
    )
    (net (code "129") (name "/CHIPB_RESETb") (class "Default")
      (node (ref "J33") (pin "48") (pinfunction "48_48") (pintype "passive"))
      (node (ref "U43") (pin "19") (pinfunction "*RESET_19") (pintype "input"))
      (node (ref "U45") (pin "19") (pinfunction "*RESET_19") (pintype "input"))
    )
    (net (code "130") (name "/CHIPB_RST") (class "Default")
      (node (ref "J32") (pin "39") (pinfunction "39_39") (pintype "passive"))
      (node (ref "J33") (pin "3") (pinfunction "3_3") (pintype "passive"))
    )
    (net (code "131") (name "/CHIPB_SCLK") (class "Default")
      (node (ref "J33") (pin "60") (pinfunction "60_60") (pintype "passive"))
      (node (ref "U43") (pin "13") (pinfunction "CLK_13") (pintype "passive"))
      (node (ref "U45") (pin "13") (pinfunction "CLK_13") (pintype "passive"))
    )
    (net (code "132") (name "/CHIPB_SDI") (class "Default")
      (node (ref "J33") (pin "63") (pinfunction "63_63") (pintype "passive"))
      (node (ref "U43") (pin "12") (pinfunction "SDI_12") (pintype "input"))
      (node (ref "U45") (pin "12") (pinfunction "SDI_12") (pintype "input"))
    )
    (net (code "133") (name "/CHIPB_VBIAS") (class "Default")
      (node (ref "U45") (pin "3") (pinfunction "VOUTC_3") (pintype "output"))
      (node (ref "U53") (pin "3") (pinfunction "IN+_3") (pintype "input"))
    )
    (net (code "134") (name "/CHIPB_VBIAS_ADAPT") (class "Default")
      (node (ref "U45") (pin "2") (pinfunction "VOUTD_2") (pintype "output"))
      (node (ref "U51") (pin "3") (pinfunction "IN+_3") (pintype "input"))
    )
    (net (code "135") (name "/CHIPB_VBIAS_AFE") (class "Default")
      (node (ref "U45") (pin "8") (pinfunction "VOUTB_8") (pintype "output"))
      (node (ref "U48") (pin "3") (pinfunction "IN+_3") (pintype "input"))
    )
    (net (code "136") (name "/CHIPB_VBIAS_SLEW") (class "Default")
      (node (ref "U45") (pin "9") (pinfunction "VOUTA_9") (pintype "output"))
      (node (ref "U46") (pin "3") (pinfunction "IN+_3") (pintype "input"))
    )
    (net (code "137") (name "/CHIPB_VCM") (class "Default")
      (node (ref "J23") (pin "1") (pinfunction "1_1") (pintype "passive"))
      (node (ref "J23") (pin "11") (pinfunction "11_11") (pintype "passive"))
      (node (ref "J23") (pin "13") (pinfunction "13_13") (pintype "passive"))
      (node (ref "J23") (pin "14") (pinfunction "14_14") (pintype "passive"))
      (node (ref "J23") (pin "15") (pinfunction "15_15") (pintype "passive"))
      (node (ref "J23") (pin "17") (pinfunction "17_17") (pintype "passive"))
      (node (ref "J23") (pin "18") (pinfunction "18_18") (pintype "passive"))
      (node (ref "J23") (pin "22") (pinfunction "22_22") (pintype "passive"))
      (node (ref "J23") (pin "23") (pinfunction "23_23") (pintype "passive"))
      (node (ref "J23") (pin "26") (pinfunction "26_26") (pintype "passive"))
      (node (ref "J23") (pin "27") (pinfunction "27_27") (pintype "passive"))
      (node (ref "J23") (pin "3") (pinfunction "3_3") (pintype "passive"))
      (node (ref "J23") (pin "33") (pinfunction "33_33") (pintype "passive"))
      (node (ref "J23") (pin "34") (pinfunction "34_34") (pintype "passive"))
      (node (ref "J23") (pin "40") (pinfunction "40_40") (pintype "passive"))
      (node (ref "J23") (pin "5") (pinfunction "5_5") (pintype "passive"))
      (node (ref "J23") (pin "7") (pinfunction "7_7") (pintype "passive"))
      (node (ref "J23") (pin "9") (pinfunction "9_9") (pintype "passive"))
      (node (ref "J23") (pin "S1") (pinfunction "SHIELD_S1") (pintype "passive"))
      (node (ref "J23") (pin "S2") (pinfunction "SHIELD_S2") (pintype "passive"))
      (node (ref "J32") (pin "30") (pinfunction "30_30") (pintype "passive"))
      (node (ref "P30") (pin "2") (pinfunction "Y_2") (pintype "passive"))
      (node (ref "P31") (pin "2") (pinfunction "Y_2") (pintype "passive"))
      (node (ref "P32") (pin "2") (pinfunction "Y_2") (pintype "passive"))
      (node (ref "P33") (pin "2") (pinfunction "Y_2") (pintype "passive"))
      (node (ref "P35") (pin "2") (pinfunction "Y_2") (pintype "passive"))
      (node (ref "P36") (pin "2") (pinfunction "Y_2") (pintype "passive"))
      (node (ref "P39") (pin "2") (pinfunction "Y_2") (pintype "passive"))
      (node (ref "P40") (pin "2") (pinfunction "Y_2") (pintype "passive"))
      (node (ref "P43") (pin "2") (pinfunction "Y_2") (pintype "passive"))
      (node (ref "P44") (pin "2") (pinfunction "Y_2") (pintype "passive"))
      (node (ref "P46") (pin "2") (pinfunction "Y_2") (pintype "passive"))
      (node (ref "P47") (pin "2") (pinfunction "Y_2") (pintype "passive"))
      (node (ref "P49") (pin "2") (pinfunction "Y_2") (pintype "passive"))
      (node (ref "P50") (pin "2") (pinfunction "Y_2") (pintype "passive"))
      (node (ref "P52") (pin "2") (pinfunction "Y_2") (pintype "passive"))
      (node (ref "P53") (pin "2") (pinfunction "Y_2") (pintype "passive"))
      (node (ref "P70") (pin "1") (pinfunction "1_1") (pintype "passive"))
      (node (ref "P85") (pin "1") (pinfunction "1_1") (pintype "passive"))
      (node (ref "U43") (pin "9") (pinfunction "VOUTA_9") (pintype "output"))
    )
    (net (code "138") (name "/CHIPB_VD") (class "Default")
      (node (ref "J32") (pin "4") (pinfunction "4_4") (pintype "passive"))
      (node (ref "J33") (pin "72") (pinfunction "72_72") (pintype "passive"))
    )
    (net (code "139") (name "/CHIPB_VG") (class "Default")
      (node (ref "J32") (pin "2") (pinfunction "2_2") (pintype "passive"))
      (node (ref "J33") (pin "69") (pinfunction "69_69") (pintype "passive"))
    )
    (net (code "140") (name "/CHIPB_VINN_REPLICA") (class "Default")
      (node (ref "J23") (pin "4") (pinfunction "4_4") (pintype "passive"))
      (node (ref "J38") (pin "2") (pinfunction "2_2") (pintype "passive"))
      (node (ref "R35") (pin "2") (pinfunction "2_2") (pintype "passive"))
    )
    (net (code "141") (name "/CHIPB_VINN_X0") (class "Default")
      (node (ref "J23") (pin "20") (pinfunction "20_20") (pintype "passive"))
      (node (ref "P50") (pin "1") (pinfunction "X_1") (pintype "passive"))
    )
    (net (code "142") (name "/CHIPB_VINN_X1") (class "Default")
      (node (ref "J23") (pin "39") (pinfunction "39_39") (pintype "passive"))
      (node (ref "P36") (pin "1") (pinfunction "X_1") (pintype "passive"))
    )
    (net (code "143") (name "/CHIPB_VINN_Y0") (class "Default")
      (node (ref "J23") (pin "32") (pinfunction "32_32") (pintype "passive"))
      (node (ref "P49") (pin "1") (pinfunction "X_1") (pintype "passive"))
    )
    (net (code "144") (name "/CHIPB_VINN_Y1") (class "Default")
      (node (ref "J23") (pin "25") (pinfunction "25_25") (pintype "passive"))
      (node (ref "P35") (pin "1") (pinfunction "X_1") (pintype "passive"))
    )
    (net (code "145") (name "/CHIPB_VINP_REPLICA") (class "Default")
      (node (ref "J23") (pin "2") (pinfunction "2_2") (pintype "passive"))
      (node (ref "J37") (pin "2") (pinfunction "2_2") (pintype "passive"))
      (node (ref "R36") (pin "2") (pinfunction "2_2") (pintype "passive"))
    )
    (net (code "146") (name "/CHIPB_VINP_X0") (class "Default")
      (node (ref "J23") (pin "28") (pinfunction "28_28") (pintype "passive"))
      (node (ref "P53") (pin "1") (pinfunction "X_1") (pintype "passive"))
    )
    (net (code "147") (name "/CHIPB_VINP_X1") (class "Default")
      (node (ref "J23") (pin "37") (pinfunction "37_37") (pintype "passive"))
      (node (ref "P40") (pin "1") (pinfunction "X_1") (pintype "passive"))
    )
    (net (code "148") (name "/CHIPB_VINP_Y0") (class "Default")
      (node (ref "J23") (pin "30") (pinfunction "30_30") (pintype "passive"))
      (node (ref "P52") (pin "1") (pinfunction "X_1") (pintype "passive"))
    )
    (net (code "149") (name "/CHIPB_VINP_Y1") (class "Default")
      (node (ref "J23") (pin "35") (pinfunction "35_35") (pintype "passive"))
      (node (ref "P39") (pin "1") (pinfunction "X_1") (pintype "passive"))
    )
    (net (code "150") (name "/CHIPB_VIN_SINGLEEND_OTA") (class "Default")
      (node (ref "J36") (pin "2") (pinfunction "2_2") (pintype "passive"))
      (node (ref "R38") (pin "2") (pinfunction "2_2") (pintype "passive"))
      (node (ref "R41") (pin "1") (pinfunction "1_1") (pintype "passive"))
    )
    (net (code "151") (name "/CHIPB_VN_X0") (class "Default")
      (node (ref "J23") (pin "16") (pinfunction "16_16") (pintype "passive"))
      (node (ref "P44") (pin "1") (pinfunction "X_1") (pintype "passive"))
    )
    (net (code "152") (name "/CHIPB_VN_X1") (class "Default")
      (node (ref "J23") (pin "19") (pinfunction "19_19") (pintype "passive"))
      (node (ref "P31") (pin "1") (pinfunction "X_1") (pintype "passive"))
    )
    (net (code "153") (name "/CHIPB_VN_Y0") (class "Default")
      (node (ref "J23") (pin "38") (pinfunction "38_38") (pintype "passive"))
      (node (ref "P43") (pin "1") (pinfunction "X_1") (pintype "passive"))
    )
    (net (code "154") (name "/CHIPB_VN_Y1") (class "Default")
      (node (ref "J23") (pin "29") (pinfunction "29_29") (pintype "passive"))
      (node (ref "P30") (pin "1") (pinfunction "X_1") (pintype "passive"))
    )
    (net (code "155") (name "/CHIPB_VOUTN_REPLICA") (class "Default")
      (node (ref "J23") (pin "6") (pinfunction "6_6") (pintype "passive"))
      (node (ref "P87") (pin "1") (pinfunction "1_1") (pintype "passive"))
      (node (ref "R42") (pin "2") (pinfunction "2_2") (pintype "passive"))
    )
    (net (code "156") (name "/CHIPB_VOUTN_REPLICA_INAMP") (class "Default")
      (node (ref "C124") (pin "2") (pinfunction "2_2") (pintype "passive"))
      (node (ref "J40") (pin "2") (pinfunction "2_2") (pintype "passive"))
      (node (ref "U56") (pin "10") (pinfunction "OUT+_10") (pintype "output"))
    )
    (net (code "157") (name "/CHIPB_VOUTN_X0") (class "Default")
      (node (ref "J23") (pin "10") (pinfunction "10_10") (pintype "passive"))
      (node (ref "P86") (pin "1") (pinfunction "1_1") (pintype "passive"))
      (node (ref "R44") (pin "2") (pinfunction "2_2") (pintype "passive"))
    )
    (net (code "158") (name "/CHIPB_VOUTN_X0_INAMP") (class "Default")
      (node (ref "C130") (pin "2") (pinfunction "2_2") (pintype "passive"))
      (node (ref "J42") (pin "2") (pinfunction "2_2") (pintype "passive"))
      (node (ref "U57") (pin "10") (pinfunction "OUT+_10") (pintype "output"))
    )
    (net (code "159") (name "/CHIPB_VOUTP_REPLICA") (class "Default")
      (node (ref "J23") (pin "8") (pinfunction "8_8") (pintype "passive"))
      (node (ref "P84") (pin "1") (pinfunction "1_1") (pintype "passive"))
      (node (ref "R43") (pin "2") (pinfunction "2_2") (pintype "passive"))
    )
    (net (code "160") (name "/CHIPB_VOUTP_REPLICA_INAMP") (class "Default")
      (node (ref "C121") (pin "1") (pinfunction "1_1") (pintype "passive"))
      (node (ref "J39") (pin "2") (pinfunction "2_2") (pintype "passive"))
      (node (ref "U56") (pin "11") (pinfunction "OUT-_11") (pintype "output"))
    )
    (net (code "161") (name "/CHIPB_VOUTP_X0") (class "Default")
      (node (ref "J23") (pin "12") (pinfunction "12_12") (pintype "passive"))
      (node (ref "P83") (pin "1") (pinfunction "1_1") (pintype "passive"))
      (node (ref "R45") (pin "2") (pinfunction "2_2") (pintype "passive"))
    )
    (net (code "162") (name "/CHIPB_VOUTP_X0_INAMP") (class "Default")
      (node (ref "C125") (pin "1") (pinfunction "1_1") (pintype "passive"))
      (node (ref "J41") (pin "2") (pinfunction "2_2") (pintype "passive"))
      (node (ref "U57") (pin "11") (pinfunction "OUT-_11") (pintype "output"))
    )
    (net (code "163") (name "/CHIPB_VP_X0") (class "Default")
      (node (ref "J23") (pin "24") (pinfunction "24_24") (pintype "passive"))
      (node (ref "P47") (pin "1") (pinfunction "X_1") (pintype "passive"))
    )
    (net (code "164") (name "/CHIPB_VP_X1") (class "Default")
      (node (ref "J23") (pin "21") (pinfunction "21_21") (pintype "passive"))
      (node (ref "P33") (pin "1") (pinfunction "X_1") (pintype "passive"))
    )
    (net (code "165") (name "/CHIPB_VP_Y0") (class "Default")
      (node (ref "J23") (pin "36") (pinfunction "36_36") (pintype "passive"))
      (node (ref "P46") (pin "1") (pinfunction "X_1") (pintype "passive"))
    )
    (net (code "166") (name "/CHIPB_VP_Y1") (class "Default")
      (node (ref "J23") (pin "31") (pinfunction "31_31") (pintype "passive"))
      (node (ref "P32") (pin "1") (pinfunction "X_1") (pintype "passive"))
    )
    (net (code "167") (name "/CHIPB_VREF_2P5V") (class "Default")
      (node (ref "P71") (pin "3") (pinfunction "3_3") (pintype "passive"))
      (node (ref "U44") (pin "2") (pinfunction "VOUT_2") (pintype "output"))
    )
    (net (code "168") (name "/CHIPB_VS") (class "Default")
      (node (ref "J32") (pin "9") (pinfunction "9_9") (pintype "passive"))
      (node (ref "J33") (pin "66") (pinfunction "66_66") (pintype "passive"))
    )
    (net (code "169") (name "/CHIPB_VTRIG_COMP") (class "Default")
      (node (ref "J32") (pin "14") (pinfunction "14_14") (pintype "passive"))
      (node (ref "P70") (pin "5") (pinfunction "5_5") (pintype "passive"))
      (node (ref "U43") (pin "3") (pinfunction "VOUTC_3") (pintype "output"))
    )
    (net (code "170") (name "/CHIPB_VTUNE_PSEUDO") (class "Default")
      (node (ref "J32") (pin "16") (pinfunction "16_16") (pintype "passive"))
      (node (ref "P70") (pin "3") (pinfunction "3_3") (pintype "passive"))
      (node (ref "U43") (pin "8") (pinfunction "VOUTB_8") (pintype "output"))
    )
    (net (code "171") (name "/CSb_IDAC") (class "Default")
      (node (ref "J33") (pin "56") (pinfunction "56_56") (pintype "passive"))
      (node (ref "J34") (pin "D20") (pinfunction "D20_D20") (pintype "passive"))
      (node (ref "U26") (pin "18") (pinfunction "A4_18") (pintype "bidirectional"))
    )
    (net (code "172") (name "/CSb_VDAC") (class "Default")
      (node (ref "J33") (pin "53") (pinfunction "53_53") (pintype "passive"))
      (node (ref "J34") (pin "D18") (pinfunction "D18_D18") (pintype "passive"))
      (node (ref "U26") (pin "17") (pinfunction "A3_17") (pintype "bidirectional"))
    )
    (net (code "173") (name "/CT_MODE") (class "Default")
      (node (ref "J33") (pin "29") (pinfunction "29_29") (pintype "passive"))
      (node (ref "J34") (pin "C27") (pinfunction "C27_C27") (pintype "passive"))
      (node (ref "U26") (pin "9") (pinfunction "OUT1C_9") (pintype "output"))
    )
    (net (code "174") (name "/DGND") (class "Default")
      (node (ref "J30") (pin "24") (pinfunction "24_24") (pintype "passive"))
      (node (ref "J32") (pin "24") (pinfunction "24_24") (pintype "passive"))
      (node (ref "R17") (pin "2") (pinfunction "2_2") (pintype "passive"))
    )
    (net (code "175") (name "/DIG_RES0") (class "Default")
      (node (ref "J33") (pin "35") (pinfunction "35_35") (pintype "passive"))
      (node (ref "P66") (pin "1") (pinfunction "1_1") (pintype "passive"))
      (node (ref "U39") (pin "2") (pinfunction "A_2") (pintype "input"))
    )
    (net (code "176") (name "/DIG_RES0_EXT") (class "Default")
      (node (ref "J34") (pin "D09") (pinfunction "D09_D09") (pintype "passive"))
      (node (ref "P66") (pin "2") (pinfunction "2_2") (pintype "passive"))
      (node (ref "U26") (pin "11") (pinfunction "MOSI_11") (pintype "bidirectional"))
      (node (ref "U39") (pin "4") (pinfunction "Y_4") (pintype "output"))
    )
    (net (code "177") (name "/DIG_RES1") (class "Default")
      (node (ref "J33") (pin "38") (pinfunction "38_38") (pintype "passive"))
      (node (ref "P67") (pin "1") (pinfunction "1_1") (pintype "passive"))
      (node (ref "U40") (pin "2") (pinfunction "A_2") (pintype "input"))
    )
    (net (code "178") (name "/DIG_RES1_EXT") (class "Default")
      (node (ref "J34") (pin "D11") (pinfunction "D11_D11") (pintype "passive"))
      (node (ref "P67") (pin "2") (pinfunction "2_2") (pintype "passive"))
      (node (ref "U26") (pin "12") (pinfunction "MISO_12") (pintype "bidirectional"))
      (node (ref "U40") (pin "4") (pinfunction "Y_4") (pintype "output"))
    )
    (net (code "179") (name "/DIG_RES2") (class "Default")
      (node (ref "J33") (pin "41") (pinfunction "41_41") (pintype "passive"))
      (node (ref "P68") (pin "1") (pinfunction "1_1") (pintype "passive"))
      (node (ref "U41") (pin "2") (pinfunction "A_2") (pintype "input"))
    )
    (net (code "180") (name "/DIG_RES2_EXT") (class "Default")
      (node (ref "J34") (pin "D12") (pinfunction "D12_D12") (pintype "passive"))
      (node (ref "P68") (pin "2") (pinfunction "2_2") (pintype "passive"))
      (node (ref "U26") (pin "13") (pinfunction "SCK_13") (pintype "bidirectional"))
      (node (ref "U41") (pin "4") (pinfunction "Y_4") (pintype "output"))
    )
    (net (code "181") (name "/DIG_RES3") (class "Default")
      (node (ref "J33") (pin "44") (pinfunction "44_44") (pintype "passive"))
      (node (ref "P69") (pin "1") (pinfunction "1_1") (pintype "passive"))
      (node (ref "U42") (pin "2") (pinfunction "A_2") (pintype "input"))
    )
    (net (code "182") (name "/DIG_RES3_EXT") (class "Default")
      (node (ref "J34") (pin "D14") (pinfunction "D14_D14") (pintype "passive"))
      (node (ref "P69") (pin "2") (pinfunction "2_2") (pintype "passive"))
      (node (ref "U26") (pin "14") (pinfunction "A0_14") (pintype "bidirectional"))
      (node (ref "U42") (pin "4") (pinfunction "Y_4") (pintype "output"))
    )
    (net (code "183") (name "/FPGA_3P3V") (class "Default")
      (node (ref "J34") (pin "C39") (pinfunction "C39_C39") (pintype "passive"))
      (node (ref "P82") (pin "1") (pinfunction "1_1") (pintype "passive"))
    )
    (net (code "184") (name "/FPGA_12V") (class "Default")
      (node (ref "J34") (pin "C35") (pinfunction "C35_C35") (pintype "passive"))
      (node (ref "P81") (pin "1") (pinfunction "1_1") (pintype "passive"))
    )
    (net (code "185") (name "/FPGA_TEST0") (class "Default")
      (node (ref "J34") (pin "H07") (pinfunction "H07_H07") (pintype "passive"))
      (node (ref "P80") (pin "1") (pinfunction "1_1") (pintype "passive"))
    )
    (net (code "186") (name "/FPGA_VADJ") (class "Default")
      (node (ref "J34") (pin "G39") (pinfunction "G39_G39") (pintype "passive"))
      (node (ref "P88") (pin "1") (pinfunction "1_1") (pintype "passive"))
    )
    (net (code "187") (name "/GAIN_HI") (class "Default")
      (node (ref "J33") (pin "32") (pinfunction "32_32") (pintype "passive"))
      (node (ref "J34") (pin "D08") (pinfunction "D08_D08") (pintype "passive"))
      (node (ref "U26") (pin "10") (pinfunction "CS1_10") (pintype "bidirectional"))
    )
    (net (code "188") (name "/LDACb") (class "Default")
      (node (ref "J33") (pin "50") (pinfunction "50_50") (pintype "passive"))
      (node (ref "J34") (pin "D17") (pinfunction "D17_D17") (pintype "passive"))
      (node (ref "U26") (pin "16") (pinfunction "A2_16") (pintype "bidirectional"))
    )
    (net (code "189") (name "/RATIOMODE0") (class "Default")
      (node (ref "J33") (pin "23") (pinfunction "23_23") (pintype "passive"))
      (node (ref "J34") (pin "C23") (pinfunction "C23_C23") (pintype "passive"))
      (node (ref "U26") (pin "7") (pinfunction "RX2_7") (pintype "bidirectional"))
    )
    (net (code "190") (name "/RATIOMODE1") (class "Default")
      (node (ref "J33") (pin "26") (pinfunction "26_26") (pintype "passive"))
      (node (ref "J34") (pin "C26") (pinfunction "C26_C26") (pintype "passive"))
      (node (ref "U26") (pin "8") (pinfunction "TX2_8") (pintype "bidirectional"))
    )
    (net (code "191") (name "/REQOFF") (class "Default")
      (node (ref "J33") (pin "11") (pinfunction "11_11") (pintype "passive"))
      (node (ref "P63") (pin "1") (pinfunction "1_1") (pintype "passive"))
      (node (ref "U36") (pin "2") (pinfunction "A_2") (pintype "input"))
    )
    (net (code "192") (name "/REQOFF_EXT") (class "Default")
      (node (ref "J34") (pin "C15") (pinfunction "C15_C15") (pintype "passive"))
      (node (ref "P63") (pin "2") (pinfunction "2_2") (pintype "passive"))
      (node (ref "U26") (pin "3") (pinfunction "LRCLK2_3") (pintype "bidirectional"))
      (node (ref "U36") (pin "4") (pinfunction "Y_4") (pintype "output"))
    )
    (net (code "193") (name "/REQON") (class "Default")
      (node (ref "J33") (pin "8") (pinfunction "8_8") (pintype "passive"))
      (node (ref "P62") (pin "1") (pinfunction "1_1") (pintype "passive"))
      (node (ref "U35") (pin "2") (pinfunction "A_2") (pintype "input"))
    )
    (net (code "194") (name "/REQON_EXT") (class "Default")
      (node (ref "J34") (pin "C14") (pinfunction "C14_C14") (pintype "passive"))
      (node (ref "P62") (pin "2") (pinfunction "2_2") (pintype "passive"))
      (node (ref "U26") (pin "2") (pinfunction "OUT2_2") (pintype "output"))
      (node (ref "U35") (pin "4") (pinfunction "Y_4") (pintype "output"))
    )
    (net (code "195") (name "/RESETb") (class "Default")
      (node (ref "J33") (pin "47") (pinfunction "47_47") (pintype "passive"))
      (node (ref "J34") (pin "D15") (pinfunction "D15_D15") (pintype "passive"))
      (node (ref "U26") (pin "15") (pinfunction "A1_15") (pintype "bidirectional"))
    )
    (net (code "196") (name "/RST") (class "Default")
      (node (ref "J33") (pin "2") (pinfunction "2_2") (pintype "passive"))
      (node (ref "P61") (pin "2") (pinfunction "2_2") (pintype "passive"))
      (node (ref "U23") (pin "4") (pinfunction "Y_4") (pintype "output"))
    )
    (net (code "197") (name "/RST_EXT") (class "Default")
      (node (ref "J34") (pin "C10") (pinfunction "C10_C10") (pintype "passive"))
      (node (ref "P61") (pin "1") (pinfunction "1_1") (pintype "passive"))
      (node (ref "U23") (pin "2") (pinfunction "A_2") (pintype "input"))
      (node (ref "U26") (pin "0") (pinfunction "RX1_0") (pintype "bidirectional"))
    )
    (net (code "198") (name "/SCLK") (class "Default")
      (node (ref "J33") (pin "59") (pinfunction "59_59") (pintype "passive"))
      (node (ref "J34") (pin "D21") (pinfunction "D21_D21") (pintype "passive"))
      (node (ref "U26") (pin "19") (pinfunction "A5_19") (pintype "bidirectional"))
    )
    (net (code "199") (name "/SDI") (class "Default")
      (node (ref "J33") (pin "62") (pinfunction "62_62") (pintype "passive"))
      (node (ref "J34") (pin "D23") (pinfunction "D23_D23") (pintype "passive"))
      (node (ref "U26") (pin "20") (pinfunction "A6_20") (pintype "bidirectional"))
    )
    (net (code "200") (name "/VD") (class "Default")
      (node (ref "J26") (pin "1") (pinfunction "1_1") (pintype "passive"))
      (node (ref "J33") (pin "71") (pinfunction "71_71") (pintype "passive"))
      (node (ref "P42") (pin "1") (pinfunction "1_1") (pintype "passive"))
    )
    (net (code "201") (name "/VDAC_RESERVED0") (class "Default")
      (node (ref "P28") (pin "7") (pinfunction "7_7") (pintype "passive"))
      (node (ref "U16") (pin "2") (pinfunction "VOUTD_2") (pintype "output"))
    )
    (net (code "202") (name "/VDAC_RESERVED1") (class "Default")
      (node (ref "P70") (pin "7") (pinfunction "7_7") (pintype "passive"))
      (node (ref "U43") (pin "2") (pinfunction "VOUTD_2") (pintype "output"))
    )
    (net (code "203") (name "/VDD_ADC_3V") (class "Default")
      (node (ref "J20") (pin "1") (pinfunction "1_1") (pintype "passive"))
      (node (ref "J30") (pin "32") (pinfunction "32_32") (pintype "passive"))
      (node (ref "J32") (pin "32") (pinfunction "32_32") (pintype "passive"))
      (node (ref "P34") (pin "1") (pinfunction "1_1") (pintype "passive"))
    )
    (net (code "204") (name "/VDD_AFE_3V") (class "Default")
      (node (ref "J25") (pin "1") (pinfunction "1_1") (pintype "passive"))
      (node (ref "J30") (pin "34") (pinfunction "34_34") (pintype "passive"))
      (node (ref "J32") (pin "34") (pinfunction "34_34") (pintype "passive"))
      (node (ref "P37") (pin "1") (pinfunction "1_1") (pintype "passive"))
    )
    (net (code "205") (name "/VDD_DIG_3V") (class "Default")
      (node (ref "J15") (pin "1") (pinfunction "1_1") (pintype "passive"))
      (node (ref "J30") (pin "18") (pinfunction "18_18") (pintype "passive"))
      (node (ref "J32") (pin "18") (pinfunction "18_18") (pintype "passive"))
      (node (ref "P26") (pin "1") (pinfunction "1_1") (pintype "passive"))
    )
    (net (code "206") (name "/VDD_DIG_6V") (class "Default")
      (node (ref "J13") (pin "1") (pinfunction "1_1") (pintype "passive"))
      (node (ref "J30") (pin "22") (pinfunction "22_22") (pintype "passive"))
      (node (ref "J30") (pin "27") (pinfunction "27_27") (pintype "passive"))
      (node (ref "J32") (pin "22") (pinfunction "22_22") (pintype "passive"))
      (node (ref "J32") (pin "27") (pinfunction "27_27") (pintype "passive"))
      (node (ref "P23") (pin "1") (pinfunction "1_1") (pintype "passive"))
    )
    (net (code "207") (name "/VDD_IO_3P3V") (class "Default")
      (node (ref "J14") (pin "1") (pinfunction "1_1") (pintype "passive"))
      (node (ref "J30") (pin "31") (pinfunction "31_31") (pintype "passive"))
      (node (ref "J32") (pin "31") (pinfunction "31_31") (pintype "passive"))
      (node (ref "P24") (pin "1") (pinfunction "1_1") (pintype "passive"))
    )
    (net (code "208") (name "/VDD_TDIG_3V") (class "Default")
      (node (ref "J18") (pin "1") (pinfunction "1_1") (pintype "passive"))
      (node (ref "J30") (pin "26") (pinfunction "26_26") (pintype "passive"))
      (node (ref "J32") (pin "26") (pinfunction "26_26") (pintype "passive"))
      (node (ref "P29") (pin "1") (pinfunction "1_1") (pintype "passive"))
    )
    (net (code "209") (name "/VG") (class "Default")
      (node (ref "J28") (pin "1") (pinfunction "1_1") (pintype "passive"))
      (node (ref "J33") (pin "68") (pinfunction "68_68") (pintype "passive"))
      (node (ref "P45") (pin "1") (pinfunction "1_1") (pintype "passive"))
    )
    (net (code "210") (name "/VOCM_IN") (class "Default")
      (node (ref "C115") (pin "1") (pinfunction "1_1") (pintype "passive"))
      (node (ref "C3") (pin "1") (pinfunction "1_1") (pintype "passive"))
      (node (ref "J8") (pin "2") (pinfunction "2_2") (pintype "passive"))
      (node (ref "P5") (pin "3") (pinfunction "3_3") (pintype "passive"))
      (node (ref "P76") (pin "3") (pinfunction "3_3") (pintype "passive"))
      (node (ref "U3") (pin "2") (pinfunction "VOCM_2") (pintype "passive"))
      (node (ref "U55") (pin "2") (pinfunction "VOCM_2") (pintype "passive"))
    )
    (net (code "211") (name "/VREF_2P5V") (class "Default")
      (node (ref "P55") (pin "3") (pinfunction "3_3") (pintype "passive"))
      (node (ref "U19") (pin "2") (pinfunction "VOUT_2") (pintype "output"))
    )
    (net (code "212") (name "/VS") (class "Default")
      (node (ref "J29") (pin "1") (pinfunction "1_1") (pintype "passive"))
      (node (ref "J33") (pin "65") (pinfunction "65_65") (pintype "passive"))
      (node (ref "P48") (pin "1") (pinfunction "1_1") (pintype "passive"))
    )
    (net (code "213") (name "/VSS") (class "Default")
      (node (ref "J30") (pin "20") (pinfunction "20_20") (pintype "passive"))
      (node (ref "J30") (pin "29") (pinfunction "29_29") (pintype "passive"))
      (node (ref "J32") (pin "20") (pinfunction "20_20") (pintype "passive"))
      (node (ref "J32") (pin "29") (pinfunction "29_29") (pintype "passive"))
      (node (ref "R15") (pin "2") (pinfunction "2_2") (pintype "passive"))
    )
    (net (code "214") (name "AGND") (class "Default")
      (node (ref "J30") (pin "28") (pinfunction "28_28") (pintype "passive"))
      (node (ref "J32") (pin "28") (pinfunction "28_28") (pintype "passive"))
      (node (ref "P89") (pin "3") (pinfunction "3_3") (pintype "passive"))
      (node (ref "R16") (pin "2") (pinfunction "2_2") (pintype "passive"))
    )
    (net (code "215") (name "CHIPB_VBIAS_2P5V") (class "Default")
      (node (ref "C100") (pin "1") (pintype "passive"))
      (node (ref "C101") (pin "1") (pintype "passive"))
      (node (ref "C107") (pin "1") (pintype "passive"))
      (node (ref "C108") (pin "1") (pintype "passive"))
      (node (ref "C112") (pin "1") (pintype "passive"))
      (node (ref "C113") (pin "1") (pintype "passive"))
      (node (ref "C87") (pin "1") (pintype "passive"))
      (node (ref "C92") (pin "1") (pintype "passive"))
      (node (ref "C95") (pin "1") (pintype "passive"))
      (node (ref "C96") (pin "1") (pintype "passive"))
      (node (ref "P71") (pin "2") (pinfunction "2_2") (pintype "passive"))
      (node (ref "R30") (pin "1") (pinfunction "1_1") (pintype "passive"))
      (node (ref "R31") (pin "1") (pinfunction "1_1") (pintype "passive"))
      (node (ref "R33") (pin "1") (pinfunction "1_1") (pintype "passive"))
      (node (ref "R34") (pin "1") (pinfunction "1_1") (pintype "passive"))
      (node (ref "U43") (pin "7") (pinfunction "VREFH_7") (pintype "input"))
      (node (ref "U45") (pin "7") (pinfunction "VREFH_7") (pintype "input"))
    )
    (net (code "216") (name "CHIPB_VDD_2P5V") (class "Default")
      (node (ref "C104") (pin "1") (pinfunction "1_1") (pintype "passive"))
      (node (ref "P71") (pin "1") (pinfunction "1_1") (pintype "passive"))
      (node (ref "U50") (pin "4") (pinfunction "Vout_4") (pintype "output"))
    )
    (net (code "217") (name "GND") (class "Default")
      (node (ref "C1") (pin "2") (pintype "passive"))
      (node (ref "C10") (pin "2") (pintype "passive"))
      (node (ref "C100") (pin "2") (pintype "passive"))
      (node (ref "C101") (pin "2") (pintype "passive"))
      (node (ref "C103") (pin "2") (pinfunction "2_2") (pintype "passive"))
      (node (ref "C104") (pin "2") (pinfunction "2_2") (pintype "passive"))
      (node (ref "C105") (pin "2") (pintype "passive"))
      (node (ref "C106") (pin "2") (pintype "passive"))
      (node (ref "C107") (pin "2") (pintype "passive"))
      (node (ref "C108") (pin "2") (pintype "passive"))
      (node (ref "C11") (pin "2") (pintype "passive"))
      (node (ref "C110") (pin "2") (pintype "passive"))
      (node (ref "C111") (pin "2") (pintype "passive"))
      (node (ref "C112") (pin "2") (pintype "passive"))
      (node (ref "C113") (pin "2") (pintype "passive"))
      (node (ref "C115") (pin "2") (pinfunction "2_2") (pintype "passive"))
      (node (ref "C118") (pin "2") (pintype "passive"))
      (node (ref "C119") (pin "2") (pintype "passive"))
      (node (ref "C12") (pin "2") (pintype "passive"))
      (node (ref "C120") (pin "2") (pinfunction "2_2") (pintype "passive"))
      (node (ref "C122") (pin "2") (pintype "passive"))
      (node (ref "C123") (pin "2") (pintype "passive"))
      (node (ref "C126") (pin "2") (pintype "passive"))
      (node (ref "C127") (pin "2") (pintype "passive"))
      (node (ref "C128") (pin "2") (pintype "passive"))
      (node (ref "C129") (pin "2") (pintype "passive"))
      (node (ref "C131") (pin "2") (pintype "passive"))
      (node (ref "C132") (pin "2") (pintype "passive"))
      (node (ref "C14") (pin "2") (pintype "passive"))
      (node (ref "C15") (pin "2") (pintype "passive"))
      (node (ref "C18") (pin "2") (pintype "passive"))
      (node (ref "C19") (pin "2") (pintype "passive"))
      (node (ref "C2") (pin "2") (pintype "passive"))
      (node (ref "C20") (pin "2") (pintype "passive"))
      (node (ref "C21") (pin "2") (pintype "passive"))
      (node (ref "C23") (pin "2") (pintype "passive"))
      (node (ref "C24") (pin "2") (pintype "passive"))
      (node (ref "C25") (pin "2") (pintype "passive"))
      (node (ref "C26") (pin "2") (pintype "passive"))
      (node (ref "C27") (pin "2") (pintype "passive"))
      (node (ref "C28") (pin "2") (pintype "passive"))
      (node (ref "C29") (pin "2") (pintype "passive"))
      (node (ref "C3") (pin "2") (pinfunction "2_2") (pintype "passive"))
      (node (ref "C30") (pin "2") (pintype "passive"))
      (node (ref "C31") (pin "2") (pintype "passive"))
      (node (ref "C32") (pin "2") (pintype "passive"))
      (node (ref "C33") (pin "2") (pintype "passive"))
      (node (ref "C34") (pin "2") (pintype "passive"))
      (node (ref "C35") (pin "2") (pintype "passive"))
      (node (ref "C36") (pin "2") (pintype "passive"))
      (node (ref "C37") (pin "2") (pintype "passive"))
      (node (ref "C38") (pin "2") (pintype "passive"))
      (node (ref "C39") (pin "2") (pintype "passive"))
      (node (ref "C40") (pin "2") (pintype "passive"))
      (node (ref "C41") (pin "2") (pintype "passive"))
      (node (ref "C42") (pin "2") (pintype "passive"))
      (node (ref "C43") (pin "2") (pintype "passive"))
      (node (ref "C44") (pin "2") (pintype "passive"))
      (node (ref "C45") (pin "2") (pintype "passive"))
      (node (ref "C46") (pin "2") (pintype "passive"))
      (node (ref "C48") (pin "2") (pintype "passive"))
      (node (ref "C49") (pin "2") (pintype "passive"))
      (node (ref "C50") (pin "2") (pintype "passive"))
      (node (ref "C51") (pin "2") (pintype "passive"))
      (node (ref "C53") (pin "2") (pinfunction "2_2") (pintype "passive"))
      (node (ref "C54") (pin "2") (pinfunction "2_2") (pintype "passive"))
      (node (ref "C55") (pin "2") (pintype "passive"))
      (node (ref "C56") (pin "2") (pintype "passive"))
      (node (ref "C57") (pin "2") (pintype "passive"))
      (node (ref "C58") (pin "2") (pintype "passive"))
      (node (ref "C6") (pin "2") (pintype "passive"))
      (node (ref "C60") (pin "2") (pintype "passive"))
      (node (ref "C61") (pin "2") (pintype "passive"))
      (node (ref "C62") (pin "2") (pintype "passive"))
      (node (ref "C63") (pin "2") (pintype "passive"))
      (node (ref "C7") (pin "2") (pintype "passive"))
      (node (ref "C8") (pin "2") (pinfunction "2_2") (pintype "passive"))
      (node (ref "C85") (pin "2") (pintype "passive"))
      (node (ref "C86") (pin "2") (pintype "passive"))
      (node (ref "C87") (pin "2") (pintype "passive"))
      (node (ref "C88") (pin "2") (pintype "passive"))
      (node (ref "C89") (pin "2") (pintype "passive"))
      (node (ref "C9") (pin "2") (pintype "passive"))
      (node (ref "C90") (pin "2") (pintype "passive"))
      (node (ref "C91") (pin "2") (pintype "passive"))
      (node (ref "C92") (pin "2") (pintype "passive"))
      (node (ref "C93") (pin "2") (pintype "passive"))
      (node (ref "C94") (pin "2") (pintype "passive"))
      (node (ref "C95") (pin "2") (pintype "passive"))
      (node (ref "C96") (pin "2") (pintype "passive"))
      (node (ref "C98") (pin "2") (pintype "passive"))
      (node (ref "C99") (pin "2") (pintype "passive"))
      (node (ref "J1") (pin "1") (pinfunction "1_1") (pintype "passive"))
      (node (ref "J12") (pin "1") (pinfunction "1_1") (pintype "passive"))
      (node (ref "J17") (pin "1") (pinfunction "SHIELD_1") (pintype "passive"))
      (node (ref "J19") (pin "1") (pinfunction "SHIELD_1") (pintype "passive"))
      (node (ref "J2") (pin "1") (pinfunction "1_1") (pintype "passive"))
      (node (ref "J21") (pin "1") (pinfunction "SHIELD_1") (pintype "passive"))
      (node (ref "J22") (pin "2") (pinfunction "2_2") (pintype "passive"))
      (node (ref "J22") (pin "3") (pinfunction "3_3") (pintype "passive"))
      (node (ref "J22") (pin "4") (pinfunction "4_4") (pintype "passive"))
      (node (ref "J22") (pin "5") (pinfunction "5_5") (pintype "passive"))
      (node (ref "J24") (pin "1") (pinfunction "SHIELD_1") (pintype "passive"))
      (node (ref "J27") (pin "2") (pinfunction "2_2") (pintype "passive"))
      (node (ref "J27") (pin "3") (pinfunction "3_3") (pintype "passive"))
      (node (ref "J27") (pin "4") (pinfunction "4_4") (pintype "passive"))
      (node (ref "J27") (pin "5") (pinfunction "5_5") (pintype "passive"))
      (node (ref "J3") (pin "1") (pinfunction "1_1") (pintype "passive"))
      (node (ref "J30") (pin "36") (pinfunction "36_36") (pintype "passive"))
      (node (ref "J30") (pin "38") (pinfunction "38_38") (pintype "passive"))
      (node (ref "J30") (pin "40") (pinfunction "40_40") (pintype "passive"))
      (node (ref "J30") (pin "S1") (pinfunction "SHIELD_S1") (pintype "passive"))
      (node (ref "J30") (pin "S2") (pinfunction "SHIELD_S2") (pintype "passive"))
      (node (ref "J32") (pin "36") (pinfunction "36_36") (pintype "passive"))
      (node (ref "J32") (pin "38") (pinfunction "38_38") (pintype "passive"))
      (node (ref "J32") (pin "40") (pinfunction "40_40") (pintype "passive"))
      (node (ref "J32") (pin "S1") (pinfunction "SHIELD_S1") (pintype "passive"))
      (node (ref "J32") (pin "S2") (pinfunction "SHIELD_S2") (pintype "passive"))
      (node (ref "J33") (pin "73") (pinfunction "73_73") (pintype "passive"))
      (node (ref "J33") (pin "74") (pinfunction "74_74") (pintype "passive"))
      (node (ref "J33") (pin "75") (pinfunction "75_75") (pintype "passive"))
      (node (ref "J33") (pin "76") (pinfunction "76_76") (pintype "passive"))
      (node (ref "J33") (pin "77") (pinfunction "77_77") (pintype "passive"))
      (node (ref "J33") (pin "78") (pinfunction "78_78") (pintype "passive"))
      (node (ref "J33") (pin "79") (pinfunction "79_79") (pintype "passive"))
      (node (ref "J33") (pin "80") (pinfunction "80_80") (pintype "passive"))
      (node (ref "J33") (pin "81") (pinfunction "81_81") (pintype "passive"))
      (node (ref "J33") (pin "82") (pinfunction "82_82") (pintype "passive"))
      (node (ref "J33") (pin "83") (pinfunction "83_83") (pintype "passive"))
      (node (ref "J33") (pin "84") (pinfunction "84_84") (pintype "passive"))
      (node (ref "J33") (pin "85") (pinfunction "85_85") (pintype "passive"))
      (node (ref "J33") (pin "86") (pinfunction "86_86") (pintype "passive"))
      (node (ref "J33") (pin "87") (pinfunction "87_87") (pintype "passive"))
      (node (ref "J33") (pin "88") (pinfunction "88_88") (pintype "passive"))
      (node (ref "J33") (pin "89") (pinfunction "89_89") (pintype "passive"))
      (node (ref "J33") (pin "90") (pinfunction "90_90") (pintype "passive"))
      (node (ref "J33") (pin "91") (pinfunction "91_91") (pintype "passive"))
      (node (ref "J33") (pin "92") (pinfunction "92_92") (pintype "passive"))
      (node (ref "J33") (pin "93") (pinfunction "93_93") (pintype "passive"))
      (node (ref "J33") (pin "94") (pinfunction "94_94") (pintype "passive"))
      (node (ref "J33") (pin "95") (pinfunction "95_95") (pintype "passive"))
      (node (ref "J33") (pin "96") (pinfunction "96_96") (pintype "passive"))
      (node (ref "J34") (pin "C01") (pinfunction "C01_C01") (pintype "passive"))
      (node (ref "J34") (pin "C04") (pinfunction "C04_C04") (pintype "passive"))
      (node (ref "J34") (pin "C05") (pinfunction "C05_C05") (pintype "passive"))
      (node (ref "J34") (pin "C08") (pinfunction "C08_C08") (pintype "passive"))
      (node (ref "J34") (pin "C09") (pinfunction "C09_C09") (pintype "passive"))
      (node (ref "J34") (pin "C12") (pinfunction "C12_C12") (pintype "passive"))
      (node (ref "J34") (pin "C13") (pinfunction "C13_C13") (pintype "passive"))
      (node (ref "J34") (pin "C16") (pinfunction "C16_C16") (pintype "passive"))
      (node (ref "J34") (pin "C17") (pinfunction "C17_C17") (pintype "passive"))
      (node (ref "J34") (pin "C20") (pinfunction "C20_C20") (pintype "passive"))
      (node (ref "J34") (pin "C21") (pinfunction "C21_C21") (pintype "passive"))
      (node (ref "J34") (pin "C24") (pinfunction "C24_C24") (pintype "passive"))
      (node (ref "J34") (pin "C25") (pinfunction "C25_C25") (pintype "passive"))
      (node (ref "J34") (pin "C28") (pinfunction "C28_C28") (pintype "passive"))
      (node (ref "J34") (pin "C29") (pinfunction "C29_C29") (pintype "passive"))
      (node (ref "J34") (pin "C32") (pinfunction "C32_C32") (pintype "passive"))
      (node (ref "J34") (pin "C33") (pinfunction "C33_C33") (pintype "passive"))
      (node (ref "J34") (pin "C36") (pinfunction "C36_C36") (pintype "passive"))
      (node (ref "J34") (pin "C38") (pinfunction "C38_C38") (pintype "passive"))
      (node (ref "J34") (pin "C40") (pinfunction "C40_C40") (pintype "passive"))
      (node (ref "J34") (pin "D02") (pinfunction "D02_D02") (pintype "passive"))
      (node (ref "J34") (pin "D03") (pinfunction "D03_D03") (pintype "passive"))
      (node (ref "J34") (pin "D06") (pinfunction "D06_D06") (pintype "passive"))
      (node (ref "J34") (pin "D07") (pinfunction "D07_D07") (pintype "passive"))
      (node (ref "J34") (pin "D10") (pinfunction "D10_D10") (pintype "passive"))
      (node (ref "J34") (pin "D13") (pinfunction "D13_D13") (pintype "passive"))
      (node (ref "J34") (pin "D16") (pinfunction "D16_D16") (pintype "passive"))
      (node (ref "J34") (pin "D19") (pinfunction "D19_D19") (pintype "passive"))
      (node (ref "J34") (pin "D22") (pinfunction "D22_D22") (pintype "passive"))
      (node (ref "J34") (pin "D25") (pinfunction "D25_D25") (pintype "passive"))
      (node (ref "J34") (pin "D28") (pinfunction "D28_D28") (pintype "passive"))
      (node (ref "J34") (pin "D37") (pinfunction "D37_D37") (pintype "passive"))
      (node (ref "J34") (pin "D39") (pinfunction "D39_D39") (pintype "passive"))
      (node (ref "J34") (pin "G01") (pinfunction "G01_G01") (pintype "passive"))
      (node (ref "J34") (pin "G04") (pinfunction "G04_G04") (pintype "passive"))
      (node (ref "J34") (pin "G05") (pinfunction "G05_G05") (pintype "passive"))
      (node (ref "J34") (pin "G08") (pinfunction "G08_G08") (pintype "passive"))
      (node (ref "J34") (pin "G11") (pinfunction "G11_G11") (pintype "passive"))
      (node (ref "J34") (pin "G14") (pinfunction "G14_G14") (pintype "passive"))
      (node (ref "J34") (pin "G17") (pinfunction "G17_G17") (pintype "passive"))
      (node (ref "J34") (pin "G20") (pinfunction "G20_G20") (pintype "passive"))
      (node (ref "J34") (pin "G23") (pinfunction "G23_G23") (pintype "passive"))
      (node (ref "J34") (pin "G26") (pinfunction "G26_G26") (pintype "passive"))
      (node (ref "J34") (pin "G29") (pinfunction "G29_G29") (pintype "passive"))
      (node (ref "J34") (pin "G32") (pinfunction "G32_G32") (pintype "passive"))
      (node (ref "J34") (pin "G35") (pinfunction "G35_G35") (pintype "passive"))
      (node (ref "J34") (pin "G38") (pinfunction "G38_G38") (pintype "passive"))
      (node (ref "J34") (pin "G40") (pinfunction "G40_G40") (pintype "passive"))
      (node (ref "J34") (pin "H03") (pinfunction "H03_H03") (pintype "passive"))
      (node (ref "J34") (pin "H06") (pinfunction "H06_H06") (pintype "passive"))
      (node (ref "J34") (pin "H09") (pinfunction "H09_H09") (pintype "passive"))
      (node (ref "J34") (pin "H12") (pinfunction "H12_H12") (pintype "passive"))
      (node (ref "J34") (pin "H15") (pinfunction "H15_H15") (pintype "passive"))
      (node (ref "J34") (pin "H18") (pinfunction "H18_H18") (pintype "passive"))
      (node (ref "J34") (pin "H21") (pinfunction "H21_H21") (pintype "passive"))
      (node (ref "J34") (pin "H24") (pinfunction "H24_H24") (pintype "passive"))
      (node (ref "J34") (pin "H27") (pinfunction "H27_H27") (pintype "passive"))
      (node (ref "J34") (pin "H30") (pinfunction "H30_H30") (pintype "passive"))
      (node (ref "J34") (pin "H33") (pinfunction "H33_H33") (pintype "passive"))
      (node (ref "J34") (pin "H36") (pinfunction "H36_H36") (pintype "passive"))
      (node (ref "J34") (pin "H39") (pinfunction "H39_H39") (pintype "passive"))
      (node (ref "J36") (pin "1") (pinfunction "1_1") (pintype "passive"))
      (node (ref "J37") (pin "1") (pinfunction "1_1") (pintype "passive"))
      (node (ref "J38") (pin "1") (pinfunction "1_1") (pintype "passive"))
      (node (ref "J39") (pin "1") (pinfunction "1_1") (pintype "passive"))
      (node (ref "J4") (pin "1") (pinfunction "1_1") (pintype "passive"))
      (node (ref "J40") (pin "1") (pinfunction "1_1") (pintype "passive"))
      (node (ref "J41") (pin "1") (pinfunction "1_1") (pintype "passive"))
      (node (ref "J42") (pin "1") (pinfunction "1_1") (pintype "passive"))
      (node (ref "J5") (pin "1") (pinfunction "1_1") (pintype "passive"))
      (node (ref "J6") (pin "1") (pinfunction "1_1") (pintype "passive"))
      (node (ref "J7") (pin "1") (pinfunction "1_1") (pintype "passive"))
      (node (ref "J8") (pin "1") (pinfunction "1_1") (pintype "passive"))
      (node (ref "P11") (pin "2") (pinfunction "2_2") (pintype "passive"))
      (node (ref "P13") (pin "2") (pinfunction "2_2") (pintype "passive"))
      (node (ref "P23") (pin "2") (pinfunction "2_2") (pintype "passive"))
      (node (ref "P24") (pin "2") (pinfunction "2_2") (pintype "passive"))
      (node (ref "P26") (pin "2") (pinfunction "2_2") (pintype "passive"))
      (node (ref "P29") (pin "2") (pinfunction "2_2") (pintype "passive"))
      (node (ref "P3") (pin "2") (pinfunction "2_2") (pintype "passive"))
      (node (ref "P34") (pin "2") (pinfunction "2_2") (pintype "passive"))
      (node (ref "P37") (pin "2") (pinfunction "2_2") (pintype "passive"))
      (node (ref "P42") (pin "2") (pinfunction "2_2") (pintype "passive"))
      (node (ref "P45") (pin "2") (pinfunction "2_2") (pintype "passive"))
      (node (ref "P48") (pin "2") (pinfunction "2_2") (pintype "passive"))
      (node (ref "P6") (pin "1") (pinfunction "1_1") (pintype "passive"))
      (node (ref "P7") (pin "1") (pinfunction "1_1") (pintype "passive"))
      (node (ref "P77") (pin "1") (pinfunction "1_1") (pintype "passive"))
      (node (ref "P78") (pin "1") (pinfunction "1_1") (pintype "passive"))
      (node (ref "P79") (pin "1") (pinfunction "1_1") (pintype "passive"))
      (node (ref "P8") (pin "1") (pinfunction "1_1") (pintype "passive"))
      (node (ref "P80") (pin "2") (pinfunction "2_2") (pintype "passive"))
      (node (ref "P81") (pin "2") (pinfunction "2_2") (pintype "passive"))
      (node (ref "P82") (pin "2") (pinfunction "2_2") (pintype "passive"))
      (node (ref "P88") (pin "2") (pinfunction "2_2") (pintype "passive"))
      (node (ref "R15") (pin "1") (pinfunction "1_1") (pintype "passive"))
      (node (ref "R16") (pin "1") (pinfunction "1_1") (pintype "passive"))
      (node (ref "R17") (pin "1") (pinfunction "1_1") (pintype "passive"))
      (node (ref "R18") (pin "1") (pinfunction "1_1") (pintype "passive"))
      (node (ref "R20") (pin "1") (pinfunction "1_1") (pintype "passive"))
      (node (ref "R85") (pin "2") (pinfunction "2_2") (pintype "passive"))
      (node (ref "U1") (pin "5") (pinfunction "GND_5") (pintype "power_in"))
      (node (ref "U1") (pin "7") (pinfunction "GND_7") (pintype "power_in"))
      (node (ref "U10") (pin "5") (pinfunction "GND_5") (pintype "power_in"))
      (node (ref "U10") (pin "7") (pinfunction "GND_7") (pintype "power_in"))
      (node (ref "U11") (pin "5") (pinfunction "GND_5") (pintype "power_in"))
      (node (ref "U11") (pin "7") (pinfunction "GND_7") (pintype "power_in"))
      (node (ref "U12") (pin "5") (pinfunction "GND_5") (pintype "power_in"))
      (node (ref "U12") (pin "7") (pinfunction "GND_7") (pintype "power_in"))
      (node (ref "U13") (pin "5") (pinfunction "GND_5") (pintype "power_in"))
      (node (ref "U13") (pin "7") (pinfunction "GND_7") (pintype "power_in"))
      (node (ref "U14") (pin "5") (pinfunction "GND_5") (pintype "power_in"))
      (node (ref "U14") (pin "7") (pinfunction "GND_7") (pintype "power_in"))
      (node (ref "U15") (pin "5") (pinfunction "GND_5") (pintype "power_in"))
      (node (ref "U15") (pin "7") (pinfunction "GND_7") (pintype "power_in"))
      (node (ref "U16") (pin "11") (pinfunction "GND_11") (pintype "power_in"))
      (node (ref "U16") (pin "20") (pinfunction "RESETSEL_20") (pintype "passive"))
      (node (ref "U17") (pin "5") (pinfunction "GND_5") (pintype "power_in"))
      (node (ref "U17") (pin "7") (pinfunction "GND_7") (pintype "power_in"))
      (node (ref "U18") (pin "5") (pinfunction "GND_5") (pintype "power_in"))
      (node (ref "U18") (pin "7") (pinfunction "GND_7") (pintype "power_in"))
      (node (ref "U2") (pin "5") (pinfunction "GND_5") (pintype "power_in"))
      (node (ref "U2") (pin "7") (pinfunction "GND_7") (pintype "power_in"))
      (node (ref "U20") (pin "11") (pinfunction "GND_11") (pintype "power_in"))
      (node (ref "U20") (pin "20") (pinfunction "RESETSEL_20") (pintype "passive"))
      (node (ref "U21") (pin "5") (pinfunction "GND_5") (pintype "power_in"))
      (node (ref "U21") (pin "7") (pinfunction "GND_7") (pintype "power_in"))
      (node (ref "U22") (pin "5") (pinfunction "GND_5") (pintype "power_in"))
      (node (ref "U22") (pin "7") (pinfunction "GND_7") (pintype "power_in"))
      (node (ref "U26") (pin "GND1") (pinfunction "GND_GND1") (pintype "power_in"))
      (node (ref "U26") (pin "GND2") (pinfunction "GND_GND2") (pintype "power_in"))
      (node (ref "U26") (pin "GND3") (pinfunction "GND_GND3") (pintype "power_in"))
      (node (ref "U26") (pin "GND4") (pinfunction "GND_GND4") (pintype "power_in"))
      (node (ref "U26") (pin "GND5") (pinfunction "GND_GND5") (pintype "power_in"))
      (node (ref "U29") (pin "3") (pinfunction "GND_3") (pintype "passive"))
      (node (ref "U29") (pin "5") (pinfunction "~ERROR_5") (pintype "passive"))
      (node (ref "U29") (pin "6") (pinfunction "16_6") (pintype "passive"))
      (node (ref "U4") (pin "5") (pinfunction "GND_5") (pintype "power_in"))
      (node (ref "U4") (pin "7") (pinfunction "GND_7") (pintype "power_in"))
      (node (ref "U43") (pin "11") (pinfunction "GND_11") (pintype "power_in"))
      (node (ref "U43") (pin "20") (pinfunction "RESETSEL_20") (pintype "passive"))
      (node (ref "U45") (pin "11") (pinfunction "GND_11") (pintype "power_in"))
      (node (ref "U45") (pin "20") (pinfunction "RESETSEL_20") (pintype "passive"))
      (node (ref "U5") (pin "5") (pinfunction "GND_5") (pintype "power_in"))
      (node (ref "U5") (pin "7") (pinfunction "GND_7") (pintype "power_in"))
      (node (ref "U50") (pin "3") (pinfunction "GND_3") (pintype "passive"))
      (node (ref "U50") (pin "5") (pinfunction "~ERROR_5") (pintype "passive"))
      (node (ref "U50") (pin "6") (pinfunction "16_6") (pintype "passive"))
      (node (ref "U56") (pin "16") (pinfunction "DGND_16") (pintype "power_in"))
      (node (ref "U57") (pin "16") (pinfunction "DGND_16") (pintype "power_in"))
      (node (ref "U6") (pin "16") (pinfunction "DGND_16") (pintype "power_in"))
      (node (ref "U7") (pin "16") (pinfunction "DGND_16") (pintype "power_in"))
      (node (ref "U8") (pin "5") (pinfunction "GND_5") (pintype "power_in"))
      (node (ref "U8") (pin "7") (pinfunction "GND_7") (pintype "power_in"))
      (node (ref "U9") (pin "5") (pinfunction "GND_5") (pintype "power_in"))
      (node (ref "U9") (pin "7") (pinfunction "GND_7") (pintype "power_in"))
    )
    (net (code "218") (name "Net-(P5-Pad2)") (class "Default")
      (node (ref "P5") (pin "2") (pinfunction "2_2") (pintype "passive"))
      (node (ref "R4") (pin "1") (pinfunction "1_1") (pintype "passive"))
    )
    (net (code "219") (name "Net-(P76-Pad2)") (class "Default")
      (node (ref "P76") (pin "2") (pinfunction "2_2") (pintype "passive"))
      (node (ref "R37") (pin "1") (pinfunction "1_1") (pintype "passive"))
    )
    (net (code "220") (name "Net-(R85-Pad1)") (class "Default")
      (node (ref "R85") (pin "1") (pinfunction "1_1") (pintype "passive"))
      (node (ref "VDD_1") (pin "K") (pinfunction "K_K") (pintype "passive"))
    )
    (net (code "221") (name "Net-(U2-CP)") (class "Default")
      (node (ref "R3") (pin "1") (pinfunction "1_1") (pintype "passive"))
      (node (ref "U2") (pin "2") (pinfunction "CP_2") (pintype "power_in"))
    )
    (net (code "222") (name "Net-(U3-VIN+)") (class "Default")
      (node (ref "C4") (pin "1") (pinfunction "1_1") (pintype "passive"))
      (node (ref "R4") (pin "2") (pinfunction "2_2") (pintype "passive"))
      (node (ref "R7") (pin "1") (pinfunction "1_1") (pintype "passive"))
      (node (ref "U3") (pin "8") (pinfunction "VIN+_8") (pintype "input"))
    )
    (net (code "223") (name "Net-(U3-VIN-)") (class "Default")
      (node (ref "C5") (pin "1") (pinfunction "1_1") (pintype "passive"))
      (node (ref "R5") (pin "1") (pinfunction "1_1") (pintype "passive"))
      (node (ref "R6") (pin "1") (pinfunction "1_1") (pintype "passive"))
      (node (ref "U3") (pin "1") (pinfunction "VIN-_1") (pintype "input"))
    )
    (net (code "224") (name "Net-(U3-VOUT+)") (class "Default")
      (node (ref "C5") (pin "2") (pinfunction "2_2") (pintype "passive"))
      (node (ref "R2") (pin "1") (pinfunction "1_1") (pintype "passive"))
      (node (ref "R6") (pin "2") (pinfunction "2_2") (pintype "passive"))
      (node (ref "U3") (pin "4") (pinfunction "VOUT+_4") (pintype "output"))
    )
    (net (code "225") (name "Net-(U3-VOUT-)") (class "Default")
      (node (ref "C4") (pin "2") (pinfunction "2_2") (pintype "passive"))
      (node (ref "R1") (pin "1") (pinfunction "1_1") (pintype "passive"))
      (node (ref "R7") (pin "2") (pinfunction "2_2") (pintype "passive"))
      (node (ref "U3") (pin "5") (pinfunction "VOUT-_5") (pintype "output"))
    )
    (net (code "226") (name "Net-(U6-FDA_IN+)") (class "Default")
      (node (ref "C13") (pin "2") (pinfunction "2_2") (pintype "passive"))
      (node (ref "U6") (pin "12") (pinfunction "FDA_IN+_12") (pintype "input"))
    )
    (net (code "227") (name "Net-(U6-FDA_IN-)") (class "Default")
      (node (ref "C16") (pin "1") (pinfunction "1_1") (pintype "passive"))
      (node (ref "U6") (pin "9") (pinfunction "FDA_IN-_9") (pintype "input"))
    )
    (net (code "228") (name "Net-(U6-IN+)") (class "Default")
      (node (ref "R9") (pin "1") (pinfunction "1_1") (pintype "passive"))
      (node (ref "U6") (pin "2") (pinfunction "IN+_2") (pintype "input"))
    )
    (net (code "229") (name "Net-(U6-IN-)") (class "Default")
      (node (ref "R10") (pin "1") (pinfunction "1_1") (pintype "passive"))
      (node (ref "U6") (pin "3") (pinfunction "IN-_3") (pintype "input"))
    )
    (net (code "230") (name "Net-(U6-VOCM)") (class "Default")
      (node (ref "P18") (pin "2") (pinfunction "2_2") (pintype "passive"))
      (node (ref "U6") (pin "13") (pinfunction "VOCM_13") (pintype "input"))
      (node (ref "U7") (pin "13") (pinfunction "VOCM_13") (pintype "input"))
    )
    (net (code "231") (name "Net-(U7-FDA_IN+)") (class "Default")
      (node (ref "C17") (pin "2") (pinfunction "2_2") (pintype "passive"))
      (node (ref "U7") (pin "12") (pinfunction "FDA_IN+_12") (pintype "input"))
    )
    (net (code "232") (name "Net-(U7-FDA_IN-)") (class "Default")
      (node (ref "C22") (pin "1") (pinfunction "1_1") (pintype "passive"))
      (node (ref "U7") (pin "9") (pinfunction "FDA_IN-_9") (pintype "input"))
    )
    (net (code "233") (name "Net-(U7-IN+)") (class "Default")
      (node (ref "R12") (pin "1") (pinfunction "1_1") (pintype "passive"))
      (node (ref "U7") (pin "2") (pinfunction "IN+_2") (pintype "input"))
    )
    (net (code "234") (name "Net-(U7-IN-)") (class "Default")
      (node (ref "R13") (pin "1") (pinfunction "1_1") (pintype "passive"))
      (node (ref "U7") (pin "3") (pinfunction "IN-_3") (pintype "input"))
    )
    (net (code "235") (name "Net-(U8-CP)") (class "Default")
      (node (ref "R11") (pin "1") (pinfunction "1_1") (pintype "passive"))
      (node (ref "U8") (pin "2") (pinfunction "CP_2") (pintype "power_in"))
    )
    (net (code "236") (name "Net-(U9-CP)") (class "Default")
      (node (ref "R14") (pin "1") (pinfunction "1_1") (pintype "passive"))
      (node (ref "U9") (pin "2") (pinfunction "CP_2") (pintype "power_in"))
    )
    (net (code "237") (name "Net-(U12-CP)") (class "Default")
      (node (ref "R19") (pin "1") (pinfunction "1_1") (pintype "passive"))
      (node (ref "U12") (pin "2") (pinfunction "CP_2") (pintype "power_in"))
    )
    (net (code "238") (name "Net-(U13-CP)") (class "Default")
      (node (ref "R21") (pin "1") (pinfunction "1_1") (pintype "passive"))
      (node (ref "U13") (pin "2") (pinfunction "CP_2") (pintype "power_in"))
    )
    (net (code "239") (name "Net-(U15-CP)") (class "Default")
      (node (ref "R22") (pin "1") (pinfunction "1_1") (pintype "passive"))
      (node (ref "U15") (pin "2") (pinfunction "CP_2") (pintype "power_in"))
    )
    (net (code "240") (name "Net-(U18-CP)") (class "Default")
      (node (ref "R23") (pin "1") (pinfunction "1_1") (pintype "passive"))
      (node (ref "U18") (pin "2") (pinfunction "CP_2") (pintype "power_in"))
    )
    (net (code "241") (name "Net-(U22-CP)") (class "Default")
      (node (ref "R24") (pin "1") (pinfunction "1_1") (pintype "passive"))
      (node (ref "U22") (pin "2") (pinfunction "CP_2") (pintype "power_in"))
    )
    (net (code "242") (name "Net-(U24-IN-)") (class "Default")
      (node (ref "C47") (pin "1") (pintype "passive"))
      (node (ref "R25") (pin "2") (pinfunction "2_2") (pintype "passive"))
      (node (ref "U24") (pin "4") (pinfunction "IN-_4") (pintype "input"))
      (node (ref "U25") (pin "2") (pinfunction "EMITTER_2") (pintype "passive"))
    )
    (net (code "243") (name "Net-(U24-OUT)") (class "Default")
      (node (ref "C47") (pin "2") (pintype "passive"))
      (node (ref "U24") (pin "1") (pinfunction "OUT_1") (pintype "output"))
      (node (ref "U25") (pin "1") (pinfunction "BASE_1") (pintype "passive"))
    )
    (net (code "244") (name "Net-(U27-IN-)") (class "Default")
      (node (ref "C52") (pin "1") (pintype "passive"))
      (node (ref "R26") (pin "2") (pinfunction "2_2") (pintype "passive"))
      (node (ref "U27") (pin "4") (pinfunction "IN-_4") (pintype "input"))
      (node (ref "U28") (pin "2") (pinfunction "EMITTER_2") (pintype "passive"))
    )
    (net (code "245") (name "Net-(U27-OUT)") (class "Default")
      (node (ref "C52") (pin "2") (pintype "passive"))
      (node (ref "U27") (pin "1") (pinfunction "OUT_1") (pintype "output"))
      (node (ref "U28") (pin "1") (pinfunction "BASE_1") (pintype "passive"))
    )
    (net (code "246") (name "Net-(U29-~SD)") (class "Default")
      (node (ref "R27") (pin "1") (pinfunction "1_1") (pintype "passive"))
      (node (ref "U29") (pin "1") (pinfunction "~SD_1") (pintype "passive"))
    )
    (net (code "247") (name "Net-(U30-IN-)") (class "Default")
      (node (ref "C59") (pin "1") (pintype "passive"))
      (node (ref "R28") (pin "2") (pinfunction "2_2") (pintype "passive"))
      (node (ref "U30") (pin "4") (pinfunction "IN-_4") (pintype "input"))
      (node (ref "U31") (pin "2") (pinfunction "EMITTER_2") (pintype "passive"))
    )
    (net (code "248") (name "Net-(U30-OUT)") (class "Default")
      (node (ref "C59") (pin "2") (pintype "passive"))
      (node (ref "U30") (pin "1") (pinfunction "OUT_1") (pintype "output"))
      (node (ref "U31") (pin "1") (pinfunction "BASE_1") (pintype "passive"))
    )
    (net (code "249") (name "Net-(U32-IN-)") (class "Default")
      (node (ref "C64") (pin "1") (pintype "passive"))
      (node (ref "R29") (pin "2") (pinfunction "2_2") (pintype "passive"))
      (node (ref "U32") (pin "4") (pinfunction "IN-_4") (pintype "input"))
      (node (ref "U33") (pin "2") (pinfunction "EMITTER_2") (pintype "passive"))
    )
    (net (code "250") (name "Net-(U32-OUT)") (class "Default")
      (node (ref "C64") (pin "2") (pintype "passive"))
      (node (ref "U32") (pin "1") (pinfunction "OUT_1") (pintype "output"))
      (node (ref "U33") (pin "1") (pinfunction "BASE_1") (pintype "passive"))
    )
    (net (code "251") (name "Net-(U46-IN-)") (class "Default")
      (node (ref "C97") (pin "1") (pintype "passive"))
      (node (ref "R30") (pin "2") (pinfunction "2_2") (pintype "passive"))
      (node (ref "U46") (pin "4") (pinfunction "IN-_4") (pintype "input"))
      (node (ref "U47") (pin "2") (pinfunction "EMITTER_2") (pintype "passive"))
    )
    (net (code "252") (name "Net-(U46-OUT)") (class "Default")
      (node (ref "C97") (pin "2") (pintype "passive"))
      (node (ref "U46") (pin "1") (pinfunction "OUT_1") (pintype "output"))
      (node (ref "U47") (pin "1") (pinfunction "BASE_1") (pintype "passive"))
    )
    (net (code "253") (name "Net-(U48-IN-)") (class "Default")
      (node (ref "C102") (pin "1") (pintype "passive"))
      (node (ref "R31") (pin "2") (pinfunction "2_2") (pintype "passive"))
      (node (ref "U48") (pin "4") (pinfunction "IN-_4") (pintype "input"))
      (node (ref "U49") (pin "2") (pinfunction "EMITTER_2") (pintype "passive"))
    )
    (net (code "254") (name "Net-(U48-OUT)") (class "Default")
      (node (ref "C102") (pin "2") (pintype "passive"))
      (node (ref "U48") (pin "1") (pinfunction "OUT_1") (pintype "output"))
      (node (ref "U49") (pin "1") (pinfunction "BASE_1") (pintype "passive"))
    )
    (net (code "255") (name "Net-(U50-~SD)") (class "Default")
      (node (ref "R32") (pin "1") (pinfunction "1_1") (pintype "passive"))
      (node (ref "U50") (pin "1") (pinfunction "~SD_1") (pintype "passive"))
    )
    (net (code "256") (name "Net-(U51-IN-)") (class "Default")
      (node (ref "C109") (pin "1") (pintype "passive"))
      (node (ref "R33") (pin "2") (pinfunction "2_2") (pintype "passive"))
      (node (ref "U51") (pin "4") (pinfunction "IN-_4") (pintype "input"))
      (node (ref "U52") (pin "2") (pinfunction "EMITTER_2") (pintype "passive"))
    )
    (net (code "257") (name "Net-(U51-OUT)") (class "Default")
      (node (ref "C109") (pin "2") (pintype "passive"))
      (node (ref "U51") (pin "1") (pinfunction "OUT_1") (pintype "output"))
      (node (ref "U52") (pin "1") (pinfunction "BASE_1") (pintype "passive"))
    )
    (net (code "258") (name "Net-(U53-IN-)") (class "Default")
      (node (ref "C114") (pin "1") (pintype "passive"))
      (node (ref "R34") (pin "2") (pinfunction "2_2") (pintype "passive"))
      (node (ref "U53") (pin "4") (pinfunction "IN-_4") (pintype "input"))
      (node (ref "U54") (pin "2") (pinfunction "EMITTER_2") (pintype "passive"))
    )
    (net (code "259") (name "Net-(U53-OUT)") (class "Default")
      (node (ref "C114") (pin "2") (pintype "passive"))
      (node (ref "U53") (pin "1") (pinfunction "OUT_1") (pintype "output"))
      (node (ref "U54") (pin "1") (pinfunction "BASE_1") (pintype "passive"))
    )
    (net (code "260") (name "Net-(U55-VIN+)") (class "Default")
      (node (ref "C116") (pin "1") (pinfunction "1_1") (pintype "passive"))
      (node (ref "R37") (pin "2") (pinfunction "2_2") (pintype "passive"))
      (node (ref "R40") (pin "1") (pinfunction "1_1") (pintype "passive"))
      (node (ref "U55") (pin "8") (pinfunction "VIN+_8") (pintype "input"))
    )
    (net (code "261") (name "Net-(U55-VIN-)") (class "Default")
      (node (ref "C117") (pin "1") (pinfunction "1_1") (pintype "passive"))
      (node (ref "R38") (pin "1") (pinfunction "1_1") (pintype "passive"))
      (node (ref "R39") (pin "1") (pinfunction "1_1") (pintype "passive"))
      (node (ref "U55") (pin "1") (pinfunction "VIN-_1") (pintype "input"))
    )
    (net (code "262") (name "Net-(U55-VOUT+)") (class "Default")
      (node (ref "C117") (pin "2") (pinfunction "2_2") (pintype "passive"))
      (node (ref "R36") (pin "1") (pinfunction "1_1") (pintype "passive"))
      (node (ref "R39") (pin "2") (pinfunction "2_2") (pintype "passive"))
      (node (ref "U55") (pin "4") (pinfunction "VOUT+_4") (pintype "output"))
    )
    (net (code "263") (name "Net-(U55-VOUT-)") (class "Default")
      (node (ref "C116") (pin "2") (pinfunction "2_2") (pintype "passive"))
      (node (ref "R35") (pin "1") (pinfunction "1_1") (pintype "passive"))
      (node (ref "R40") (pin "2") (pinfunction "2_2") (pintype "passive"))
      (node (ref "U55") (pin "5") (pinfunction "VOUT-_5") (pintype "output"))
    )
    (net (code "264") (name "Net-(U56-FDA_IN+)") (class "Default")
      (node (ref "C121") (pin "2") (pinfunction "2_2") (pintype "passive"))
      (node (ref "U56") (pin "12") (pinfunction "FDA_IN+_12") (pintype "input"))
    )
    (net (code "265") (name "Net-(U56-FDA_IN-)") (class "Default")
      (node (ref "C124") (pin "1") (pinfunction "1_1") (pintype "passive"))
      (node (ref "U56") (pin "9") (pinfunction "FDA_IN-_9") (pintype "input"))
    )
    (net (code "266") (name "Net-(U56-IN+)") (class "Default")
      (node (ref "R42") (pin "1") (pinfunction "1_1") (pintype "passive"))
      (node (ref "U56") (pin "2") (pinfunction "IN+_2") (pintype "input"))
    )
    (net (code "267") (name "Net-(U56-IN-)") (class "Default")
      (node (ref "R43") (pin "1") (pinfunction "1_1") (pintype "passive"))
      (node (ref "U56") (pin "3") (pinfunction "IN-_3") (pintype "input"))
    )
    (net (code "268") (name "Net-(U56-VOCM)") (class "Default")
      (node (ref "P85") (pin "2") (pinfunction "2_2") (pintype "passive"))
      (node (ref "U56") (pin "13") (pinfunction "VOCM_13") (pintype "input"))
      (node (ref "U57") (pin "13") (pinfunction "VOCM_13") (pintype "input"))
    )
    (net (code "269") (name "Net-(U57-FDA_IN+)") (class "Default")
      (node (ref "C125") (pin "2") (pinfunction "2_2") (pintype "passive"))
      (node (ref "U57") (pin "12") (pinfunction "FDA_IN+_12") (pintype "input"))
    )
    (net (code "270") (name "Net-(U57-FDA_IN-)") (class "Default")
      (node (ref "C130") (pin "1") (pinfunction "1_1") (pintype "passive"))
      (node (ref "U57") (pin "9") (pinfunction "FDA_IN-_9") (pintype "input"))
    )
    (net (code "271") (name "Net-(U57-IN+)") (class "Default")
      (node (ref "R44") (pin "1") (pinfunction "1_1") (pintype "passive"))
      (node (ref "U57") (pin "2") (pinfunction "IN+_2") (pintype "input"))
    )
    (net (code "272") (name "Net-(U57-IN-)") (class "Default")
      (node (ref "R45") (pin "1") (pinfunction "1_1") (pintype "passive"))
      (node (ref "U57") (pin "3") (pinfunction "IN-_3") (pintype "input"))
    )
    (net (code "273") (name "PCB_AGND") (class "Default")
      (node (ref "J31") (pin "1") (pinfunction "1_1") (pintype "passive"))
      (node (ref "J35") (pin "1") (pinfunction "1_1") (pintype "passive"))
      (node (ref "P14") (pin "2") (pinfunction "2_2") (pintype "passive"))
      (node (ref "P16") (pin "2") (pinfunction "2_2") (pintype "passive"))
      (node (ref "P18") (pin "3") (pinfunction "3_3") (pintype "passive"))
      (node (ref "P20") (pin "2") (pinfunction "2_2") (pintype "passive"))
      (node (ref "P21") (pin "2") (pinfunction "2_2") (pintype "passive"))
      (node (ref "P28") (pin "2") (pinfunction "2_2") (pintype "passive"))
      (node (ref "P28") (pin "4") (pinfunction "4_4") (pintype "passive"))
      (node (ref "P28") (pin "6") (pinfunction "6_6") (pintype "passive"))
      (node (ref "P28") (pin "8") (pinfunction "8_8") (pintype "passive"))
      (node (ref "P5") (pin "1") (pinfunction "1_1") (pintype "passive"))
      (node (ref "P56") (pin "3") (pinfunction "3_3") (pintype "passive"))
      (node (ref "P57") (pin "3") (pinfunction "3_3") (pintype "passive"))
      (node (ref "P58") (pin "3") (pinfunction "3_3") (pintype "passive"))
      (node (ref "P59") (pin "3") (pinfunction "3_3") (pintype "passive"))
      (node (ref "P70") (pin "2") (pinfunction "2_2") (pintype "passive"))
      (node (ref "P70") (pin "4") (pinfunction "4_4") (pintype "passive"))
      (node (ref "P70") (pin "6") (pinfunction "6_6") (pintype "passive"))
      (node (ref "P70") (pin "8") (pinfunction "8_8") (pintype "passive"))
      (node (ref "P72") (pin "3") (pinfunction "3_3") (pintype "passive"))
      (node (ref "P73") (pin "3") (pinfunction "3_3") (pintype "passive"))
      (node (ref "P74") (pin "3") (pinfunction "3_3") (pintype "passive"))
      (node (ref "P75") (pin "3") (pinfunction "3_3") (pintype "passive"))
      (node (ref "P76") (pin "1") (pinfunction "1_1") (pintype "passive"))
      (node (ref "P83") (pin "2") (pinfunction "2_2") (pintype "passive"))
      (node (ref "P84") (pin "2") (pinfunction "2_2") (pintype "passive"))
      (node (ref "P85") (pin "3") (pinfunction "3_3") (pintype "passive"))
      (node (ref "P86") (pin "2") (pinfunction "2_2") (pintype "passive"))
      (node (ref "P87") (pin "2") (pinfunction "2_2") (pintype "passive"))
      (node (ref "R18") (pin "2") (pinfunction "2_2") (pintype "passive"))
      (node (ref "R41") (pin "2") (pinfunction "2_2") (pintype "passive"))
      (node (ref "R8") (pin "2") (pinfunction "2_2") (pintype "passive"))
      (node (ref "U16") (pin "10") (pinfunction "VSS_10") (pintype "power_in"))
      (node (ref "U16") (pin "4") (pinfunction "VREFL_4") (pintype "input"))
      (node (ref "U19") (pin "3") (pinfunction "GND_3") (pintype "power_in"))
      (node (ref "U20") (pin "10") (pinfunction "VSS_10") (pintype "power_in"))
      (node (ref "U20") (pin "4") (pinfunction "VREFL_4") (pintype "input"))
      (node (ref "U24") (pin "2") (pinfunction "GND_2") (pintype "power_in"))
      (node (ref "U27") (pin "2") (pinfunction "GND_2") (pintype "power_in"))
      (node (ref "U3") (pin "6") (pinfunction "VS-_6") (pintype "power_in"))
      (node (ref "U30") (pin "2") (pinfunction "GND_2") (pintype "power_in"))
      (node (ref "U32") (pin "2") (pinfunction "GND_2") (pintype "power_in"))
      (node (ref "U43") (pin "10") (pinfunction "VSS_10") (pintype "power_in"))
      (node (ref "U43") (pin "4") (pinfunction "VREFL_4") (pintype "input"))
      (node (ref "U44") (pin "3") (pinfunction "GND_3") (pintype "power_in"))
      (node (ref "U45") (pin "10") (pinfunction "VSS_10") (pintype "power_in"))
      (node (ref "U45") (pin "4") (pinfunction "VREFL_4") (pintype "input"))
      (node (ref "U46") (pin "2") (pinfunction "GND_2") (pintype "power_in"))
      (node (ref "U48") (pin "2") (pinfunction "GND_2") (pintype "power_in"))
      (node (ref "U51") (pin "2") (pinfunction "GND_2") (pintype "power_in"))
      (node (ref "U53") (pin "2") (pinfunction "GND_2") (pintype "power_in"))
      (node (ref "U55") (pin "6") (pinfunction "VS-_6") (pintype "power_in"))
    )
    (net (code "274") (name "PCB_DGND") (class "Default")
      (node (ref "C65") (pin "2") (pintype "passive"))
      (node (ref "C66") (pin "2") (pintype "passive"))
      (node (ref "C67") (pin "2") (pintype "passive"))
      (node (ref "C68") (pin "2") (pintype "passive"))
      (node (ref "C69") (pin "2") (pintype "passive"))
      (node (ref "C70") (pin "2") (pintype "passive"))
      (node (ref "C71") (pin "2") (pintype "passive"))
      (node (ref "C72") (pin "2") (pintype "passive"))
      (node (ref "C73") (pin "2") (pintype "passive"))
      (node (ref "C74") (pin "2") (pintype "passive"))
      (node (ref "C75") (pin "2") (pintype "passive"))
      (node (ref "C76") (pin "2") (pintype "passive"))
      (node (ref "C77") (pin "2") (pintype "passive"))
      (node (ref "C78") (pin "2") (pintype "passive"))
      (node (ref "C79") (pin "2") (pintype "passive"))
      (node (ref "C80") (pin "2") (pintype "passive"))
      (node (ref "C81") (pin "2") (pintype "passive"))
      (node (ref "C82") (pin "2") (pintype "passive"))
      (node (ref "C83") (pin "2") (pintype "passive"))
      (node (ref "C84") (pin "2") (pintype "passive"))
      (node (ref "R20") (pin "2") (pinfunction "2_2") (pintype "passive"))
      (node (ref "U23") (pin "3") (pinfunction "GND_3") (pintype "power_in"))
      (node (ref "U34") (pin "3") (pinfunction "GND_3") (pintype "power_in"))
      (node (ref "U35") (pin "3") (pinfunction "GND_3") (pintype "power_in"))
      (node (ref "U36") (pin "3") (pinfunction "GND_3") (pintype "power_in"))
      (node (ref "U37") (pin "3") (pinfunction "GND_3") (pintype "power_in"))
      (node (ref "U38") (pin "3") (pinfunction "GND_3") (pintype "power_in"))
      (node (ref "U39") (pin "3") (pinfunction "GND_3") (pintype "power_in"))
      (node (ref "U40") (pin "3") (pinfunction "GND_3") (pintype "power_in"))
      (node (ref "U41") (pin "3") (pinfunction "GND_3") (pintype "power_in"))
      (node (ref "U42") (pin "3") (pinfunction "GND_3") (pintype "power_in"))
    )
    (net (code "275") (name "VBIAS_2P5V") (class "Default")
      (node (ref "C33") (pin "1") (pintype "passive"))
      (node (ref "C40") (pin "1") (pintype "passive"))
      (node (ref "C45") (pin "1") (pintype "passive"))
      (node (ref "C46") (pin "1") (pintype "passive"))
      (node (ref "C50") (pin "1") (pintype "passive"))
      (node (ref "C51") (pin "1") (pintype "passive"))
      (node (ref "C57") (pin "1") (pintype "passive"))
      (node (ref "C58") (pin "1") (pintype "passive"))
      (node (ref "C62") (pin "1") (pintype "passive"))
      (node (ref "C63") (pin "1") (pintype "passive"))
      (node (ref "P55") (pin "2") (pinfunction "2_2") (pintype "passive"))
      (node (ref "R25") (pin "1") (pinfunction "1_1") (pintype "passive"))
      (node (ref "R26") (pin "1") (pinfunction "1_1") (pintype "passive"))
      (node (ref "R28") (pin "1") (pinfunction "1_1") (pintype "passive"))
      (node (ref "R29") (pin "1") (pinfunction "1_1") (pintype "passive"))
      (node (ref "U16") (pin "7") (pinfunction "VREFH_7") (pintype "input"))
      (node (ref "U20") (pin "7") (pinfunction "VREFH_7") (pintype "input"))
    )
    (net (code "276") (name "VDD_2P5V") (class "Default")
      (node (ref "C54") (pin "1") (pinfunction "1_1") (pintype "passive"))
      (node (ref "P55") (pin "1") (pinfunction "1_1") (pintype "passive"))
      (node (ref "U29") (pin "4") (pinfunction "Vout_4") (pintype "output"))
    )
    (net (code "277") (name "VDD_3P3V_IN") (class "Default")
      (node (ref "C1") (pin "1") (pintype "passive"))
      (node (ref "C10") (pin "1") (pintype "passive"))
      (node (ref "C11") (pin "1") (pintype "passive"))
      (node (ref "C12") (pin "1") (pintype "passive"))
      (node (ref "C2") (pin "1") (pintype "passive"))
      (node (ref "C25") (pin "1") (pintype "passive"))
      (node (ref "C26") (pin "1") (pintype "passive"))
      (node (ref "C27") (pin "1") (pintype "passive"))
      (node (ref "C28") (pin "1") (pintype "passive"))
      (node (ref "C29") (pin "1") (pintype "passive"))
      (node (ref "C30") (pin "1") (pintype "passive"))
      (node (ref "C34") (pin "1") (pintype "passive"))
      (node (ref "C35") (pin "1") (pintype "passive"))
      (node (ref "C41") (pin "1") (pintype "passive"))
      (node (ref "C42") (pin "1") (pintype "passive"))
      (node (ref "C65") (pin "1") (pintype "passive"))
      (node (ref "C66") (pin "1") (pintype "passive"))
      (node (ref "C67") (pin "1") (pintype "passive"))
      (node (ref "C68") (pin "1") (pintype "passive"))
      (node (ref "C69") (pin "1") (pintype "passive"))
      (node (ref "C70") (pin "1") (pintype "passive"))
      (node (ref "C71") (pin "1") (pintype "passive"))
      (node (ref "C72") (pin "1") (pintype "passive"))
      (node (ref "C73") (pin "1") (pintype "passive"))
      (node (ref "C74") (pin "1") (pintype "passive"))
      (node (ref "C75") (pin "1") (pintype "passive"))
      (node (ref "C76") (pin "1") (pintype "passive"))
      (node (ref "C77") (pin "1") (pintype "passive"))
      (node (ref "C78") (pin "1") (pintype "passive"))
      (node (ref "C79") (pin "1") (pintype "passive"))
      (node (ref "C80") (pin "1") (pintype "passive"))
      (node (ref "C81") (pin "1") (pintype "passive"))
      (node (ref "C82") (pin "1") (pintype "passive"))
      (node (ref "C83") (pin "1") (pintype "passive"))
      (node (ref "C84") (pin "1") (pintype "passive"))
      (node (ref "C9") (pin "1") (pintype "passive"))
      (node (ref "J9") (pin "1") (pinfunction "1_1") (pintype "passive"))
      (node (ref "P3") (pin "1") (pinfunction "1_1") (pintype "passive"))
      (node (ref "U1") (pin "4") (pinfunction "VDD_4") (pintype "power_in"))
      (node (ref "U10") (pin "4") (pinfunction "VDD_4") (pintype "power_in"))
      (node (ref "U11") (pin "4") (pinfunction "VDD_4") (pintype "power_in"))
      (node (ref "U12") (pin "4") (pinfunction "VDD_4") (pintype "power_in"))
      (node (ref "U13") (pin "4") (pinfunction "VDD_4") (pintype "power_in"))
      (node (ref "U14") (pin "4") (pinfunction "VDD_4") (pintype "power_in"))
      (node (ref "U15") (pin "4") (pinfunction "VDD_4") (pintype "power_in"))
      (node (ref "U17") (pin "4") (pinfunction "VDD_4") (pintype "power_in"))
      (node (ref "U18") (pin "4") (pinfunction "VDD_4") (pintype "power_in"))
      (node (ref "U2") (pin "4") (pinfunction "VDD_4") (pintype "power_in"))
      (node (ref "U21") (pin "4") (pinfunction "VDD_4") (pintype "power_in"))
      (node (ref "U22") (pin "4") (pinfunction "VDD_4") (pintype "power_in"))
      (node (ref "U23") (pin "5") (pinfunction "VCC_5") (pintype "power_in"))
      (node (ref "U34") (pin "5") (pinfunction "VCC_5") (pintype "power_in"))
      (node (ref "U35") (pin "5") (pinfunction "VCC_5") (pintype "power_in"))
      (node (ref "U36") (pin "5") (pinfunction "VCC_5") (pintype "power_in"))
      (node (ref "U37") (pin "5") (pinfunction "VCC_5") (pintype "power_in"))
      (node (ref "U38") (pin "5") (pinfunction "VCC_5") (pintype "power_in"))
      (node (ref "U39") (pin "5") (pinfunction "VCC_5") (pintype "power_in"))
      (node (ref "U4") (pin "4") (pinfunction "VDD_4") (pintype "power_in"))
      (node (ref "U40") (pin "5") (pinfunction "VCC_5") (pintype "power_in"))
      (node (ref "U41") (pin "5") (pinfunction "VCC_5") (pintype "power_in"))
      (node (ref "U42") (pin "5") (pinfunction "VCC_5") (pintype "power_in"))
      (node (ref "U5") (pin "4") (pinfunction "VDD_4") (pintype "power_in"))
      (node (ref "U8") (pin "4") (pinfunction "VDD_4") (pintype "power_in"))
      (node (ref "U9") (pin "4") (pinfunction "VDD_4") (pintype "power_in"))
    )
    (net (code "278") (name "VDD_5V_IN") (class "Default")
      (node (ref "C103") (pin "1") (pinfunction "1_1") (pintype "passive"))
      (node (ref "C105") (pin "1") (pintype "passive"))
      (node (ref "C106") (pin "1") (pintype "passive"))
      (node (ref "C110") (pin "1") (pintype "passive"))
      (node (ref "C111") (pin "1") (pintype "passive"))
      (node (ref "C118") (pin "1") (pintype "passive"))
      (node (ref "C119") (pin "1") (pintype "passive"))
      (node (ref "C120") (pin "1") (pinfunction "1_1") (pintype "passive"))
      (node (ref "C126") (pin "1") (pintype "passive"))
      (node (ref "C128") (pin "1") (pintype "passive"))
      (node (ref "C131") (pin "1") (pintype "passive"))
      (node (ref "C132") (pin "1") (pintype "passive"))
      (node (ref "C18") (pin "1") (pintype "passive"))
      (node (ref "C20") (pin "1") (pintype "passive"))
      (node (ref "C23") (pin "1") (pintype "passive"))
      (node (ref "C24") (pin "1") (pintype "passive"))
      (node (ref "C31") (pin "1") (pintype "passive"))
      (node (ref "C32") (pin "1") (pintype "passive"))
      (node (ref "C36") (pin "1") (pintype "passive"))
      (node (ref "C37") (pin "1") (pintype "passive"))
      (node (ref "C38") (pin "1") (pintype "passive"))
      (node (ref "C39") (pin "1") (pintype "passive"))
      (node (ref "C43") (pin "1") (pintype "passive"))
      (node (ref "C44") (pin "1") (pintype "passive"))
      (node (ref "C48") (pin "1") (pintype "passive"))
      (node (ref "C49") (pin "1") (pintype "passive"))
      (node (ref "C53") (pin "1") (pinfunction "1_1") (pintype "passive"))
      (node (ref "C55") (pin "1") (pintype "passive"))
      (node (ref "C56") (pin "1") (pintype "passive"))
      (node (ref "C6") (pin "1") (pintype "passive"))
      (node (ref "C60") (pin "1") (pintype "passive"))
      (node (ref "C61") (pin "1") (pintype "passive"))
      (node (ref "C7") (pin "1") (pintype "passive"))
      (node (ref "C8") (pin "1") (pinfunction "1_1") (pintype "passive"))
      (node (ref "C85") (pin "1") (pintype "passive"))
      (node (ref "C86") (pin "1") (pintype "passive"))
      (node (ref "C88") (pin "1") (pintype "passive"))
      (node (ref "C89") (pin "1") (pintype "passive"))
      (node (ref "C90") (pin "1") (pintype "passive"))
      (node (ref "C91") (pin "1") (pintype "passive"))
      (node (ref "C93") (pin "1") (pintype "passive"))
      (node (ref "C94") (pin "1") (pintype "passive"))
      (node (ref "C98") (pin "1") (pintype "passive"))
      (node (ref "C99") (pin "1") (pintype "passive"))
      (node (ref "J10") (pin "1") (pinfunction "1_1") (pintype "passive"))
      (node (ref "P11") (pin "1") (pinfunction "1_1") (pintype "passive"))
      (node (ref "P6") (pin "3") (pinfunction "3_3") (pintype "passive"))
      (node (ref "P7") (pin "3") (pinfunction "3_3") (pintype "passive"))
      (node (ref "P77") (pin "3") (pinfunction "3_3") (pintype "passive"))
      (node (ref "P78") (pin "3") (pinfunction "3_3") (pintype "passive"))
      (node (ref "P79") (pin "3") (pinfunction "3_3") (pintype "passive"))
      (node (ref "P8") (pin "3") (pinfunction "3_3") (pintype "passive"))
      (node (ref "R27") (pin "2") (pinfunction "2_2") (pintype "passive"))
      (node (ref "R32") (pin "2") (pinfunction "2_2") (pintype "passive"))
      (node (ref "U16") (pin "1") (pinfunction "VDD_1") (pintype "power_in"))
      (node (ref "U19") (pin "1") (pinfunction "VIN_1") (pintype "input"))
      (node (ref "U20") (pin "1") (pinfunction "VDD_1") (pintype "power_in"))
      (node (ref "U24") (pin "5") (pinfunction "VDD_5") (pintype "power_in"))
      (node (ref "U27") (pin "5") (pinfunction "VDD_5") (pintype "power_in"))
      (node (ref "U29") (pin "2") (pinfunction "Vin_2") (pintype "input"))
      (node (ref "U3") (pin "3") (pinfunction "VS+_3") (pintype "power_in"))
      (node (ref "U3") (pin "7") (pinfunction "*PD_7") (pintype "passive"))
      (node (ref "U30") (pin "5") (pinfunction "VDD_5") (pintype "power_in"))
      (node (ref "U32") (pin "5") (pinfunction "VDD_5") (pintype "power_in"))
      (node (ref "U43") (pin "1") (pinfunction "VDD_1") (pintype "power_in"))
      (node (ref "U44") (pin "1") (pinfunction "VIN_1") (pintype "input"))
      (node (ref "U45") (pin "1") (pinfunction "VDD_1") (pintype "power_in"))
      (node (ref "U46") (pin "5") (pinfunction "VDD_5") (pintype "power_in"))
      (node (ref "U48") (pin "5") (pinfunction "VDD_5") (pintype "power_in"))
      (node (ref "U50") (pin "2") (pinfunction "Vin_2") (pintype "input"))
      (node (ref "U51") (pin "5") (pinfunction "VDD_5") (pintype "power_in"))
      (node (ref "U53") (pin "5") (pinfunction "VDD_5") (pintype "power_in"))
      (node (ref "U55") (pin "3") (pinfunction "VS+_3") (pintype "power_in"))
      (node (ref "U55") (pin "7") (pinfunction "*PD_7") (pintype "passive"))
      (node (ref "U56") (pin "6") (pinfunction "VS+_6") (pintype "power_in"))
      (node (ref "U56") (pin "7") (pinfunction "LVDD_7") (pintype "power_in"))
      (node (ref "U57") (pin "6") (pinfunction "VS+_6") (pintype "power_in"))
      (node (ref "U57") (pin "7") (pinfunction "LVDD_7") (pintype "power_in"))
      (node (ref "U6") (pin "6") (pinfunction "VS+_6") (pintype "power_in"))
      (node (ref "U6") (pin "7") (pinfunction "LVDD_7") (pintype "power_in"))
      (node (ref "U7") (pin "6") (pinfunction "VS+_6") (pintype "power_in"))
      (node (ref "U7") (pin "7") (pinfunction "LVDD_7") (pintype "power_in"))
      (node (ref "VDD_1") (pin "A") (pinfunction "A_A") (pintype "passive"))
    )
    (net (code "279") (name "VNEG") (class "Default")
      (node (ref "C122") (pin "1") (pintype "passive"))
      (node (ref "C123") (pin "1") (pintype "passive"))
      (node (ref "C127") (pin "1") (pintype "passive"))
      (node (ref "C129") (pin "1") (pintype "passive"))
      (node (ref "C14") (pin "1") (pintype "passive"))
      (node (ref "C15") (pin "1") (pintype "passive"))
      (node (ref "C19") (pin "1") (pintype "passive"))
      (node (ref "C21") (pin "1") (pintype "passive"))
      (node (ref "J11") (pin "1") (pinfunction "1_1") (pintype "passive"))
      (node (ref "P13") (pin "1") (pinfunction "1_1") (pintype "passive"))
      (node (ref "U56") (pin "14") (pinfunction "LVSS_14") (pintype "power_in"))
      (node (ref "U56") (pin "15") (pinfunction "VS-_15") (pintype "power_in"))
      (node (ref "U56") (pin "17") (pinfunction "EPAD_17") (pintype "passive"))
      (node (ref "U57") (pin "14") (pinfunction "LVSS_14") (pintype "power_in"))
      (node (ref "U57") (pin "15") (pinfunction "VS-_15") (pintype "power_in"))
      (node (ref "U57") (pin "17") (pinfunction "EPAD_17") (pintype "passive"))
      (node (ref "U6") (pin "14") (pinfunction "LVSS_14") (pintype "power_in"))
      (node (ref "U6") (pin "15") (pinfunction "VS-_15") (pintype "power_in"))
      (node (ref "U6") (pin "17") (pinfunction "EPAD_17") (pintype "passive"))
      (node (ref "U7") (pin "14") (pinfunction "LVSS_14") (pintype "power_in"))
      (node (ref "U7") (pin "15") (pinfunction "VS-_15") (pintype "power_in"))
      (node (ref "U7") (pin "17") (pinfunction "EPAD_17") (pintype "passive"))
    )
    (net (code "280") (name "unconnected-(J34-PadC02)") (class "Default")
      (node (ref "J34") (pin "C02") (pinfunction "C02_C02") (pintype "passive"))
    )
    (net (code "281") (name "unconnected-(J34-PadC03)") (class "Default")
      (node (ref "J34") (pin "C03") (pinfunction "C03_C03") (pintype "passive"))
    )
    (net (code "282") (name "unconnected-(J34-PadC06)") (class "Default")
      (node (ref "J34") (pin "C06") (pinfunction "C06_C06") (pintype "passive"))
    )
    (net (code "283") (name "unconnected-(J34-PadC07)") (class "Default")
      (node (ref "J34") (pin "C07") (pinfunction "C07_C07") (pintype "passive"))
    )
    (net (code "284") (name "unconnected-(J34-PadC30)") (class "Default")
      (node (ref "J34") (pin "C30") (pinfunction "C30_C30") (pintype "passive"))
    )
    (net (code "285") (name "unconnected-(J34-PadC31)") (class "Default")
      (node (ref "J34") (pin "C31") (pinfunction "C31_C31") (pintype "passive"))
    )
    (net (code "286") (name "unconnected-(J34-PadC34)") (class "Default")
      (node (ref "J34") (pin "C34") (pinfunction "C34_C34") (pintype "passive"))
    )
    (net (code "287") (name "unconnected-(J34-PadC37)") (class "Default")
      (node (ref "J34") (pin "C37") (pinfunction "C37_C37") (pintype "passive"))
    )
    (net (code "288") (name "unconnected-(J34-PadD01)") (class "Default")
      (node (ref "J34") (pin "D01") (pinfunction "D01_D01") (pintype "passive"))
    )
    (net (code "289") (name "unconnected-(J34-PadD04)") (class "Default")
      (node (ref "J34") (pin "D04") (pinfunction "D04_D04") (pintype "passive"))
    )
    (net (code "290") (name "unconnected-(J34-PadD05)") (class "Default")
      (node (ref "J34") (pin "D05") (pinfunction "D05_D05") (pintype "passive"))
    )
    (net (code "291") (name "unconnected-(J34-PadD24)") (class "Default")
      (node (ref "J34") (pin "D24") (pinfunction "D24_D24") (pintype "passive"))
    )
    (net (code "292") (name "unconnected-(J34-PadD26)") (class "Default")
      (node (ref "J34") (pin "D26") (pinfunction "D26_D26") (pintype "passive"))
    )
    (net (code "293") (name "unconnected-(J34-PadD27)") (class "Default")
      (node (ref "J34") (pin "D27") (pinfunction "D27_D27") (pintype "passive"))
    )
    (net (code "294") (name "unconnected-(J34-PadD29)") (class "Default")
      (node (ref "J34") (pin "D29") (pinfunction "D29_D29") (pintype "passive"))
    )
    (net (code "295") (name "unconnected-(J34-PadD30)") (class "Default")
      (node (ref "J34") (pin "D30") (pinfunction "D30_D30") (pintype "passive"))
    )
    (net (code "296") (name "unconnected-(J34-PadD31)") (class "Default")
      (node (ref "J34") (pin "D31") (pinfunction "D31_D31") (pintype "passive"))
    )
    (net (code "297") (name "unconnected-(J34-PadD32)") (class "Default")
      (node (ref "J34") (pin "D32") (pinfunction "D32_D32") (pintype "passive"))
    )
    (net (code "298") (name "unconnected-(J34-PadD33)") (class "Default")
      (node (ref "J34") (pin "D33") (pinfunction "D33_D33") (pintype "passive"))
    )
    (net (code "299") (name "unconnected-(J34-PadD34)") (class "Default")
      (node (ref "J34") (pin "D34") (pinfunction "D34_D34") (pintype "passive"))
    )
    (net (code "300") (name "unconnected-(J34-PadD35)") (class "Default")
      (node (ref "J34") (pin "D35") (pinfunction "D35_D35") (pintype "passive"))
    )
    (net (code "301") (name "unconnected-(J34-PadD36)") (class "Default")
      (node (ref "J34") (pin "D36") (pinfunction "D36_D36") (pintype "passive"))
    )
    (net (code "302") (name "unconnected-(J34-PadD38)") (class "Default")
      (node (ref "J34") (pin "D38") (pinfunction "D38_D38") (pintype "passive"))
    )
    (net (code "303") (name "unconnected-(J34-PadD40)") (class "Default")
      (node (ref "J34") (pin "D40") (pinfunction "D40_D40") (pintype "passive"))
    )
    (net (code "304") (name "unconnected-(J34-PadG02)") (class "Default")
      (node (ref "J34") (pin "G02") (pinfunction "G02_G02") (pintype "passive"))
    )
    (net (code "305") (name "unconnected-(J34-PadG03)") (class "Default")
      (node (ref "J34") (pin "G03") (pinfunction "G03_G03") (pintype "passive"))
    )
    (net (code "306") (name "unconnected-(J34-PadG06)") (class "Default")
      (node (ref "J34") (pin "G06") (pinfunction "G06_G06") (pintype "passive"))
    )
    (net (code "307") (name "unconnected-(J34-PadG07)") (class "Default")
      (node (ref "J34") (pin "G07") (pinfunction "G07_G07") (pintype "passive"))
    )
    (net (code "308") (name "unconnected-(J34-PadG09)") (class "Default")
      (node (ref "J34") (pin "G09") (pinfunction "G09_G09") (pintype "passive"))
    )
    (net (code "309") (name "unconnected-(J34-PadG10)") (class "Default")
      (node (ref "J34") (pin "G10") (pinfunction "G10_G10") (pintype "passive"))
    )
    (net (code "310") (name "unconnected-(J34-PadG12)") (class "Default")
      (node (ref "J34") (pin "G12") (pinfunction "G12_G12") (pintype "passive"))
    )
    (net (code "311") (name "unconnected-(J34-PadG13)") (class "Default")
      (node (ref "J34") (pin "G13") (pinfunction "G13_G13") (pintype "passive"))
    )
    (net (code "312") (name "unconnected-(J34-PadG15)") (class "Default")
      (node (ref "J34") (pin "G15") (pinfunction "G15_G15") (pintype "passive"))
    )
    (net (code "313") (name "unconnected-(J34-PadG16)") (class "Default")
      (node (ref "J34") (pin "G16") (pinfunction "G16_G16") (pintype "passive"))
    )
    (net (code "314") (name "unconnected-(J34-PadG18)") (class "Default")
      (node (ref "J34") (pin "G18") (pinfunction "G18_G18") (pintype "passive"))
    )
    (net (code "315") (name "unconnected-(J34-PadG19)") (class "Default")
      (node (ref "J34") (pin "G19") (pinfunction "G19_G19") (pintype "passive"))
    )
    (net (code "316") (name "unconnected-(J34-PadG21)") (class "Default")
      (node (ref "J34") (pin "G21") (pinfunction "G21_G21") (pintype "passive"))
    )
    (net (code "317") (name "unconnected-(J34-PadG22)") (class "Default")
      (node (ref "J34") (pin "G22") (pinfunction "G22_G22") (pintype "passive"))
    )
    (net (code "318") (name "unconnected-(J34-PadG24)") (class "Default")
      (node (ref "J34") (pin "G24") (pinfunction "G24_G24") (pintype "passive"))
    )
    (net (code "319") (name "unconnected-(J34-PadG25)") (class "Default")
      (node (ref "J34") (pin "G25") (pinfunction "G25_G25") (pintype "passive"))
    )
    (net (code "320") (name "unconnected-(J34-PadG27)") (class "Default")
      (node (ref "J34") (pin "G27") (pinfunction "G27_G27") (pintype "passive"))
    )
    (net (code "321") (name "unconnected-(J34-PadG28)") (class "Default")
      (node (ref "J34") (pin "G28") (pinfunction "G28_G28") (pintype "passive"))
    )
    (net (code "322") (name "unconnected-(J34-PadG30)") (class "Default")
      (node (ref "J34") (pin "G30") (pinfunction "G30_G30") (pintype "passive"))
    )
    (net (code "323") (name "unconnected-(J34-PadG31)") (class "Default")
      (node (ref "J34") (pin "G31") (pinfunction "G31_G31") (pintype "passive"))
    )
    (net (code "324") (name "unconnected-(J34-PadG33)") (class "Default")
      (node (ref "J34") (pin "G33") (pinfunction "G33_G33") (pintype "passive"))
    )
    (net (code "325") (name "unconnected-(J34-PadG34)") (class "Default")
      (node (ref "J34") (pin "G34") (pinfunction "G34_G34") (pintype "passive"))
    )
    (net (code "326") (name "unconnected-(J34-PadG36)") (class "Default")
      (node (ref "J34") (pin "G36") (pinfunction "G36_G36") (pintype "passive"))
    )
    (net (code "327") (name "unconnected-(J34-PadG37)") (class "Default")
      (node (ref "J34") (pin "G37") (pinfunction "G37_G37") (pintype "passive"))
    )
    (net (code "328") (name "unconnected-(J34-PadH01)") (class "Default")
      (node (ref "J34") (pin "H01") (pinfunction "H01_H01") (pintype "passive"))
    )
    (net (code "329") (name "unconnected-(J34-PadH02)") (class "Default")
      (node (ref "J34") (pin "H02") (pinfunction "H02_H02") (pintype "passive"))
    )
    (net (code "330") (name "unconnected-(J34-PadH04)") (class "Default")
      (node (ref "J34") (pin "H04") (pinfunction "H04_H04") (pintype "passive"))
    )
    (net (code "331") (name "unconnected-(J34-PadH05)") (class "Default")
      (node (ref "J34") (pin "H05") (pinfunction "H05_H05") (pintype "passive"))
    )
    (net (code "332") (name "unconnected-(J34-PadH08)") (class "Default")
      (node (ref "J34") (pin "H08") (pinfunction "H08_H08") (pintype "passive"))
    )
    (net (code "333") (name "unconnected-(J34-PadH10)") (class "Default")
      (node (ref "J34") (pin "H10") (pinfunction "H10_H10") (pintype "passive"))
    )
    (net (code "334") (name "unconnected-(J34-PadH11)") (class "Default")
      (node (ref "J34") (pin "H11") (pinfunction "H11_H11") (pintype "passive"))
    )
    (net (code "335") (name "unconnected-(J34-PadH13)") (class "Default")
      (node (ref "J34") (pin "H13") (pinfunction "H13_H13") (pintype "passive"))
    )
    (net (code "336") (name "unconnected-(J34-PadH14)") (class "Default")
      (node (ref "J34") (pin "H14") (pinfunction "H14_H14") (pintype "passive"))
    )
    (net (code "337") (name "unconnected-(J34-PadH16)") (class "Default")
      (node (ref "J34") (pin "H16") (pinfunction "H16_H16") (pintype "passive"))
    )
    (net (code "338") (name "unconnected-(J34-PadH17)") (class "Default")
      (node (ref "J34") (pin "H17") (pinfunction "H17_H17") (pintype "passive"))
    )
    (net (code "339") (name "unconnected-(J34-PadH19)") (class "Default")
      (node (ref "J34") (pin "H19") (pinfunction "H19_H19") (pintype "passive"))
    )
    (net (code "340") (name "unconnected-(J34-PadH20)") (class "Default")
      (node (ref "J34") (pin "H20") (pinfunction "H20_H20") (pintype "passive"))
    )
    (net (code "341") (name "unconnected-(J34-PadH22)") (class "Default")
      (node (ref "J34") (pin "H22") (pinfunction "H22_H22") (pintype "passive"))
    )
    (net (code "342") (name "unconnected-(J34-PadH23)") (class "Default")
      (node (ref "J34") (pin "H23") (pinfunction "H23_H23") (pintype "passive"))
    )
    (net (code "343") (name "unconnected-(J34-PadH25)") (class "Default")
      (node (ref "J34") (pin "H25") (pinfunction "H25_H25") (pintype "passive"))
    )
    (net (code "344") (name "unconnected-(J34-PadH26)") (class "Default")
      (node (ref "J34") (pin "H26") (pinfunction "H26_H26") (pintype "passive"))
    )
    (net (code "345") (name "unconnected-(J34-PadH28)") (class "Default")
      (node (ref "J34") (pin "H28") (pinfunction "H28_H28") (pintype "passive"))
    )
    (net (code "346") (name "unconnected-(J34-PadH29)") (class "Default")
      (node (ref "J34") (pin "H29") (pinfunction "H29_H29") (pintype "passive"))
    )
    (net (code "347") (name "unconnected-(J34-PadH31)") (class "Default")
      (node (ref "J34") (pin "H31") (pinfunction "H31_H31") (pintype "passive"))
    )
    (net (code "348") (name "unconnected-(J34-PadH32)") (class "Default")
      (node (ref "J34") (pin "H32") (pinfunction "H32_H32") (pintype "passive"))
    )
    (net (code "349") (name "unconnected-(J34-PadH34)") (class "Default")
      (node (ref "J34") (pin "H34") (pinfunction "H34_H34") (pintype "passive"))
    )
    (net (code "350") (name "unconnected-(J34-PadH35)") (class "Default")
      (node (ref "J34") (pin "H35") (pinfunction "H35_H35") (pintype "passive"))
    )
    (net (code "351") (name "unconnected-(J34-PadH37)") (class "Default")
      (node (ref "J34") (pin "H37") (pinfunction "H37_H37") (pintype "passive"))
    )
    (net (code "352") (name "unconnected-(J34-PadH38)") (class "Default")
      (node (ref "J34") (pin "H38") (pinfunction "H38_H38") (pintype "passive"))
    )
    (net (code "353") (name "unconnected-(J34-PadH40)") (class "Default")
      (node (ref "J34") (pin "H40") (pinfunction "H40_H40") (pintype "passive"))
    )
    (net (code "354") (name "unconnected-(U6-NC-Pad8)") (class "Default")
      (node (ref "U6") (pin "8") (pinfunction "NC_8") (pintype "passive"))
    )
    (net (code "355") (name "unconnected-(U7-NC-Pad8)") (class "Default")
      (node (ref "U7") (pin "8") (pinfunction "NC_8") (pintype "passive"))
    )
    (net (code "356") (name "unconnected-(U16-NIC-Pad5)") (class "Default")
      (node (ref "U16") (pin "5") (pinfunction "NIC_5") (pintype "passive"))
    )
    (net (code "357") (name "unconnected-(U16-NIC-Pad6)") (class "Default")
      (node (ref "U16") (pin "6") (pinfunction "NIC_6") (pintype "passive"))
    )
    (net (code "358") (name "unconnected-(U16-NIC-Pad15)") (class "Default")
      (node (ref "U16") (pin "15") (pinfunction "NIC_15") (pintype "passive"))
    )
    (net (code "359") (name "unconnected-(U16-NIC-Pad16)") (class "Default")
      (node (ref "U16") (pin "16") (pinfunction "NIC_16") (pintype "passive"))
    )
    (net (code "360") (name "unconnected-(U16-NIC-Pad17)") (class "Default")
      (node (ref "U16") (pin "17") (pinfunction "NIC_17") (pintype "passive"))
    )
    (net (code "361") (name "unconnected-(U20-NIC-Pad5)") (class "Default")
      (node (ref "U20") (pin "5") (pinfunction "NIC_5") (pintype "passive"))
    )
    (net (code "362") (name "unconnected-(U20-NIC-Pad6)") (class "Default")
      (node (ref "U20") (pin "6") (pinfunction "NIC_6") (pintype "passive"))
    )
    (net (code "363") (name "unconnected-(U20-NIC-Pad15)") (class "Default")
      (node (ref "U20") (pin "15") (pinfunction "NIC_15") (pintype "passive"))
    )
    (net (code "364") (name "unconnected-(U20-NIC-Pad16)") (class "Default")
      (node (ref "U20") (pin "16") (pinfunction "NIC_16") (pintype "passive"))
    )
    (net (code "365") (name "unconnected-(U20-NIC-Pad17)") (class "Default")
      (node (ref "U20") (pin "17") (pinfunction "NIC_17") (pintype "passive"))
    )
    (net (code "366") (name "unconnected-(U23-NC-Pad1)") (class "Default")
      (node (ref "U23") (pin "1") (pinfunction "NC_1") (pintype "passive"))
    )
    (net (code "367") (name "unconnected-(U26-3.3V-Pad3.3V_1)") (class "Default")
      (node (ref "U26") (pin "3.3V_1") (pinfunction "3.3V_3.3V_1") (pintype "power_in"))
    )
    (net (code "368") (name "unconnected-(U26-3.3V-Pad3.3V_2)") (class "Default")
      (node (ref "U26") (pin "3.3V_2") (pinfunction "3.3V_3.3V_2") (pintype "power_in"))
    )
    (net (code "369") (name "unconnected-(U26-3.3V-Pad3.3V_3)") (class "Default")
      (node (ref "U26") (pin "3.3V_3") (pinfunction "3.3V_3.3V_3") (pintype "power_in"))
    )
    (net (code "370") (name "unconnected-(U26-A17-Pad41)") (class "Default")
      (node (ref "U26") (pin "41") (pinfunction "A17_41") (pintype "bidirectional"))
    )
    (net (code "371") (name "unconnected-(U26-Pad5V)") (class "Default")
      (node (ref "U26") (pin "5V") (pinfunction "5V_5V") (pintype "power_in"))
    )
    (net (code "372") (name "unconnected-(U26-PadD+)") (class "Default")
      (node (ref "U26") (pin "D+") (pinfunction "D+_D+") (pintype "bidirectional"))
    )
    (net (code "373") (name "unconnected-(U26-PadD-)") (class "Default")
      (node (ref "U26") (pin "D-") (pinfunction "D-_D-") (pintype "bidirectional"))
    )
    (net (code "374") (name "unconnected-(U26-PadLED)") (class "Default")
      (node (ref "U26") (pin "LED") (pinfunction "LED_LED") (pintype "bidirectional"))
    )
    (net (code "375") (name "unconnected-(U26-PadON{slash}OFF)") (class "Default")
      (node (ref "U26") (pin "ON/OFF") (pinfunction "ON/OFF_ON/OFF") (pintype "bidirectional"))
    )
    (net (code "376") (name "unconnected-(U26-PadPROGRAM)") (class "Default")
      (node (ref "U26") (pin "PROGRAM") (pinfunction "PROGRAM_PROGRAM") (pintype "bidirectional"))
    )
    (net (code "377") (name "unconnected-(U26-PadR+)") (class "Default")
      (node (ref "U26") (pin "R+") (pinfunction "R+_R+") (pintype "bidirectional"))
    )
    (net (code "378") (name "unconnected-(U26-PadR-)") (class "Default")
      (node (ref "U26") (pin "R-") (pinfunction "R-_R-") (pintype "bidirectional"))
    )
    (net (code "379") (name "unconnected-(U26-PadT+)") (class "Default")
      (node (ref "U26") (pin "T+") (pinfunction "T+_T+") (pintype "bidirectional"))
    )
    (net (code "380") (name "unconnected-(U26-PadT-)") (class "Default")
      (node (ref "U26") (pin "T-") (pinfunction "T-_T-") (pintype "bidirectional"))
    )
    (net (code "381") (name "unconnected-(U26-PadVBAT)") (class "Default")
      (node (ref "U26") (pin "VBAT") (pinfunction "VBAT_VBAT") (pintype "passive"))
    )
    (net (code "382") (name "unconnected-(U26-PadVIN)") (class "Default")
      (node (ref "U26") (pin "VIN") (pinfunction "VIN_VIN") (pintype "input"))
    )
    (net (code "383") (name "unconnected-(U26-PadVUSB)") (class "Default")
      (node (ref "U26") (pin "VUSB") (pinfunction "VUSB_VUSB") (pintype "passive"))
    )
    (net (code "384") (name "unconnected-(U26-USB_GND-PadUSB_GND1)") (class "Default")
      (node (ref "U26") (pin "USB_GND1") (pinfunction "USB_GND_USB_GND1") (pintype "power_in"))
    )
    (net (code "385") (name "unconnected-(U26-USB_GND-PadUSB_GND2)") (class "Default")
      (node (ref "U26") (pin "USB_GND2") (pinfunction "USB_GND_USB_GND2") (pintype "power_in"))
    )
    (net (code "386") (name "unconnected-(U34-NC-Pad1)") (class "Default")
      (node (ref "U34") (pin "1") (pinfunction "NC_1") (pintype "passive"))
    )
    (net (code "387") (name "unconnected-(U35-NC-Pad1)") (class "Default")
      (node (ref "U35") (pin "1") (pinfunction "NC_1") (pintype "passive"))
    )
    (net (code "388") (name "unconnected-(U36-NC-Pad1)") (class "Default")
      (node (ref "U36") (pin "1") (pinfunction "NC_1") (pintype "passive"))
    )
    (net (code "389") (name "unconnected-(U37-NC-Pad1)") (class "Default")
      (node (ref "U37") (pin "1") (pinfunction "NC_1") (pintype "passive"))
    )
    (net (code "390") (name "unconnected-(U38-NC-Pad1)") (class "Default")
      (node (ref "U38") (pin "1") (pinfunction "NC_1") (pintype "passive"))
    )
    (net (code "391") (name "unconnected-(U39-NC-Pad1)") (class "Default")
      (node (ref "U39") (pin "1") (pinfunction "NC_1") (pintype "passive"))
    )
    (net (code "392") (name "unconnected-(U40-NC-Pad1)") (class "Default")
      (node (ref "U40") (pin "1") (pinfunction "NC_1") (pintype "passive"))
    )
    (net (code "393") (name "unconnected-(U41-NC-Pad1)") (class "Default")
      (node (ref "U41") (pin "1") (pinfunction "NC_1") (pintype "passive"))
    )
    (net (code "394") (name "unconnected-(U42-NC-Pad1)") (class "Default")
      (node (ref "U42") (pin "1") (pinfunction "NC_1") (pintype "passive"))
    )
    (net (code "395") (name "unconnected-(U43-NIC-Pad5)") (class "Default")
      (node (ref "U43") (pin "5") (pinfunction "NIC_5") (pintype "passive"))
    )
    (net (code "396") (name "unconnected-(U43-NIC-Pad6)") (class "Default")
      (node (ref "U43") (pin "6") (pinfunction "NIC_6") (pintype "passive"))
    )
    (net (code "397") (name "unconnected-(U43-NIC-Pad15)") (class "Default")
      (node (ref "U43") (pin "15") (pinfunction "NIC_15") (pintype "passive"))
    )
    (net (code "398") (name "unconnected-(U43-NIC-Pad16)") (class "Default")
      (node (ref "U43") (pin "16") (pinfunction "NIC_16") (pintype "passive"))
    )
    (net (code "399") (name "unconnected-(U43-NIC-Pad17)") (class "Default")
      (node (ref "U43") (pin "17") (pinfunction "NIC_17") (pintype "passive"))
    )
    (net (code "400") (name "unconnected-(U45-NIC-Pad5)") (class "Default")
      (node (ref "U45") (pin "5") (pinfunction "NIC_5") (pintype "passive"))
    )
    (net (code "401") (name "unconnected-(U45-NIC-Pad6)") (class "Default")
      (node (ref "U45") (pin "6") (pinfunction "NIC_6") (pintype "passive"))
    )
    (net (code "402") (name "unconnected-(U45-NIC-Pad15)") (class "Default")
      (node (ref "U45") (pin "15") (pinfunction "NIC_15") (pintype "passive"))
    )
    (net (code "403") (name "unconnected-(U45-NIC-Pad16)") (class "Default")
      (node (ref "U45") (pin "16") (pinfunction "NIC_16") (pintype "passive"))
    )
    (net (code "404") (name "unconnected-(U45-NIC-Pad17)") (class "Default")
      (node (ref "U45") (pin "17") (pinfunction "NIC_17") (pintype "passive"))
    )
    (net (code "405") (name "unconnected-(U56-NC-Pad8)") (class "Default")
      (node (ref "U56") (pin "8") (pinfunction "NC_8") (pintype "passive"))
    )
    (net (code "406") (name "unconnected-(U57-NC-Pad8)") (class "Default")
      (node (ref "U57") (pin "8") (pinfunction "NC_8") (pintype "passive"))
    )
  )
)
